# v1_0.net
KiCad netlist of a schematic drawn in EAGLE
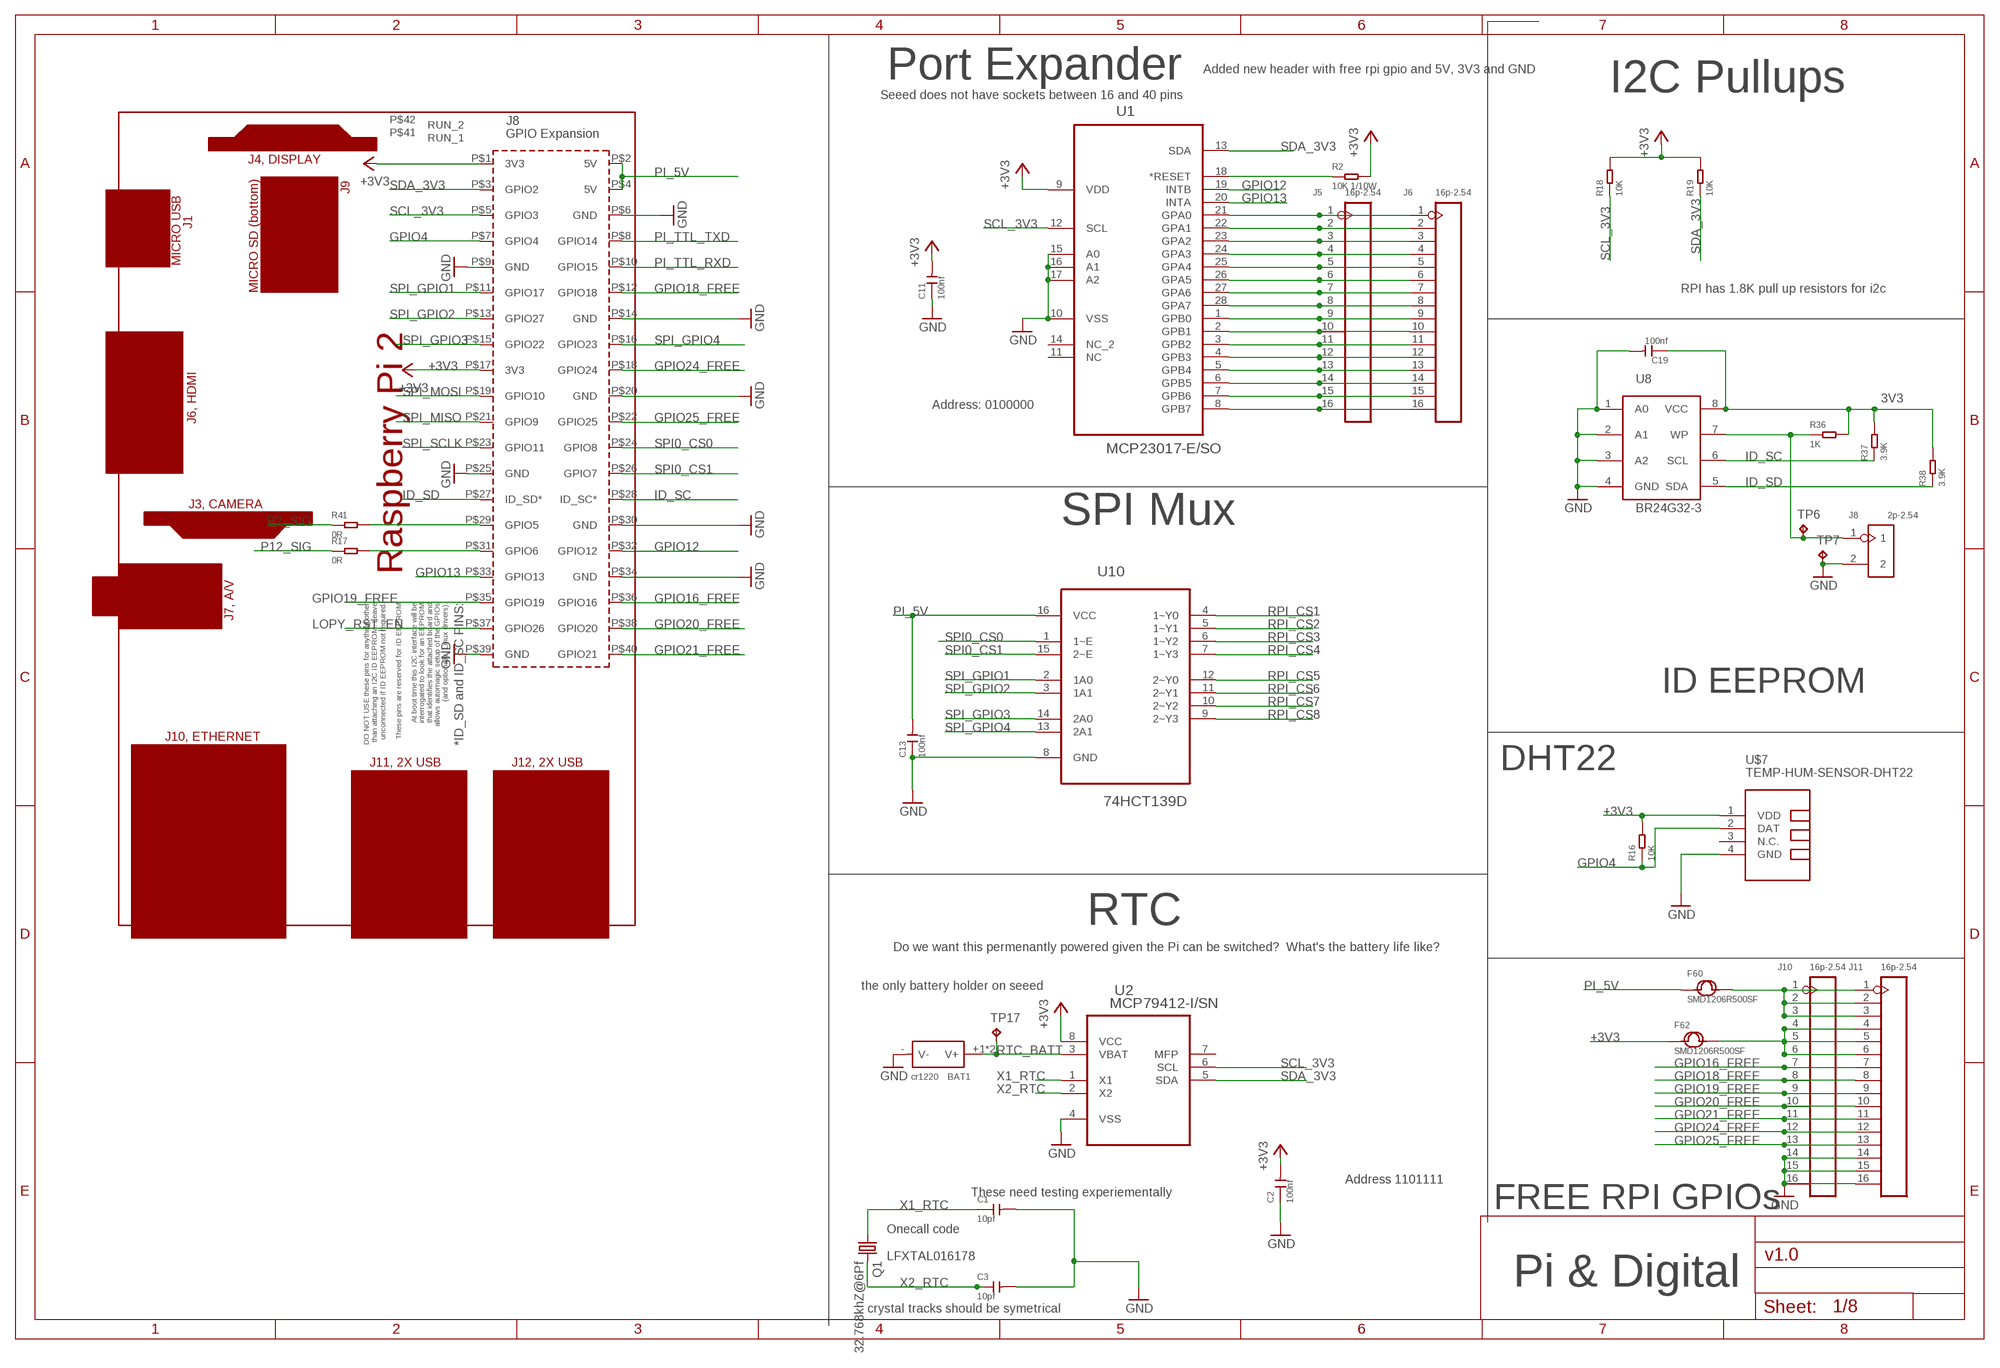
[diagram p0: schematic, sheet 1]
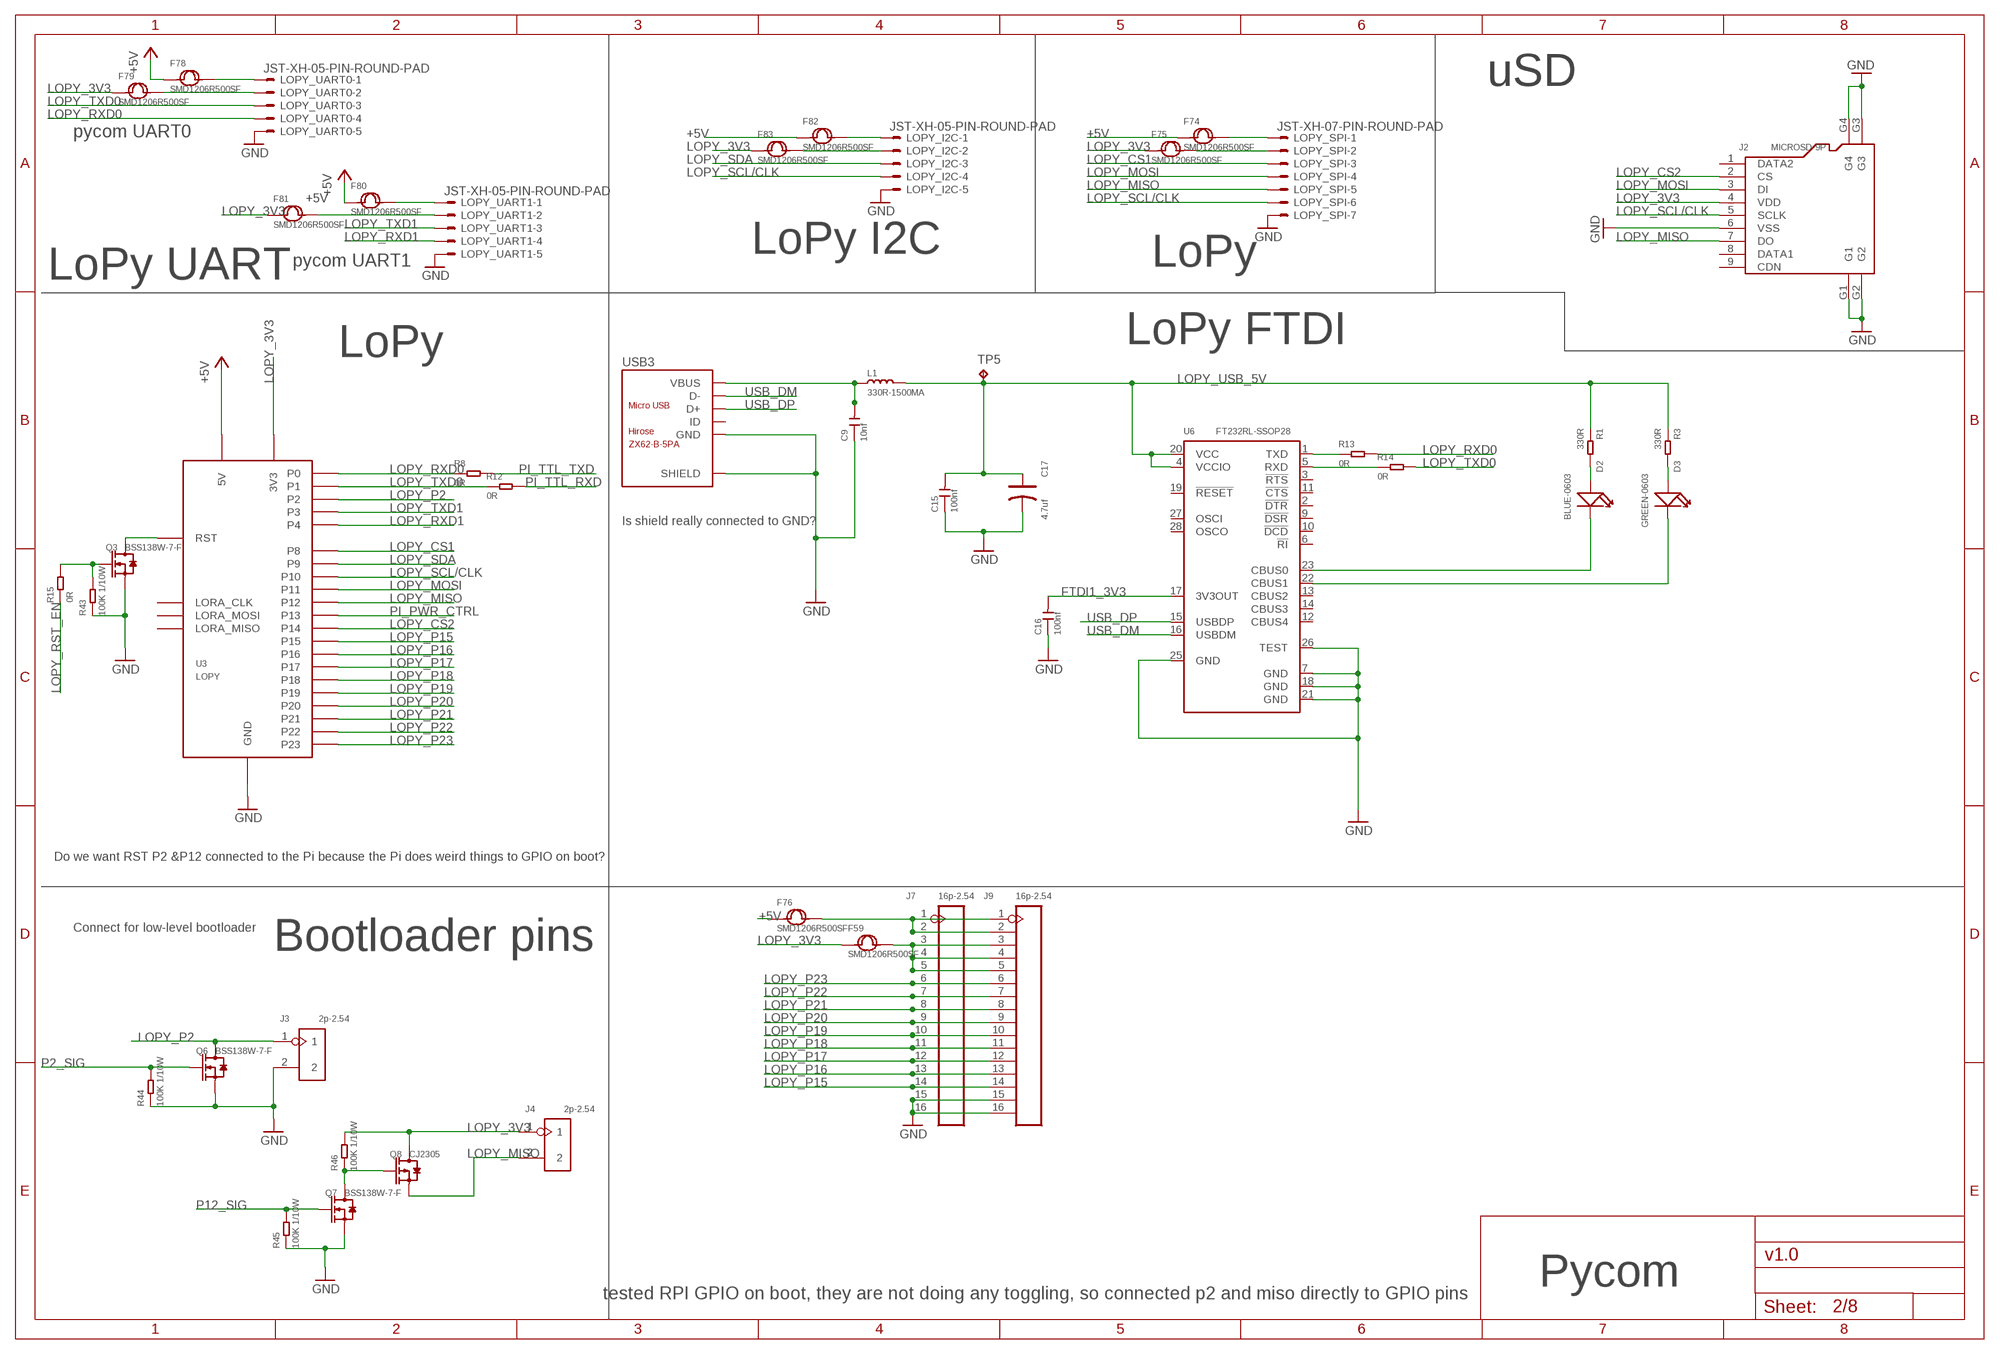
[diagram p1: schematic, sheet 2]
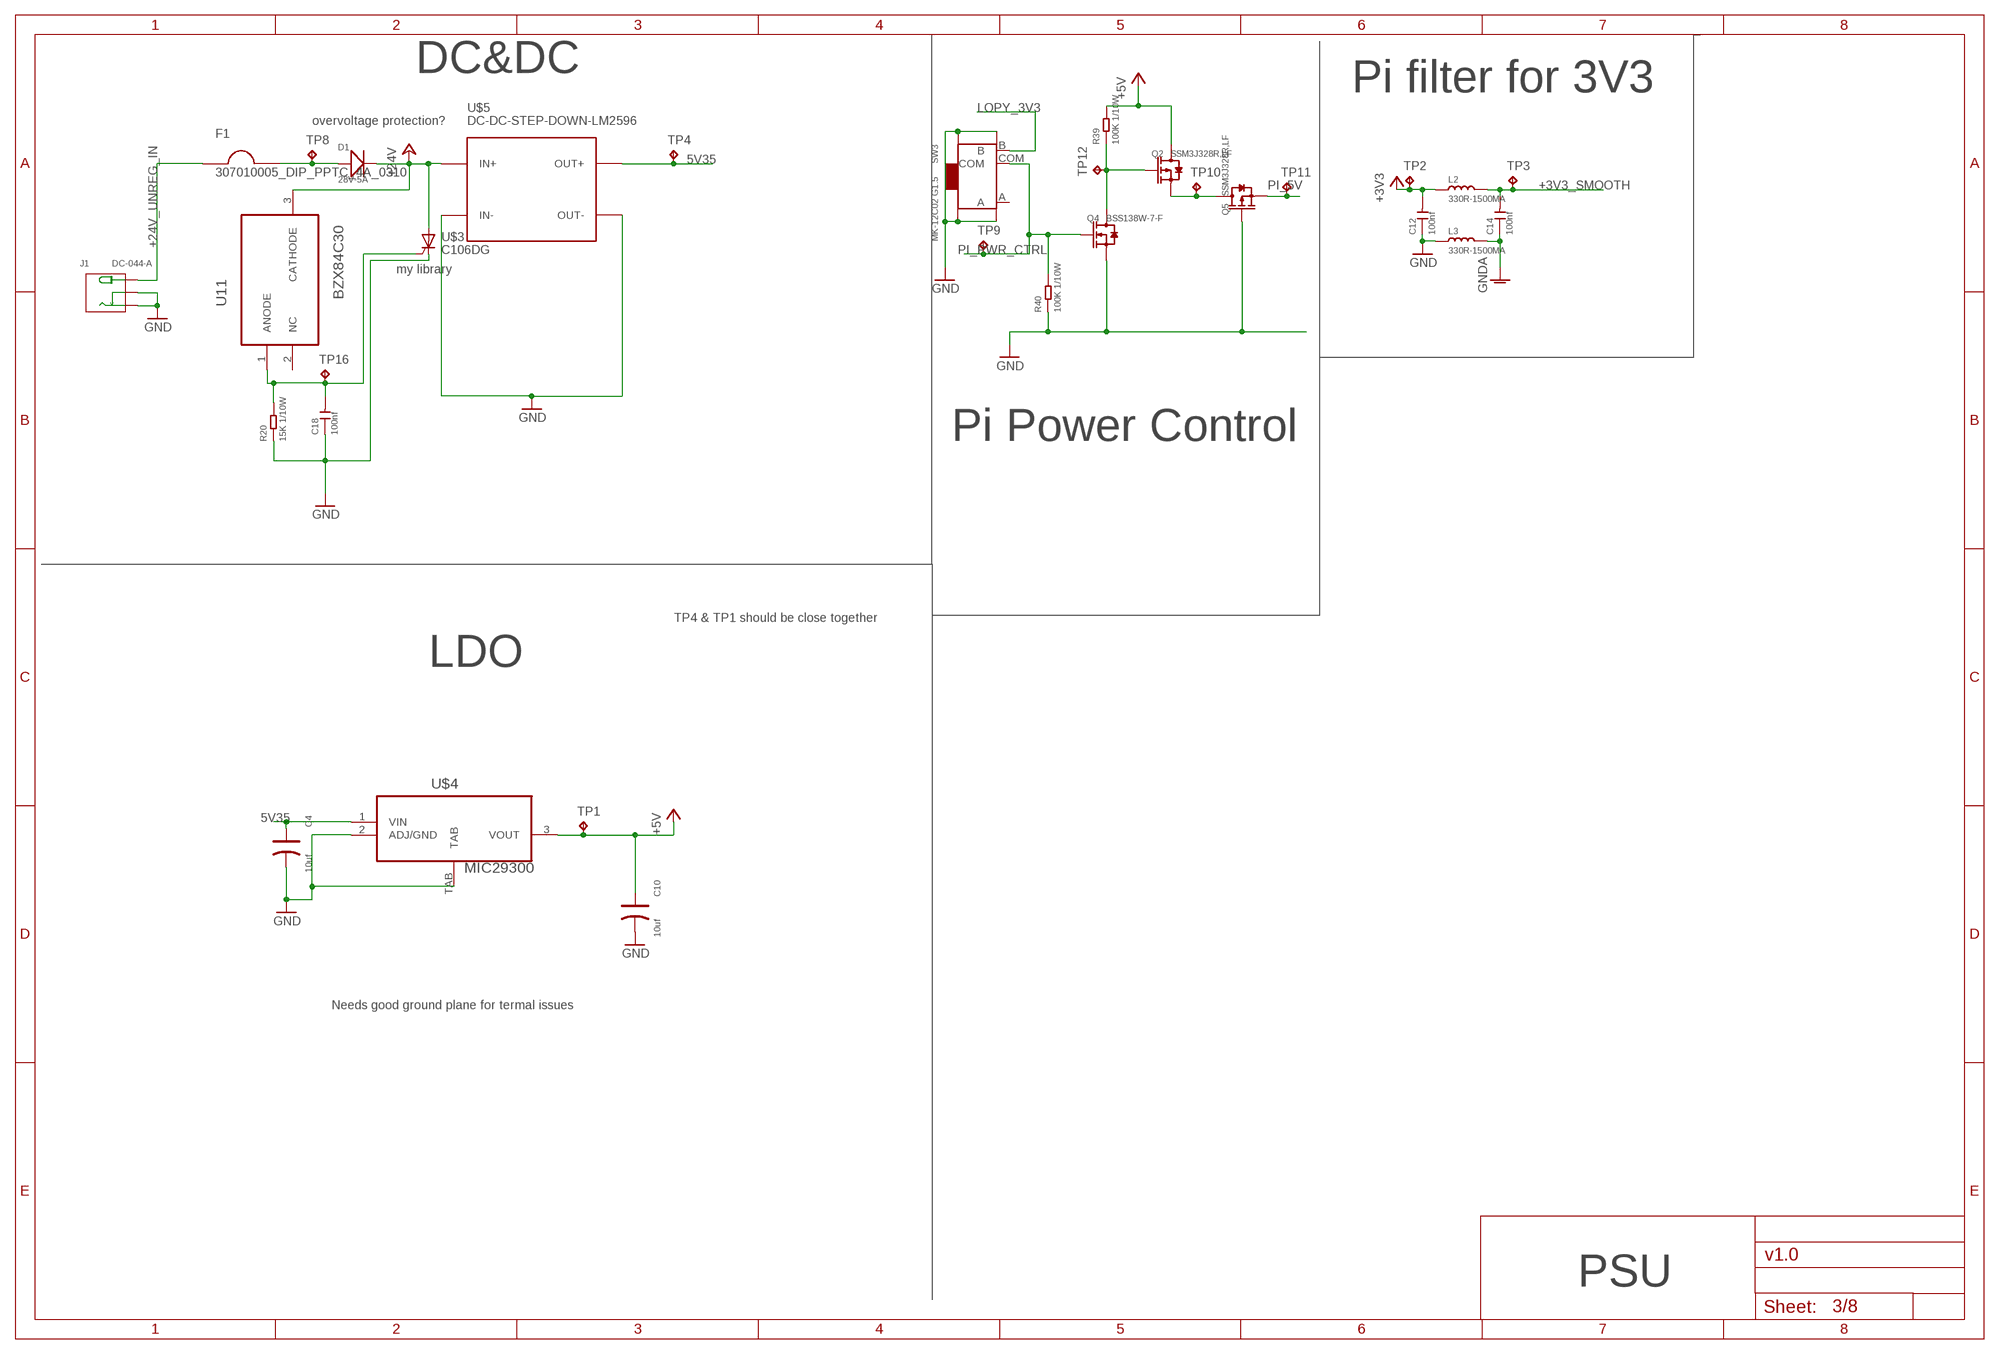
[diagram p2: schematic, sheet 3]
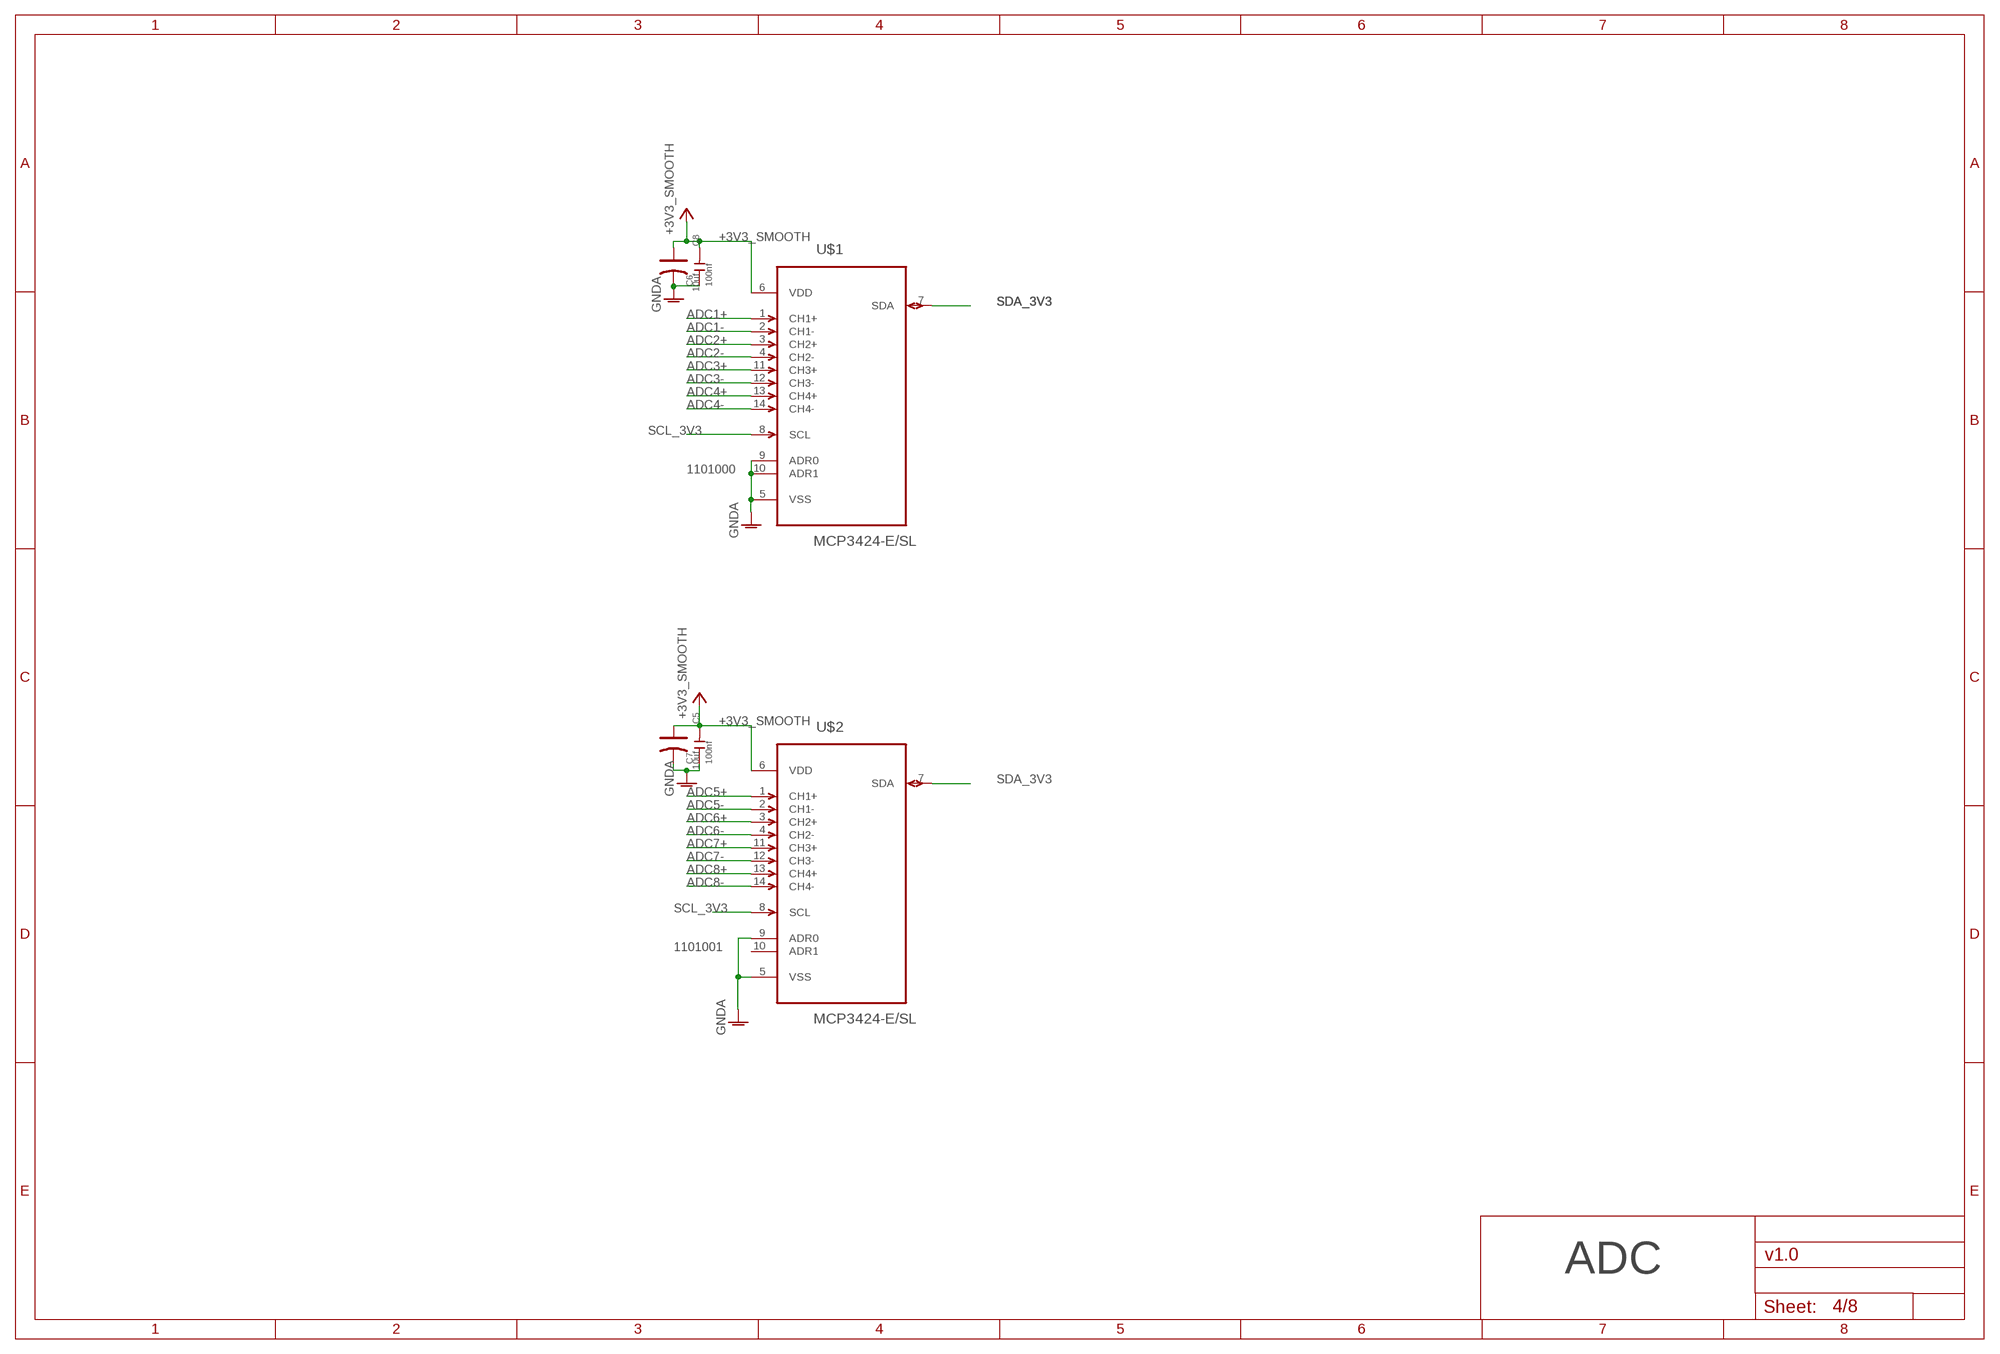
[diagram p3: schematic, sheet 4]
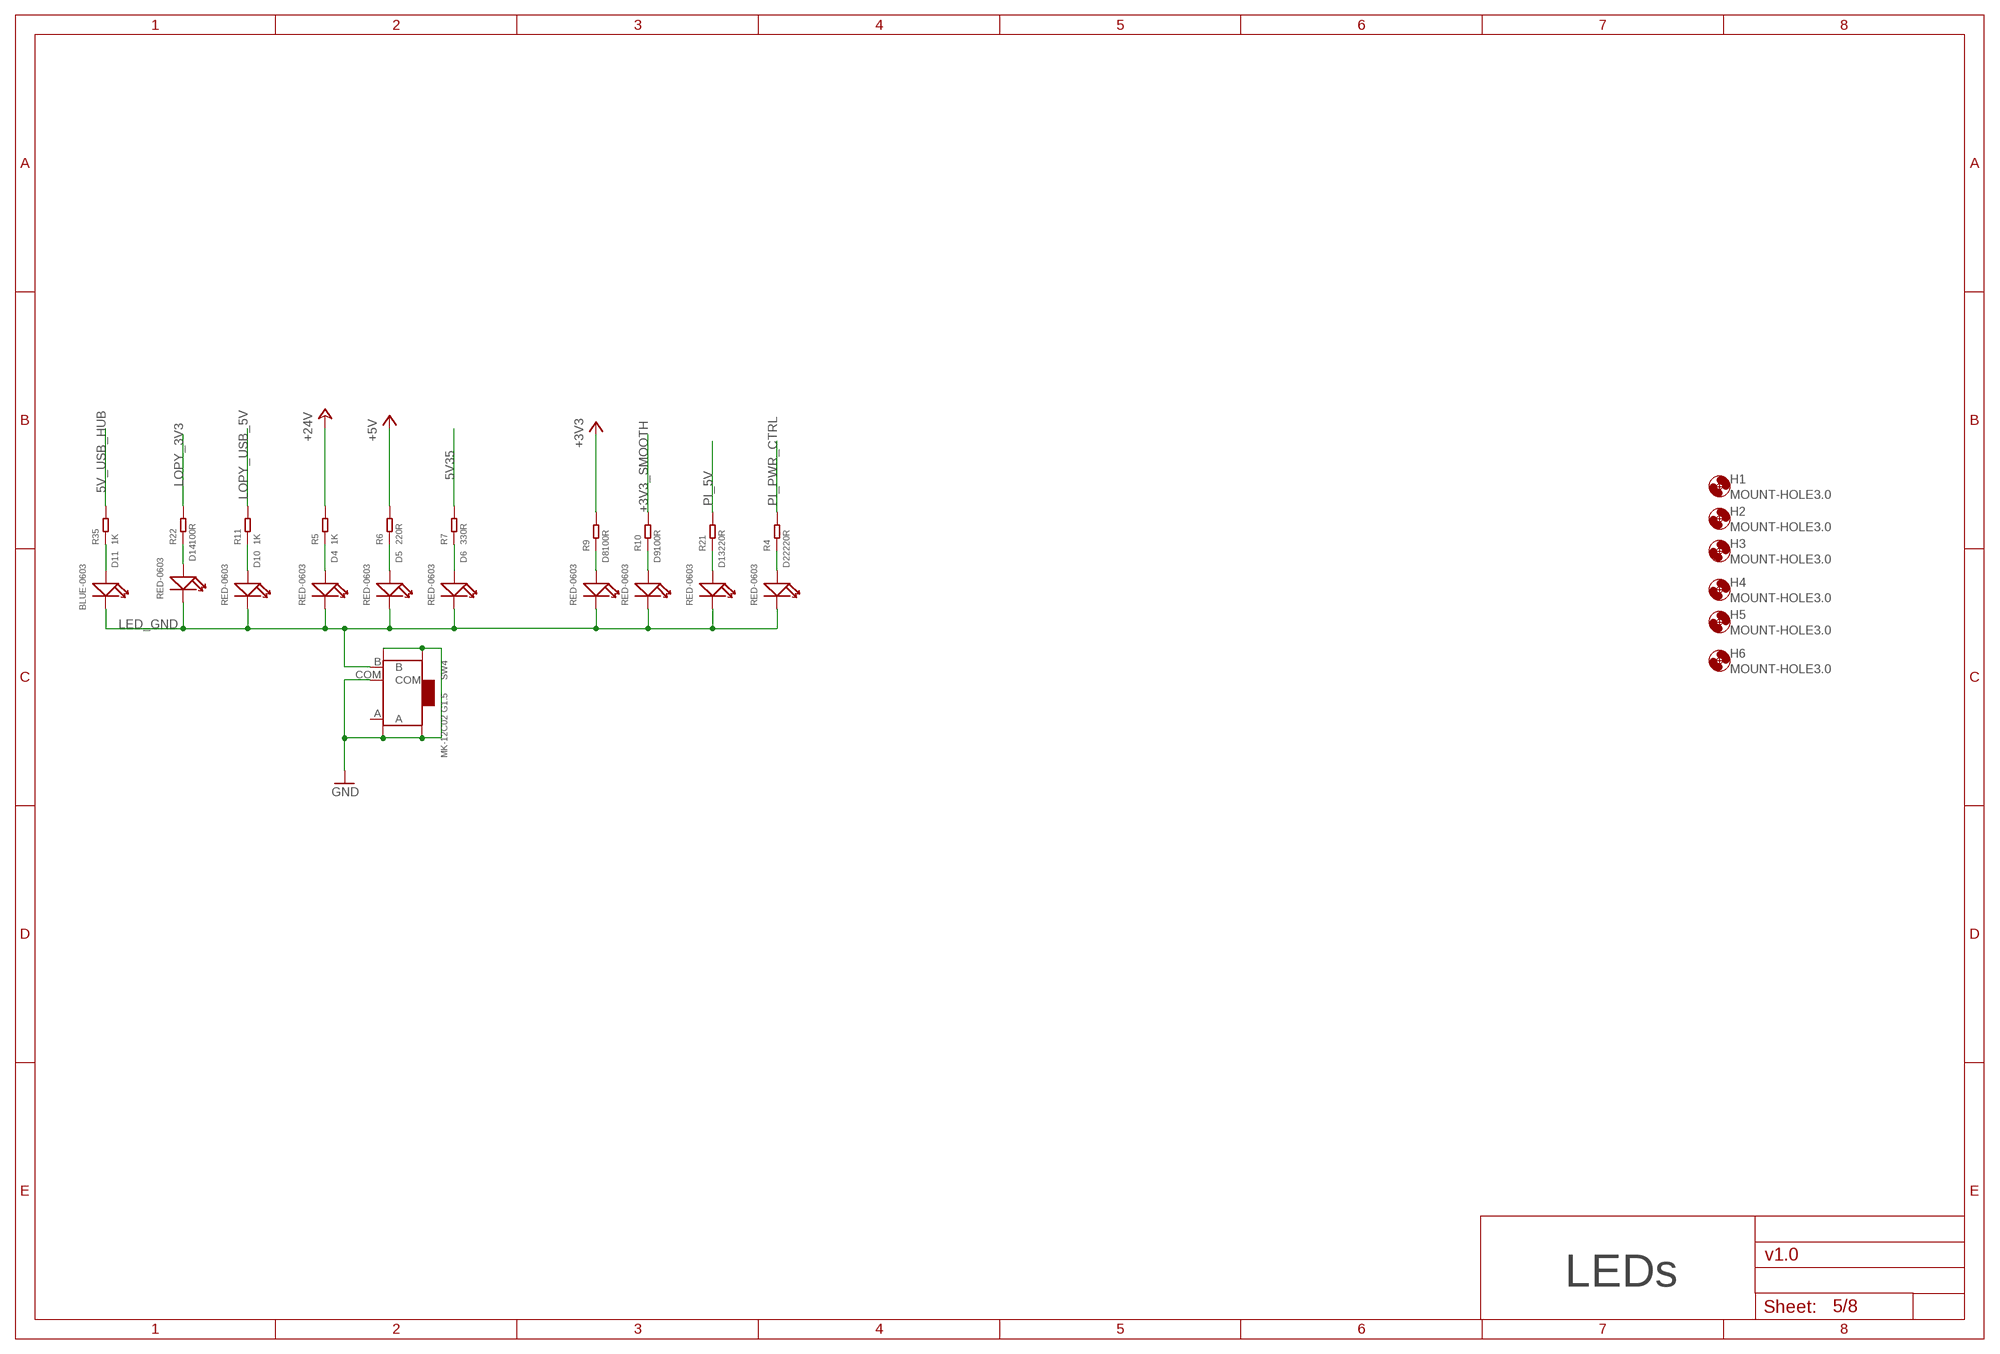
[diagram p4: schematic, sheet 5]
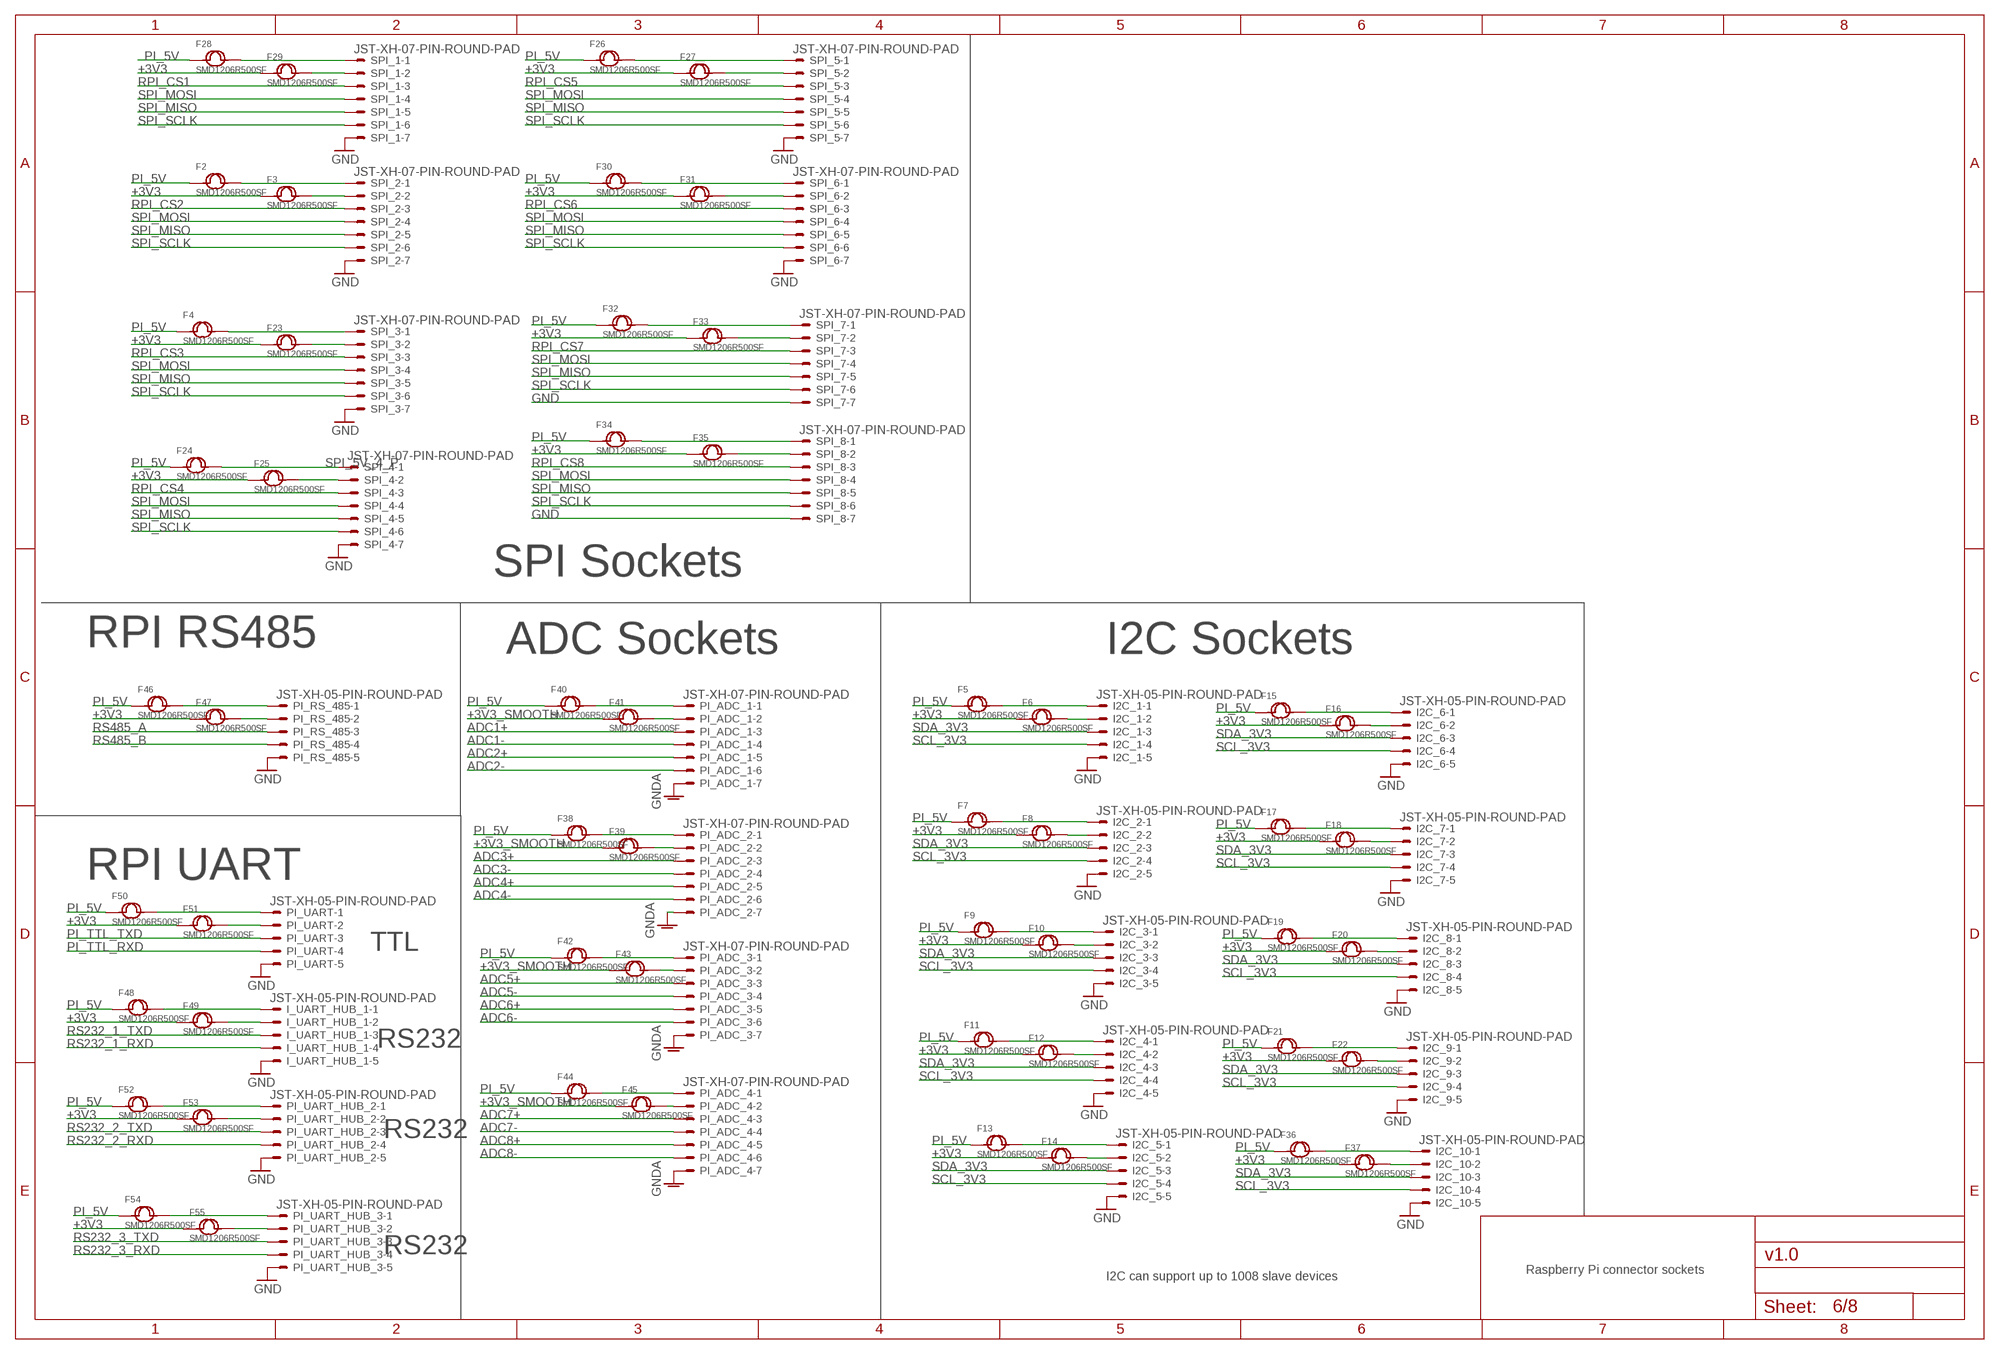
[diagram p5: schematic, sheet 6]
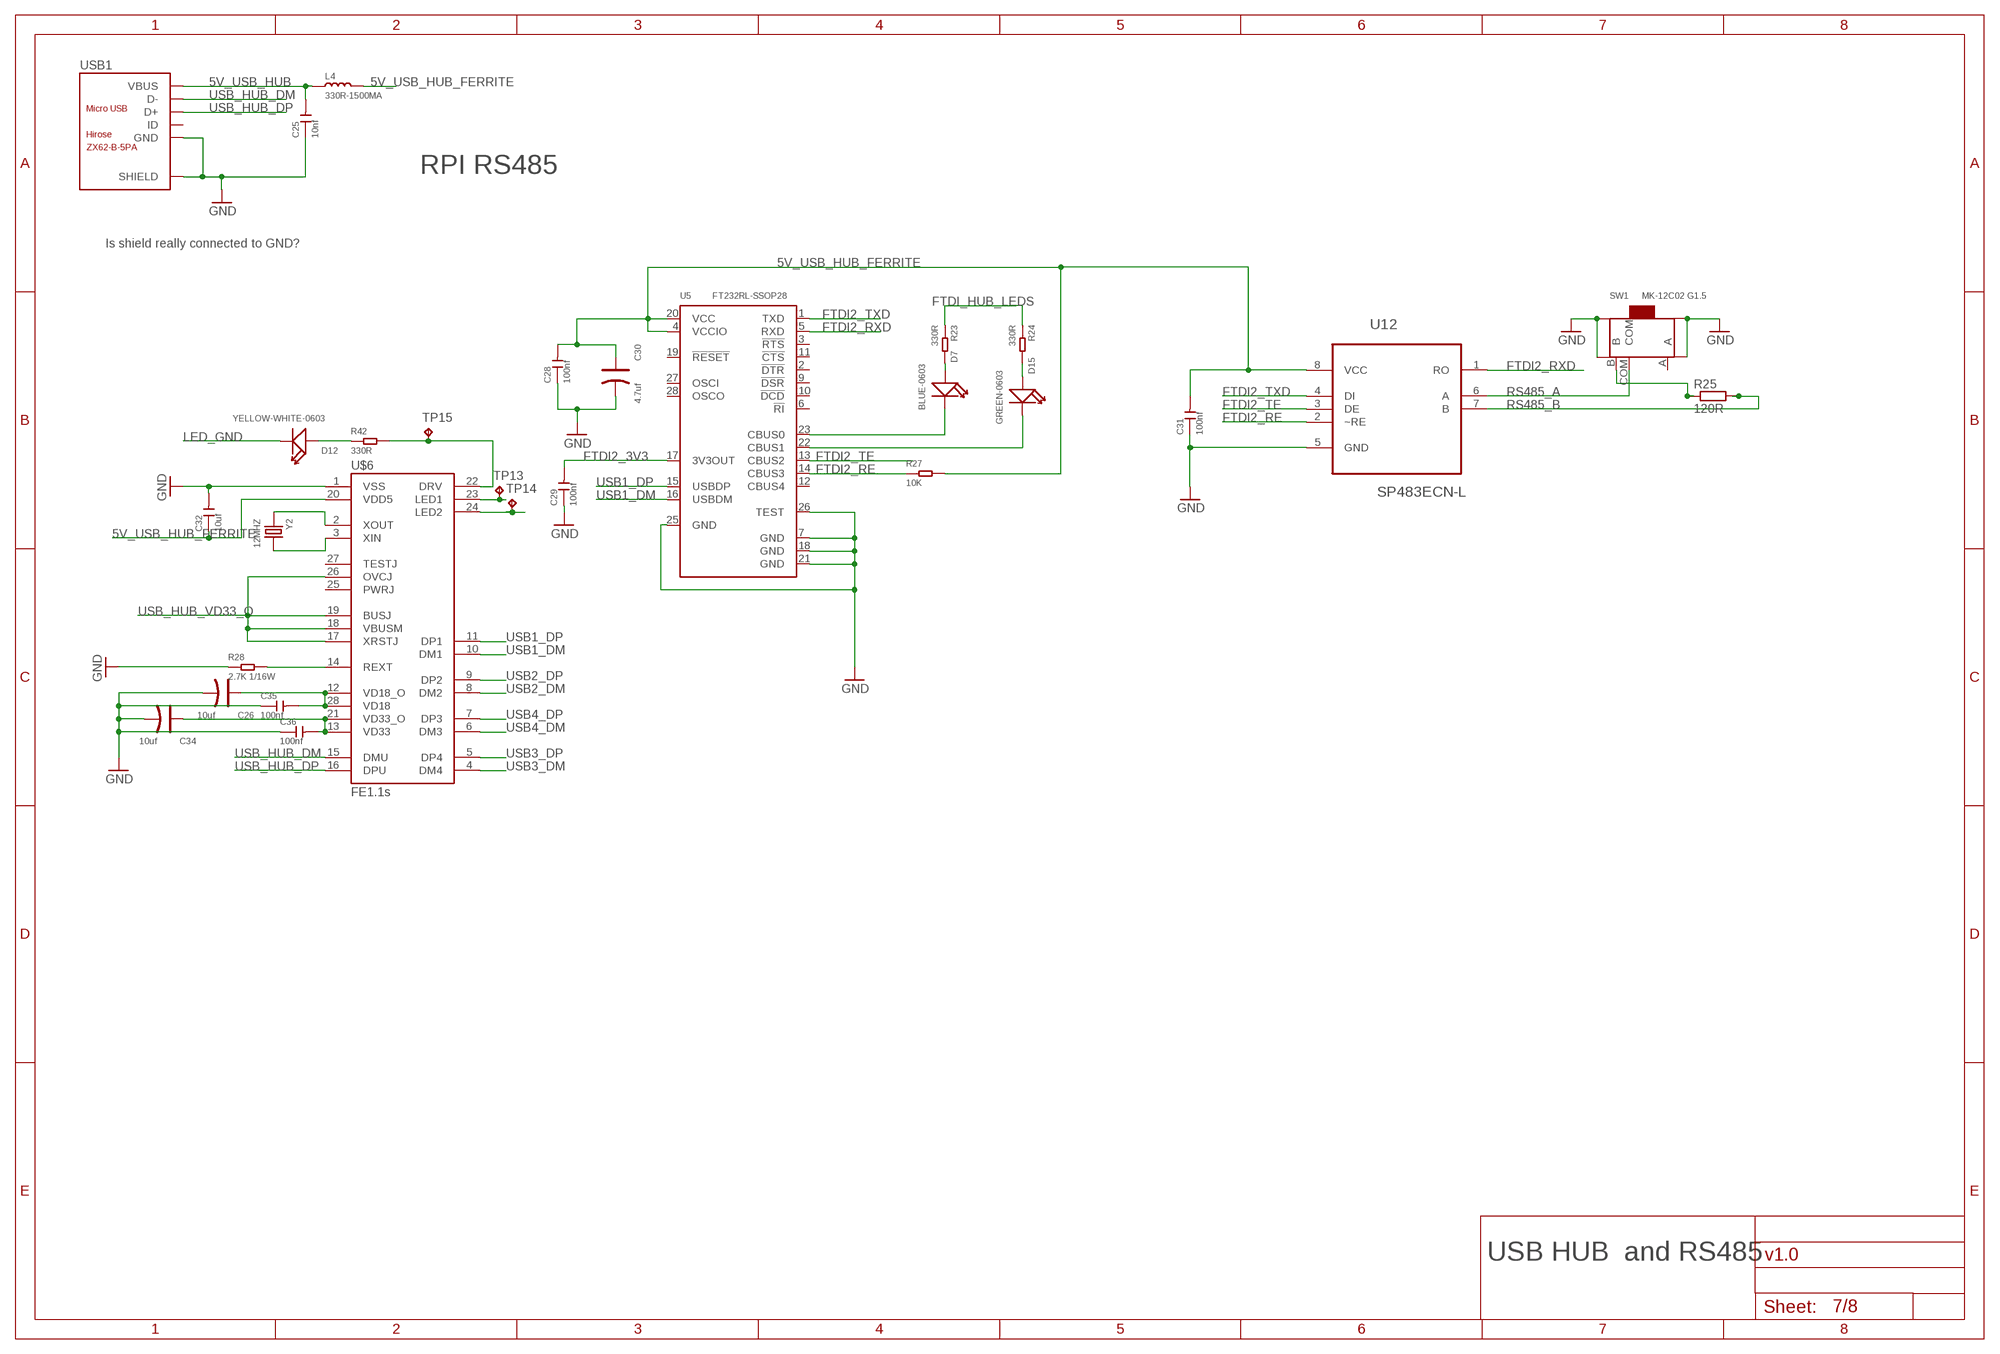
[diagram p6: schematic, sheet 7]
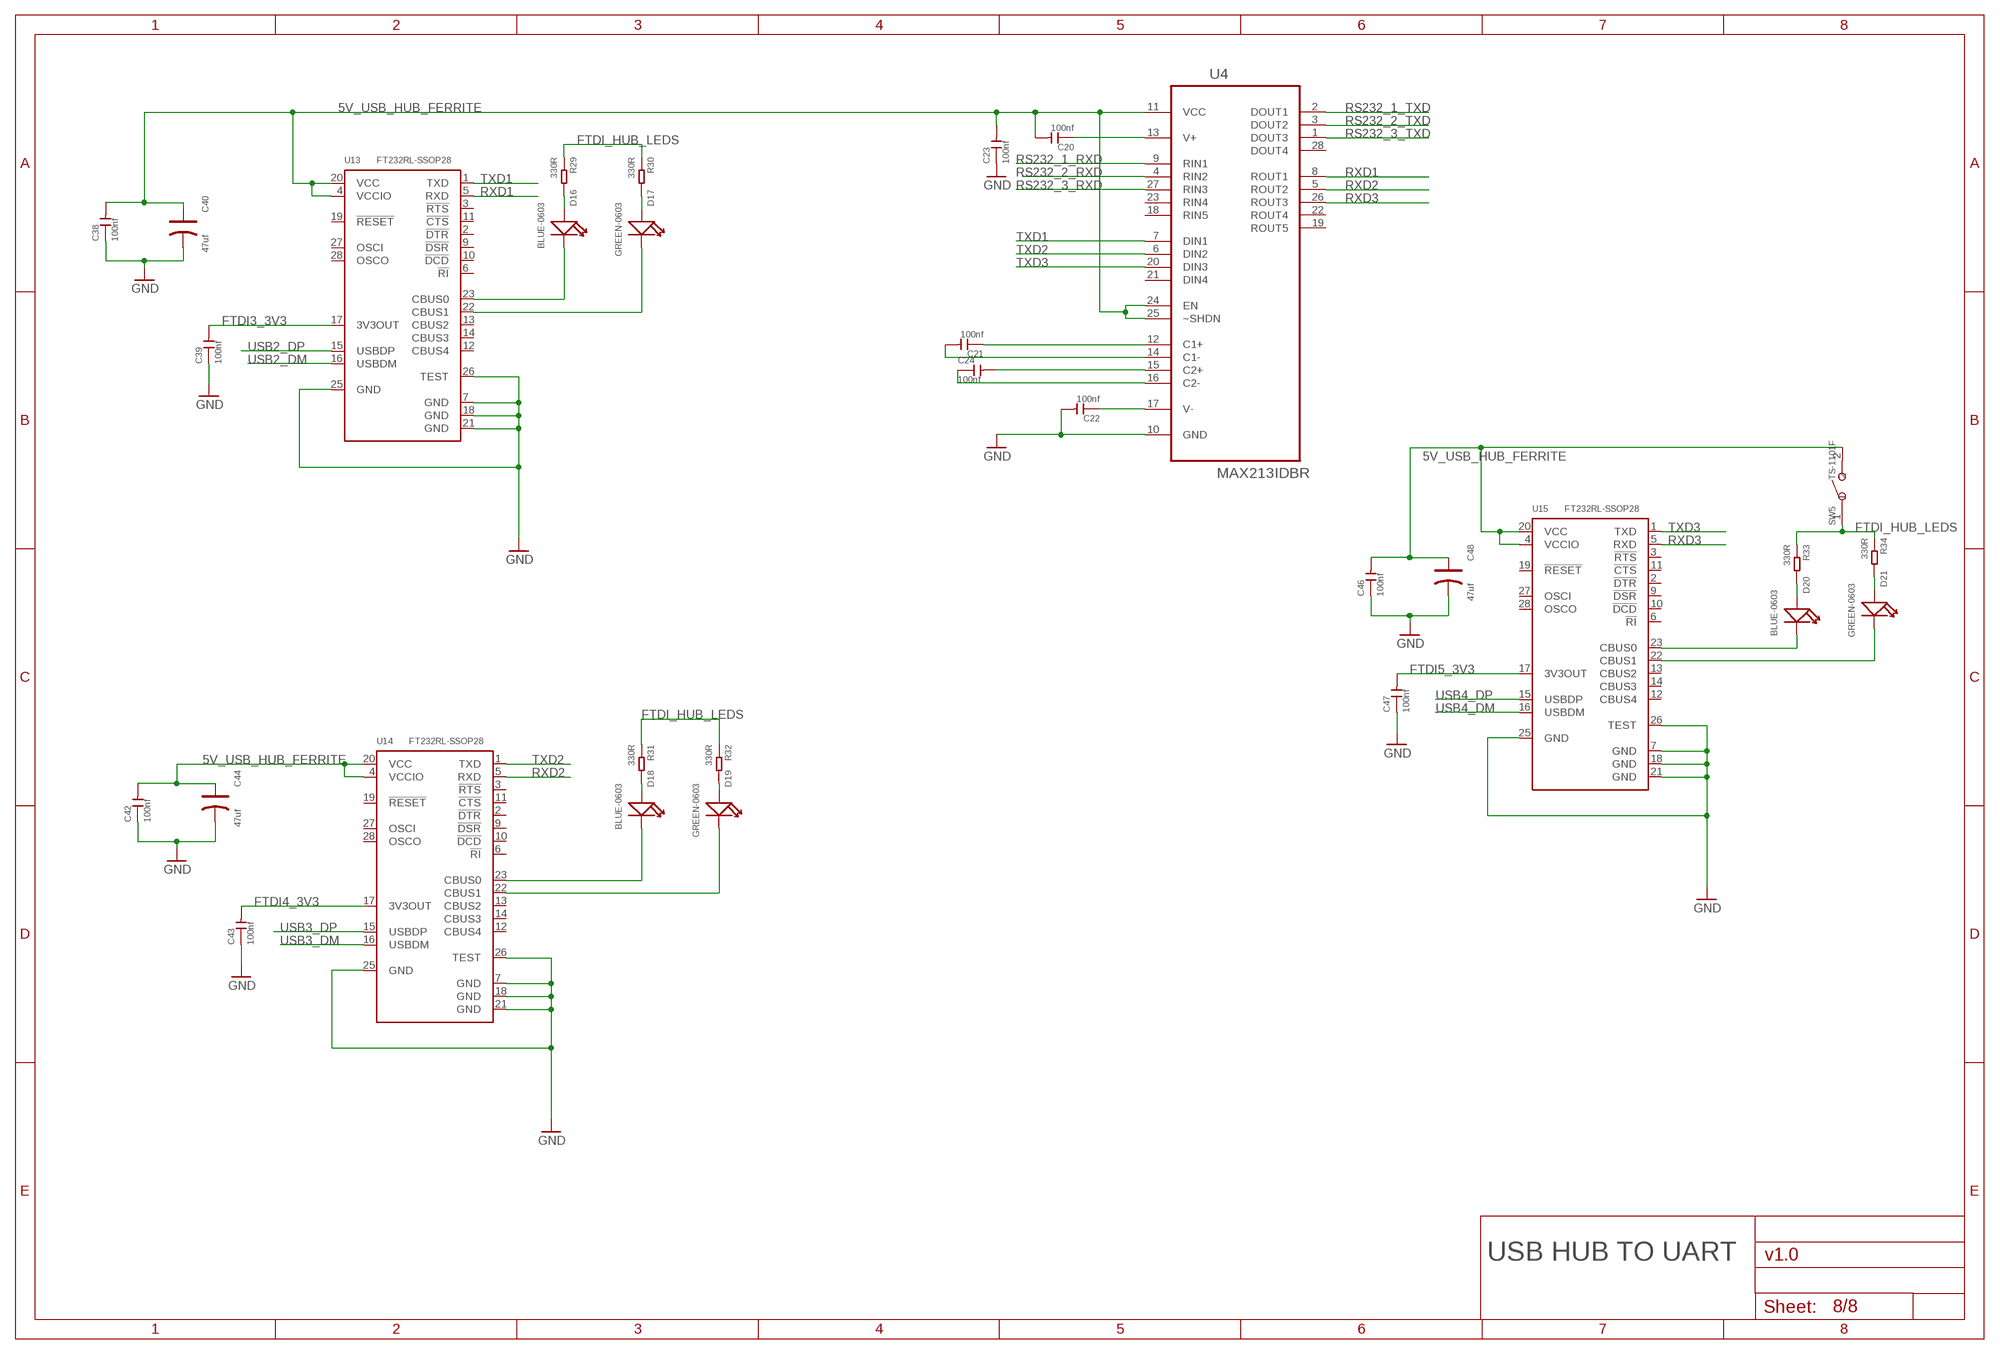
[diagram p7: schematic, sheet 8]

(export (version "E")
  (design (tool "Eeschema 10.0.6"))
  (components
    (comp (ref "F2")
      (value "SMD1206R500SF")
      (footprint "eagle-import:F1206")
      (libsource (lib "eagle-import") (part "SMD-PPTC-500MA(1206)"))
    )
    (comp (ref "F3")
      (value "SMD1206R500SF")
      (footprint "eagle-import:F1206")
      (libsource (lib "eagle-import") (part "SMD-PPTC-500MA(1206)"))
    )
    (comp (ref "F4")
      (value "SMD1206R500SF")
      (footprint "eagle-import:F1206")
      (libsource (lib "eagle-import") (part "SMD-PPTC-500MA(1206)"))
    )
    (comp (ref "F5")
      (value "SMD1206R500SF")
      (footprint "eagle-import:F1206")
      (libsource (lib "eagle-import") (part "SMD-PPTC-500MA(1206)"))
    )
    (comp (ref "F6")
      (value "SMD1206R500SF")
      (footprint "eagle-import:F1206")
      (libsource (lib "eagle-import") (part "SMD-PPTC-500MA(1206)"))
    )
    (comp (ref "F7")
      (value "SMD1206R500SF")
      (footprint "eagle-import:F1206")
      (libsource (lib "eagle-import") (part "SMD-PPTC-500MA(1206)"))
    )
    (comp (ref "F8")
      (value "SMD1206R500SF")
      (footprint "eagle-import:F1206")
      (libsource (lib "eagle-import") (part "SMD-PPTC-500MA(1206)"))
    )
    (comp (ref "F9")
      (value "SMD1206R500SF")
      (footprint "eagle-import:F1206")
      (libsource (lib "eagle-import") (part "SMD-PPTC-500MA(1206)"))
    )
    (comp (ref "F10")
      (value "SMD1206R500SF")
      (footprint "eagle-import:F1206")
      (libsource (lib "eagle-import") (part "SMD-PPTC-500MA(1206)"))
    )
    (comp (ref "F11")
      (value "SMD1206R500SF")
      (footprint "eagle-import:F1206")
      (libsource (lib "eagle-import") (part "SMD-PPTC-500MA(1206)"))
    )
    (comp (ref "F12")
      (value "SMD1206R500SF")
      (footprint "eagle-import:F1206")
      (libsource (lib "eagle-import") (part "SMD-PPTC-500MA(1206)"))
    )
    (comp (ref "F13")
      (value "SMD1206R500SF")
      (footprint "eagle-import:F1206")
      (libsource (lib "eagle-import") (part "SMD-PPTC-500MA(1206)"))
    )
    (comp (ref "F14")
      (value "SMD1206R500SF")
      (footprint "eagle-import:F1206")
      (libsource (lib "eagle-import") (part "SMD-PPTC-500MA(1206)"))
    )
    (comp (ref "F15")
      (value "SMD1206R500SF")
      (footprint "eagle-import:F1206")
      (libsource (lib "eagle-import") (part "SMD-PPTC-500MA(1206)"))
    )
    (comp (ref "F16")
      (value "SMD1206R500SF")
      (footprint "eagle-import:F1206")
      (libsource (lib "eagle-import") (part "SMD-PPTC-500MA(1206)"))
    )
    (comp (ref "F17")
      (value "SMD1206R500SF")
      (footprint "eagle-import:F1206")
      (libsource (lib "eagle-import") (part "SMD-PPTC-500MA(1206)"))
    )
    (comp (ref "F18")
      (value "SMD1206R500SF")
      (footprint "eagle-import:F1206")
      (libsource (lib "eagle-import") (part "SMD-PPTC-500MA(1206)"))
    )
    (comp (ref "F19")
      (value "SMD1206R500SF")
      (footprint "eagle-import:F1206")
      (libsource (lib "eagle-import") (part "SMD-PPTC-500MA(1206)"))
    )
    (comp (ref "F20")
      (value "SMD1206R500SF")
      (footprint "eagle-import:F1206")
      (libsource (lib "eagle-import") (part "SMD-PPTC-500MA(1206)"))
    )
    (comp (ref "F21")
      (value "SMD1206R500SF")
      (footprint "eagle-import:F1206")
      (libsource (lib "eagle-import") (part "SMD-PPTC-500MA(1206)"))
    )
    (comp (ref "F22")
      (value "SMD1206R500SF")
      (footprint "eagle-import:F1206")
      (libsource (lib "eagle-import") (part "SMD-PPTC-500MA(1206)"))
    )
    (comp (ref "F23")
      (value "SMD1206R500SF")
      (footprint "eagle-import:F1206")
      (libsource (lib "eagle-import") (part "SMD-PPTC-500MA(1206)"))
    )
    (comp (ref "F24")
      (value "SMD1206R500SF")
      (footprint "eagle-import:F1206")
      (libsource (lib "eagle-import") (part "SMD-PPTC-500MA(1206)"))
    )
    (comp (ref "F25")
      (value "SMD1206R500SF")
      (footprint "eagle-import:F1206")
      (libsource (lib "eagle-import") (part "SMD-PPTC-500MA(1206)"))
    )
    (comp (ref "F26")
      (value "SMD1206R500SF")
      (footprint "eagle-import:F1206")
      (libsource (lib "eagle-import") (part "SMD-PPTC-500MA(1206)"))
    )
    (comp (ref "F27")
      (value "SMD1206R500SF")
      (footprint "eagle-import:F1206")
      (libsource (lib "eagle-import") (part "SMD-PPTC-500MA(1206)"))
    )
    (comp (ref "F28")
      (value "SMD1206R500SF")
      (footprint "eagle-import:F1206")
      (libsource (lib "eagle-import") (part "SMD-PPTC-500MA(1206)"))
    )
    (comp (ref "F29")
      (value "SMD1206R500SF")
      (footprint "eagle-import:F1206")
      (libsource (lib "eagle-import") (part "SMD-PPTC-500MA(1206)"))
    )
    (comp (ref "F30")
      (value "SMD1206R500SF")
      (footprint "eagle-import:F1206")
      (libsource (lib "eagle-import") (part "SMD-PPTC-500MA(1206)"))
    )
    (comp (ref "F31")
      (value "SMD1206R500SF")
      (footprint "eagle-import:F1206")
      (libsource (lib "eagle-import") (part "SMD-PPTC-500MA(1206)"))
    )
    (comp (ref "F32")
      (value "SMD1206R500SF")
      (footprint "eagle-import:F1206")
      (libsource (lib "eagle-import") (part "SMD-PPTC-500MA(1206)"))
    )
    (comp (ref "F33")
      (value "SMD1206R500SF")
      (footprint "eagle-import:F1206")
      (libsource (lib "eagle-import") (part "SMD-PPTC-500MA(1206)"))
    )
    (comp (ref "F34")
      (value "SMD1206R500SF")
      (footprint "eagle-import:F1206")
      (libsource (lib "eagle-import") (part "SMD-PPTC-500MA(1206)"))
    )
    (comp (ref "F35")
      (value "SMD1206R500SF")
      (footprint "eagle-import:F1206")
      (libsource (lib "eagle-import") (part "SMD-PPTC-500MA(1206)"))
    )
    (comp (ref "F36")
      (value "SMD1206R500SF")
      (footprint "eagle-import:F1206")
      (libsource (lib "eagle-import") (part "SMD-PPTC-500MA(1206)"))
    )
    (comp (ref "F37")
      (value "SMD1206R500SF")
      (footprint "eagle-import:F1206")
      (libsource (lib "eagle-import") (part "SMD-PPTC-500MA(1206)"))
    )
    (comp (ref "F38")
      (value "SMD1206R500SF")
      (footprint "eagle-import:F1206")
      (libsource (lib "eagle-import") (part "SMD-PPTC-500MA(1206)"))
    )
    (comp (ref "F39")
      (value "SMD1206R500SF")
      (footprint "eagle-import:F1206")
      (libsource (lib "eagle-import") (part "SMD-PPTC-500MA(1206)"))
    )
    (comp (ref "F40")
      (value "SMD1206R500SF")
      (footprint "eagle-import:F1206")
      (libsource (lib "eagle-import") (part "SMD-PPTC-500MA(1206)"))
    )
    (comp (ref "F41")
      (value "SMD1206R500SF")
      (footprint "eagle-import:F1206")
      (libsource (lib "eagle-import") (part "SMD-PPTC-500MA(1206)"))
    )
    (comp (ref "F42")
      (value "SMD1206R500SF")
      (footprint "eagle-import:F1206")
      (libsource (lib "eagle-import") (part "SMD-PPTC-500MA(1206)"))
    )
    (comp (ref "F43")
      (value "SMD1206R500SF")
      (footprint "eagle-import:F1206")
      (libsource (lib "eagle-import") (part "SMD-PPTC-500MA(1206)"))
    )
    (comp (ref "F44")
      (value "SMD1206R500SF")
      (footprint "eagle-import:F1206")
      (libsource (lib "eagle-import") (part "SMD-PPTC-500MA(1206)"))
    )
    (comp (ref "F45")
      (value "SMD1206R500SF")
      (footprint "eagle-import:F1206")
      (libsource (lib "eagle-import") (part "SMD-PPTC-500MA(1206)"))
    )
    (comp (ref "F46")
      (value "SMD1206R500SF")
      (footprint "eagle-import:F1206")
      (libsource (lib "eagle-import") (part "SMD-PPTC-500MA(1206)"))
    )
    (comp (ref "F47")
      (value "SMD1206R500SF")
      (footprint "eagle-import:F1206")
      (libsource (lib "eagle-import") (part "SMD-PPTC-500MA(1206)"))
    )
    (comp (ref "F48")
      (value "SMD1206R500SF")
      (footprint "eagle-import:F1206")
      (libsource (lib "eagle-import") (part "SMD-PPTC-500MA(1206)"))
    )
    (comp (ref "F49")
      (value "SMD1206R500SF")
      (footprint "eagle-import:F1206")
      (libsource (lib "eagle-import") (part "SMD-PPTC-500MA(1206)"))
    )
    (comp (ref "F50")
      (value "SMD1206R500SF")
      (footprint "eagle-import:F1206")
      (libsource (lib "eagle-import") (part "SMD-PPTC-500MA(1206)"))
    )
    (comp (ref "F51")
      (value "SMD1206R500SF")
      (footprint "eagle-import:F1206")
      (libsource (lib "eagle-import") (part "SMD-PPTC-500MA(1206)"))
    )
    (comp (ref "F52")
      (value "SMD1206R500SF")
      (footprint "eagle-import:F1206")
      (libsource (lib "eagle-import") (part "SMD-PPTC-500MA(1206)"))
    )
    (comp (ref "F53")
      (value "SMD1206R500SF")
      (footprint "eagle-import:F1206")
      (libsource (lib "eagle-import") (part "SMD-PPTC-500MA(1206)"))
    )
    (comp (ref "F54")
      (value "SMD1206R500SF")
      (footprint "eagle-import:F1206")
      (libsource (lib "eagle-import") (part "SMD-PPTC-500MA(1206)"))
    )
    (comp (ref "F55")
      (value "SMD1206R500SF")
      (footprint "eagle-import:F1206")
      (libsource (lib "eagle-import") (part "SMD-PPTC-500MA(1206)"))
    )
    (comp (ref "I2C_1")
      (value "JST-XH-05-PIN-ROUND-PAD")
      (footprint "eagle-import:JST-XH-05-PACKAGE-ROUND-PAD")
      (libsource (lib "eagle-import") (part "JST-XH-05-PIN-ROUND-PAD"))
    )
    (comp (ref "I2C_2")
      (value "JST-XH-05-PIN-ROUND-PAD")
      (footprint "eagle-import:JST-XH-05-PACKAGE-ROUND-PAD")
      (libsource (lib "eagle-import") (part "JST-XH-05-PIN-ROUND-PAD"))
    )
    (comp (ref "I2C_3")
      (value "JST-XH-05-PIN-ROUND-PAD")
      (footprint "eagle-import:JST-XH-05-PACKAGE-ROUND-PAD")
      (libsource (lib "eagle-import") (part "JST-XH-05-PIN-ROUND-PAD"))
    )
    (comp (ref "I2C_4")
      (value "JST-XH-05-PIN-ROUND-PAD")
      (footprint "eagle-import:JST-XH-05-PACKAGE-ROUND-PAD")
      (libsource (lib "eagle-import") (part "JST-XH-05-PIN-ROUND-PAD"))
    )
    (comp (ref "I2C_5")
      (value "JST-XH-05-PIN-ROUND-PAD")
      (footprint "eagle-import:JST-XH-05-PACKAGE-ROUND-PAD")
      (libsource (lib "eagle-import") (part "JST-XH-05-PIN-ROUND-PAD"))
    )
    (comp (ref "I2C_6")
      (value "JST-XH-05-PIN-ROUND-PAD")
      (footprint "eagle-import:JST-XH-05-PACKAGE-ROUND-PAD")
      (libsource (lib "eagle-import") (part "JST-XH-05-PIN-ROUND-PAD"))
    )
    (comp (ref "I2C_7")
      (value "JST-XH-05-PIN-ROUND-PAD")
      (footprint "eagle-import:JST-XH-05-PACKAGE-ROUND-PAD")
      (libsource (lib "eagle-import") (part "JST-XH-05-PIN-ROUND-PAD"))
    )
    (comp (ref "I2C_8")
      (value "JST-XH-05-PIN-ROUND-PAD")
      (footprint "eagle-import:JST-XH-05-PACKAGE-ROUND-PAD")
      (libsource (lib "eagle-import") (part "JST-XH-05-PIN-ROUND-PAD"))
    )
    (comp (ref "I2C_9")
      (value "JST-XH-05-PIN-ROUND-PAD")
      (footprint "eagle-import:JST-XH-05-PACKAGE-ROUND-PAD")
      (libsource (lib "eagle-import") (part "JST-XH-05-PIN-ROUND-PAD"))
    )
    (comp (ref "I2C_10")
      (value "JST-XH-05-PIN-ROUND-PAD")
      (footprint "eagle-import:JST-XH-05-PACKAGE-ROUND-PAD")
      (libsource (lib "eagle-import") (part "JST-XH-05-PIN-ROUND-PAD"))
    )
    (comp (ref "I_UART_HUB_1")
      (value "JST-XH-05-PIN-ROUND-PAD")
      (footprint "eagle-import:JST-XH-05-PACKAGE-ROUND-PAD")
      (libsource (lib "eagle-import") (part "JST-XH-05-PIN-ROUND-PAD"))
    )
    (comp (ref "PI_ADC_1")
      (value "JST-XH-07-PIN-ROUND-PAD")
      (footprint "eagle-import:JST-XH-07-PACKAGE-ROUND-PAD")
      (libsource (lib "eagle-import") (part "JST-XH-07-PIN-ROUND-PAD"))
    )
    (comp (ref "PI_ADC_2")
      (value "JST-XH-07-PIN-ROUND-PAD")
      (footprint "eagle-import:JST-XH-07-PACKAGE-ROUND-PAD")
      (libsource (lib "eagle-import") (part "JST-XH-07-PIN-ROUND-PAD"))
    )
    (comp (ref "PI_ADC_3")
      (value "JST-XH-07-PIN-ROUND-PAD")
      (footprint "eagle-import:JST-XH-07-PACKAGE-ROUND-PAD")
      (libsource (lib "eagle-import") (part "JST-XH-07-PIN-ROUND-PAD"))
    )
    (comp (ref "PI_ADC_4")
      (value "JST-XH-07-PIN-ROUND-PAD")
      (footprint "eagle-import:JST-XH-07-PACKAGE-ROUND-PAD")
      (libsource (lib "eagle-import") (part "JST-XH-07-PIN-ROUND-PAD"))
    )
    (comp (ref "PI_RS_485")
      (value "JST-XH-05-PIN-ROUND-PAD")
      (footprint "eagle-import:JST-XH-05-PACKAGE-ROUND-PAD")
      (libsource (lib "eagle-import") (part "JST-XH-05-PIN-ROUND-PAD"))
    )
    (comp (ref "PI_UART")
      (value "JST-XH-05-PIN-ROUND-PAD")
      (footprint "eagle-import:JST-XH-05-PACKAGE-ROUND-PAD")
      (libsource (lib "eagle-import") (part "JST-XH-05-PIN-ROUND-PAD"))
    )
    (comp (ref "PI_UART_HUB_2")
      (value "JST-XH-05-PIN-ROUND-PAD")
      (footprint "eagle-import:JST-XH-05-PACKAGE-ROUND-PAD")
      (libsource (lib "eagle-import") (part "JST-XH-05-PIN-ROUND-PAD"))
    )
    (comp (ref "PI_UART_HUB_3")
      (value "JST-XH-05-PIN-ROUND-PAD")
      (footprint "eagle-import:JST-XH-05-PACKAGE-ROUND-PAD")
      (libsource (lib "eagle-import") (part "JST-XH-05-PIN-ROUND-PAD"))
    )
    (comp (ref "SPI_1")
      (value "JST-XH-07-PIN-ROUND-PAD")
      (footprint "eagle-import:JST-XH-07-PACKAGE-ROUND-PAD")
      (libsource (lib "eagle-import") (part "JST-XH-07-PIN-ROUND-PAD"))
    )
    (comp (ref "SPI_2")
      (value "JST-XH-07-PIN-ROUND-PAD")
      (footprint "eagle-import:JST-XH-07-PACKAGE-ROUND-PAD")
      (libsource (lib "eagle-import") (part "JST-XH-07-PIN-ROUND-PAD"))
    )
    (comp (ref "SPI_3")
      (value "JST-XH-07-PIN-ROUND-PAD")
      (footprint "eagle-import:JST-XH-07-PACKAGE-ROUND-PAD")
      (libsource (lib "eagle-import") (part "JST-XH-07-PIN-ROUND-PAD"))
    )
    (comp (ref "SPI_4")
      (value "JST-XH-07-PIN-ROUND-PAD")
      (footprint "eagle-import:JST-XH-07-PACKAGE-ROUND-PAD")
      (libsource (lib "eagle-import") (part "JST-XH-07-PIN-ROUND-PAD"))
    )
    (comp (ref "SPI_5")
      (value "JST-XH-07-PIN-ROUND-PAD")
      (footprint "eagle-import:JST-XH-07-PACKAGE-ROUND-PAD")
      (libsource (lib "eagle-import") (part "JST-XH-07-PIN-ROUND-PAD"))
    )
    (comp (ref "SPI_6")
      (value "JST-XH-07-PIN-ROUND-PAD")
      (footprint "eagle-import:JST-XH-07-PACKAGE-ROUND-PAD")
      (libsource (lib "eagle-import") (part "JST-XH-07-PIN-ROUND-PAD"))
    )
    (comp (ref "SPI_7")
      (value "JST-XH-07-PIN-ROUND-PAD")
      (footprint "eagle-import:JST-XH-07-PACKAGE-ROUND-PAD")
      (libsource (lib "eagle-import") (part "JST-XH-07-PIN-ROUND-PAD"))
    )
    (comp (ref "SPI_8")
      (value "JST-XH-07-PIN-ROUND-PAD")
      (footprint "eagle-import:JST-XH-07-PACKAGE-ROUND-PAD")
      (libsource (lib "eagle-import") (part "JST-XH-07-PIN-ROUND-PAD"))
    )
    (comp (ref "C9")
      (value "10nf")
      (footprint "eagle-import:C0805")
      (fields (field (name "MPN") "CC0805JRX7R9BB103"))
      (libsource (lib "eagle-import") (part "CERAMIC-10NF-50V-5%-X7R(0805)"))
    )
    (comp (ref "C15")
      (value "100nf")
      (footprint "eagle-import:C0603")
      (fields (field (name "MPN") "CC0603KRX7R9BB104"))
      (libsource (lib "eagle-import") (part "CERAMIC-100NF-50V-10%-X7R(0603)"))
    )
    (comp (ref "C16")
      (value "100nf")
      (footprint "eagle-import:C0603")
      (fields (field (name "MPN") "CC0603KRX7R9BB104"))
      (libsource (lib "eagle-import") (part "CERAMIC-100NF-50V-10%-X7R(0603)"))
    )
    (comp (ref "C17")
      (value "4.7uf")
      (footprint "eagle-import:AVX-A")
      (fields (field (name "MPN") "TAJA475*016#NJ"))
      (libsource (lib "eagle-import") (part "Seeed-Capacitor_464_TANTALUM-SMD-4.7UF-16V(AVX-A)"))
    )
    (comp (ref "D2")
      (value "BLUE-0603")
      (footprint "eagle-import:LED-0603")
      (fields (field (name "MPN") "19-217-BHC-ZL1M2RY-3T"))
      (libsource (lib "eagle-import") (part "Seeed-LED_472_SMD-LED-CLEAR-BLUE(0603)"))
    )
    (comp (ref "D3")
      (value "GREEN-0603")
      (footprint "eagle-import:LED-0603")
      (fields (field (name "MPN") "19-217-G7C-AN1P2-3T"))
      (libsource (lib "eagle-import") (part "SMD-LED-CLEAR-GREEN(0603)"))
    )
    (comp (ref "F59")
      (value "SMD1206R500SF")
      (footprint "eagle-import:F1206")
      (libsource (lib "eagle-import") (part "SMD-PPTC-500MA(1206)"))
    )
    (comp (ref "F74")
      (value "SMD1206R500SF")
      (footprint "eagle-import:F1206")
      (libsource (lib "eagle-import") (part "SMD-PPTC-500MA(1206)"))
    )
    (comp (ref "F75")
      (value "SMD1206R500SF")
      (footprint "eagle-import:F1206")
      (libsource (lib "eagle-import") (part "SMD-PPTC-500MA(1206)"))
    )
    (comp (ref "F76")
      (value "SMD1206R500SF")
      (footprint "eagle-import:F1206")
      (libsource (lib "eagle-import") (part "SMD-PPTC-500MA(1206)"))
    )
    (comp (ref "F78")
      (value "SMD1206R500SF")
      (footprint "eagle-import:F1206")
      (libsource (lib "eagle-import") (part "SMD-PPTC-500MA(1206)"))
    )
    (comp (ref "F79")
      (value "SMD1206R500SF")
      (footprint "eagle-import:F1206")
      (libsource (lib "eagle-import") (part "SMD-PPTC-500MA(1206)"))
    )
    (comp (ref "F80")
      (value "SMD1206R500SF")
      (footprint "eagle-import:F1206")
      (libsource (lib "eagle-import") (part "SMD-PPTC-500MA(1206)"))
    )
    (comp (ref "F81")
      (value "SMD1206R500SF")
      (footprint "eagle-import:F1206")
      (libsource (lib "eagle-import") (part "SMD-PPTC-500MA(1206)"))
    )
    (comp (ref "F82")
      (value "SMD1206R500SF")
      (footprint "eagle-import:F1206")
      (libsource (lib "eagle-import") (part "SMD-PPTC-500MA(1206)"))
    )
    (comp (ref "F83")
      (value "SMD1206R500SF")
      (footprint "eagle-import:F1206")
      (libsource (lib "eagle-import") (part "SMD-PPTC-500MA(1206)"))
    )
    (comp (ref "J2")
      (value "MICROSD-9P")
      (footprint "eagle-import:MICRO-SD9+4P-SMD-16.1X14.5X1.85MM")
      (libsource (lib "eagle-import") (part "MICRO-SD-CARD-HOLDER-9P"))
    )
    (comp (ref "J3")
      (value "2p-2.54")
      (footprint "eagle-import:H2-2.54")
      (fields (field (name "MPN") "P125-1102A0BS116A1"))
      (libsource (lib "eagle-import") (part "DIP-BLACK-MALE-HEADER-VERT(2P-2.54)"))
    )
    (comp (ref "J4")
      (value "2p-2.54")
      (footprint "eagle-import:H2-2.54")
      (fields (field (name "MPN") "P125-1102A0BS116A1"))
      (libsource (lib "eagle-import") (part "DIP-BLACK-MALE-HEADER-VERT(2P-2.54)"))
    )
    (comp (ref "J7")
      (value "16p-2.54")
      (footprint "eagle-import:H16-2.54")
      (fields (field (name "MPN") "P125-1116A0BS116AX"))
      (libsource (lib "eagle-import") (part "DIP-BLACK-MALE-HEADER-VERT(16P-2.54)"))
    )
    (comp (ref "J9")
      (value "16p-2.54")
      (footprint "eagle-import:H16-2.54")
      (fields (field (name "MPN") "P125-1116A0BS116AX"))
      (libsource (lib "eagle-import") (part "DIP-BLACK-MALE-HEADER-VERT(16P-2.54)"))
    )
    (comp (ref "L1")
      (value "330R-1500MA")
      (footprint "eagle-import:L0805")
      (fields (field (name "MPN") "BLM21PG331SN1D"))
      (libsource (lib "eagle-import") (part "SMD-FERRITE-BEAD-330R-1500MA(0805)'0805'"))
    )
    (comp (ref "LOPY_I2C")
      (value "JST-XH-05-PIN-ROUND-PAD")
      (footprint "eagle-import:JST-XH-05-PACKAGE-ROUND-PAD")
      (libsource (lib "eagle-import") (part "JST-XH-05-PIN-ROUND-PAD"))
    )
    (comp (ref "LOPY_SPI")
      (value "JST-XH-07-PIN-ROUND-PAD")
      (footprint "eagle-import:JST-XH-07-PACKAGE-ROUND-PAD")
      (libsource (lib "eagle-import") (part "JST-XH-07-PIN-ROUND-PAD"))
    )
    (comp (ref "LOPY_UART0")
      (value "JST-XH-05-PIN-ROUND-PAD")
      (footprint "eagle-import:JST-XH-05-PACKAGE-ROUND-PAD")
      (libsource (lib "eagle-import") (part "JST-XH-05-PIN-ROUND-PAD"))
    )
    (comp (ref "LOPY_UART1")
      (value "JST-XH-05-PIN-ROUND-PAD")
      (footprint "eagle-import:JST-XH-05-PACKAGE-ROUND-PAD")
      (libsource (lib "eagle-import") (part "JST-XH-05-PIN-ROUND-PAD"))
    )
    (comp (ref "Q3")
      (value "BSS138W-7-F")
      (footprint "eagle-import:SOT-23")
      (libsource (lib "eagle-import") (part "SMD-MOSFET-N-CH-50V-200MA-BSS138W-7-F(SOT-23)"))
    )
    (comp (ref "Q6")
      (value "BSS138W-7-F")
      (footprint "eagle-import:SOT-23")
      (libsource (lib "eagle-import") (part "SMD-MOSFET-N-CH-50V-200MA-BSS138W-7-F(SOT-23)"))
    )
    (comp (ref "Q7")
      (value "BSS138W-7-F")
      (footprint "eagle-import:SOT-23")
      (libsource (lib "eagle-import") (part "SMD-MOSFET-N-CH-50V-200MA-BSS138W-7-F(SOT-23)"))
    )
    (comp (ref "Q8")
      (value "CJ2305")
      (footprint "eagle-import:SOT-23")
      (libsource (lib "eagle-import") (part "SMD-MOSFET-P-CH-8V-4.1A-CJ2305(SOT-23)"))
    )
    (comp (ref "R1")
      (value "330R")
      (footprint "eagle-import:R0603")
      (fields (field (name "MPN") "RC0603FR-07330RL"))
      (libsource (lib "eagle-import") (part "Seeed-Resistor_474_SMD-RES-330R-1%-1/10W(0603)"))
    )
    (comp (ref "R3")
      (value "330R")
      (footprint "eagle-import:R0603")
      (fields (field (name "MPN") "RC0603FR-07330RL"))
      (libsource (lib "eagle-import") (part "Seeed-Resistor_474_SMD-RES-330R-1%-1/10W(0603)"))
    )
    (comp (ref "R8")
      (value "0R")
      (footprint "eagle-import:R0603")
      (fields (field (name "MPN") "RC0603JR-070RL"))
      (libsource (lib "eagle-import") (part "SMD-RES-0R-5%-1/10W(0603)"))
    )
    (comp (ref "R12")
      (value "0R")
      (footprint "eagle-import:R0603")
      (fields (field (name "MPN") "RC0603JR-070RL"))
      (libsource (lib "eagle-import") (part "SMD-RES-0R-5%-1/10W(0603)"))
    )
    (comp (ref "R13")
      (value "0R")
      (footprint "eagle-import:R0603")
      (fields (field (name "MPN") "RC0603JR-070RL"))
      (libsource (lib "eagle-import") (part "SMD-RES-0R-5%-1/10W(0603)"))
    )
    (comp (ref "R14")
      (value "0R")
      (footprint "eagle-import:R0603")
      (fields (field (name "MPN") "RC0603JR-070RL"))
      (libsource (lib "eagle-import") (part "SMD-RES-0R-5%-1/10W(0603)"))
    )
    (comp (ref "R15")
      (value "0R")
      (footprint "eagle-import:R0603")
      (fields (field (name "MPN") "RC0603JR-070RL"))
      (libsource (lib "eagle-import") (part "SMD-RES-0R-5%-1/10W(0603)"))
    )
    (comp (ref "R43")
      (value "100K 1/10W")
      (footprint "eagle-import:R0603")
      (fields (field (name "MPN") "RC0603JR-07100KL"))
      (libsource (lib "eagle-import") (part "SMD-RES-100K-5%-1/10W(0603)"))
    )
    (comp (ref "R44")
      (value "100K 1/10W")
      (footprint "eagle-import:R0603")
      (fields (field (name "MPN") "RC0603JR-07100KL"))
      (libsource (lib "eagle-import") (part "SMD-RES-100K-5%-1/10W(0603)"))
    )
    (comp (ref "R45")
      (value "100K 1/10W")
      (footprint "eagle-import:R0603")
      (fields (field (name "MPN") "RC0603JR-07100KL"))
      (libsource (lib "eagle-import") (part "SMD-RES-100K-5%-1/10W(0603)"))
    )
    (comp (ref "R46")
      (value "100K 1/10W")
      (footprint "eagle-import:R0603")
      (fields (field (name "MPN") "RC0603JR-07100KL"))
      (libsource (lib "eagle-import") (part "SMD-RES-100K-5%-1/10W(0603)"))
    )
    (comp (ref "TP5")
      (value "TPB2,54")
      (footprint "eagle-import:B2,54")
      (libsource (lib "eagle-import") (part "TPB2,54"))
    )
    (comp (ref "U3")
      (value "LOPY")
      (footprint "eagle-import:LOPY")
      (libsource (lib "eagle-import") (part "LOPY"))
    )
    (comp (ref "U6")
      (value "FT232RL-SSOP28")
      (footprint "eagle-import:SSOP28-0.65-10.2X5.2MM")
      (fields (field (name "MPN") "FT232RL"))
      (libsource (lib "eagle-import") (part "INTERFACE-FT232RL(SSOP28)"))
    )
    (comp (ref "USB3")
      (value "ZX62-B-5PA")
      (footprint "eagle-import:MICRO-USB5+6P-SMD-0.65-AB")
      (libsource (lib "eagle-import") (part "MICRO-USB-SMD(ZX62-B-5PA)"))
    )
    (comp (ref "D4")
      (value "RED-0603")
      (footprint "eagle-import:LED-0603")
      (fields (field (name "MPN") "19-217-R6C-AL1M2VY-3T"))
      (libsource (lib "eagle-import") (part "LED-SMD-RED-DIFFUSED(0603)"))
    )
    (comp (ref "D5")
      (value "RED-0603")
      (footprint "eagle-import:LED-0603")
      (fields (field (name "MPN") "19-217-R6C-AL1M2VY-3T"))
      (libsource (lib "eagle-import") (part "LED-SMD-RED-DIFFUSED(0603)"))
    )
    (comp (ref "D6")
      (value "RED-0603")
      (footprint "eagle-import:LED-0603")
      (fields (field (name "MPN") "19-217-R6C-AL1M2VY-3T"))
      (libsource (lib "eagle-import") (part "LED-SMD-RED-DIFFUSED(0603)"))
    )
    (comp (ref "D8")
      (value "RED-0603")
      (footprint "eagle-import:LED-0603")
      (fields (field (name "MPN") "19-217-R6C-AL1M2VY-3T"))
      (libsource (lib "eagle-import") (part "LED-SMD-RED-DIFFUSED(0603)"))
    )
    (comp (ref "D9")
      (value "RED-0603")
      (footprint "eagle-import:LED-0603")
      (fields (field (name "MPN") "19-217-R6C-AL1M2VY-3T"))
      (libsource (lib "eagle-import") (part "LED-SMD-RED-DIFFUSED(0603)"))
    )
    (comp (ref "D10")
      (value "RED-0603")
      (footprint "eagle-import:LED-0603")
      (fields (field (name "MPN") "19-217-R6C-AL1M2VY-3T"))
      (libsource (lib "eagle-import") (part "LED-SMD-RED-DIFFUSED(0603)"))
    )
    (comp (ref "D11")
      (value "BLUE-0603")
      (footprint "eagle-import:LED-0603")
      (fields (field (name "MPN") "19-217-BHC-ZL1M2RY-3T"))
      (libsource (lib "eagle-import") (part "SMD-LED-CLEAR-BLUE(0603)"))
    )
    (comp (ref "D13")
      (value "RED-0603")
      (footprint "eagle-import:LED-0603")
      (fields (field (name "MPN") "19-217-R6C-AL1M2VY-3T"))
      (libsource (lib "eagle-import") (part "LED-SMD-RED-DIFFUSED(0603)"))
    )
    (comp (ref "D14")
      (value "RED-0603")
      (footprint "eagle-import:LED-0603")
      (fields (field (name "MPN") "19-217-R6C-AL1M2VY-3T"))
      (libsource (lib "eagle-import") (part "LED-SMD-RED-DIFFUSED(0603)"))
    )
    (comp (ref "D22")
      (value "RED-0603")
      (footprint "eagle-import:LED-0603")
      (fields (field (name "MPN") "19-217-R6C-AL1M2VY-3T"))
      (libsource (lib "eagle-import") (part "LED-SMD-RED-DIFFUSED(0603)"))
    )
    (comp (ref "H1")
      (value "MOUNT-HOLE3.0")
      (footprint "eagle-import:3,0")
      (libsource (lib "eagle-import") (part "MOUNT-HOLE3.0"))
    )
    (comp (ref "H2")
      (value "MOUNT-HOLE3.0")
      (footprint "eagle-import:3,0")
      (libsource (lib "eagle-import") (part "MOUNT-HOLE3.0"))
    )
    (comp (ref "H3")
      (value "MOUNT-HOLE3.0")
      (footprint "eagle-import:3,0")
      (libsource (lib "eagle-import") (part "MOUNT-HOLE3.0"))
    )
    (comp (ref "H4")
      (value "MOUNT-HOLE3.0")
      (footprint "eagle-import:3,0")
      (libsource (lib "eagle-import") (part "MOUNT-HOLE3.0"))
    )
    (comp (ref "H5")
      (value "MOUNT-HOLE3.0")
      (footprint "eagle-import:3,0")
      (libsource (lib "eagle-import") (part "MOUNT-HOLE3.0"))
    )
    (comp (ref "H6")
      (value "MOUNT-HOLE3.0")
      (footprint "eagle-import:3,0")
      (libsource (lib "eagle-import") (part "MOUNT-HOLE3.0"))
    )
    (comp (ref "R4")
      (value "220R")
      (footprint "eagle-import:R0603")
      (fields (field (name "MPN") "RC0603JR-07220RL"))
      (libsource (lib "eagle-import") (part "SMD-RES-220R-5%-1/10W(0603)"))
    )
    (comp (ref "R5")
      (value "1K")
      (footprint "eagle-import:R0603")
      (fields (field (name "MPN") "RC0603FR-071KL"))
      (libsource (lib "eagle-import") (part "SMD-RES-1K-1%-1/10W(0603)"))
    )
    (comp (ref "R6")
      (value "220R")
      (footprint "eagle-import:R0603")
      (fields (field (name "MPN") "RC0603JR-07220RL"))
      (libsource (lib "eagle-import") (part "SMD-RES-220R-5%-1/10W(0603)"))
    )
    (comp (ref "R7")
      (value "330R")
      (footprint "eagle-import:R0603")
      (fields (field (name "MPN") "RC0603FR-07330RL"))
      (libsource (lib "eagle-import") (part "Seeed-Resistor_474_SMD-RES-330R-1%-1/10W(0603)"))
    )
    (comp (ref "R9")
      (value "100R")
      (footprint "eagle-import:R0603")
      (fields (field (name "MPN") "RC0603JR-07100RL"))
      (libsource (lib "eagle-import") (part "SMD-RES-100R-5%-1/10W(0603)"))
    )
    (comp (ref "R10")
      (value "100R")
      (footprint "eagle-import:R0603")
      (fields (field (name "MPN") "RC0603JR-07100RL"))
      (libsource (lib "eagle-import") (part "SMD-RES-100R-5%-1/10W(0603)"))
    )
    (comp (ref "R11")
      (value "1K")
      (footprint "eagle-import:R0603")
      (fields (field (name "MPN") "RC0603FR-071KL"))
      (libsource (lib "eagle-import") (part "SMD-RES-1K-1%-1/10W(0603)"))
    )
    (comp (ref "R21")
      (value "220R")
      (footprint "eagle-import:R0603")
      (fields (field (name "MPN") "RC0603JR-07220RL"))
      (libsource (lib "eagle-import") (part "SMD-RES-220R-5%-1/10W(0603)"))
    )
    (comp (ref "R22")
      (value "100R")
      (footprint "eagle-import:R0603")
      (fields (field (name "MPN") "RC0603JR-07100RL"))
      (libsource (lib "eagle-import") (part "SMD-RES-100R-5%-1/10W(0603)"))
    )
    (comp (ref "R35")
      (value "1K")
      (footprint "eagle-import:R0603")
      (fields (field (name "MPN") "RC0603FR-071KL"))
      (libsource (lib "eagle-import") (part "SMD-RES-1K-1%-1/10W(0603)"))
    )
    (comp (ref "SW4")
      (value "MK-12C02 G1.5")
      (footprint "eagle-import:SW7-SMD-L6.7X2.7X3.2MM")
      (libsource (lib "eagle-import") (part "SMD-TOGGLE-SWITCH-ON-ON(3+4P-6.7X2.7MM)"))
    )
    (comp (ref "C5")
      (value "10uf")
      (footprint "eagle-import:AVX-A")
      (fields (field (name "MPN") "TAJA106K010RNJ"))
      (libsource (lib "eagle-import") (part "TANTALUM-SMD-10UF-10V-10%(AVX-A)"))
    )
    (comp (ref "C6")
      (value "100nf")
      (footprint "eagle-import:C0603")
      (fields (field (name "MPN") "CC0603KRX7R9BB104"))
      (libsource (lib "eagle-import") (part "Seeed-Capacitor-2016_450_CERAMIC-100NF-50V-10%-X7R(0603)"))
    )
    (comp (ref "C7")
      (value "100nf")
      (footprint "eagle-import:C0603")
      (fields (field (name "MPN") "CC0603KRX7R9BB104"))
      (libsource (lib "eagle-import") (part "Seeed-Capacitor-2016_450_CERAMIC-100NF-50V-10%-X7R(0603)"))
    )
    (comp (ref "C8")
      (value "10uf")
      (footprint "eagle-import:AVX-A")
      (fields (field (name "MPN") "TAJA106K010RNJ"))
      (libsource (lib "eagle-import") (part "TANTALUM-SMD-10UF-10V-10%(AVX-A)"))
    )
    (comp (ref "U$1")
      (value "MCP3424-E/SL")
      (footprint "eagle-import:SOIC127P600X175-14N")
      (libsource (lib "eagle-import") (part "MCP3424-E/SL"))
    )
    (comp (ref "U$2")
      (value "MCP3424-E/SL")
      (footprint "eagle-import:SOIC127P600X175-14N")
      (libsource (lib "eagle-import") (part "MCP3424-E/SL"))
    )
    (comp (ref "C20")
      (value "100nf")
      (footprint "eagle-import:C0603")
      (fields (field (name "MPN") "CC0603KRX7R9BB104"))
      (libsource (lib "eagle-import") (part "Seeed-Capacitor_464_CERAMIC-100NF-50V-10%-X7R(0603)"))
    )
    (comp (ref "C21")
      (value "100nf")
      (footprint "eagle-import:C0603")
      (fields (field (name "MPN") "CC0603KRX7R9BB104"))
      (libsource (lib "eagle-import") (part "Seeed-Capacitor_464_CERAMIC-100NF-50V-10%-X7R(0603)"))
    )
    (comp (ref "C22")
      (value "100nf")
      (footprint "eagle-import:C0603")
      (fields (field (name "MPN") "CC0603KRX7R9BB104"))
      (libsource (lib "eagle-import") (part "Seeed-Capacitor_464_CERAMIC-100NF-50V-10%-X7R(0603)"))
    )
    (comp (ref "C23")
      (value "100nf")
      (footprint "eagle-import:C0603")
      (fields (field (name "MPN") "CC0603KRX7R9BB104"))
      (libsource (lib "eagle-import") (part "Seeed-Capacitor_464_CERAMIC-100NF-50V-10%-X7R(0603)"))
    )
    (comp (ref "C24")
      (value "100nf")
      (footprint "eagle-import:C0603")
      (fields (field (name "MPN") "CC0603KRX7R9BB104"))
      (libsource (lib "eagle-import") (part "Seeed-Capacitor_464_CERAMIC-100NF-50V-10%-X7R(0603)"))
    )
    (comp (ref "C38")
      (value "100nf")
      (footprint "eagle-import:C0603")
      (fields (field (name "MPN") "CC0603KRX7R9BB104"))
      (libsource (lib "eagle-import") (part "CERAMIC-100NF-50V-10%-X7R(0603)"))
    )
    (comp (ref "C39")
      (value "100nf")
      (footprint "eagle-import:C0603")
      (fields (field (name "MPN") "CC0603KRX7R9BB104"))
      (libsource (lib "eagle-import") (part "CERAMIC-100NF-50V-10%-X7R(0603)"))
    )
    (comp (ref "C40")
      (value "47uf")
      (footprint "eagle-import:AVX-A")
      (fields (field (name "MPN") "TAJA476*006#NJ"))
      (libsource (lib "eagle-import") (part "TANTALUM-SMD-47UF-6.3V(AVX-A)"))
    )
    (comp (ref "C42")
      (value "100nf")
      (footprint "eagle-import:C0603")
      (fields (field (name "MPN") "CC0603KRX7R9BB104"))
      (libsource (lib "eagle-import") (part "CERAMIC-100NF-50V-10%-X7R(0603)"))
    )
    (comp (ref "C43")
      (value "100nf")
      (footprint "eagle-import:C0603")
      (fields (field (name "MPN") "CC0603KRX7R9BB104"))
      (libsource (lib "eagle-import") (part "CERAMIC-100NF-50V-10%-X7R(0603)"))
    )
    (comp (ref "C44")
      (value "47uf")
      (footprint "eagle-import:AVX-A")
      (fields (field (name "MPN") "TAJA476*006#NJ"))
      (libsource (lib "eagle-import") (part "TANTALUM-SMD-47UF-6.3V(AVX-A)"))
    )
    (comp (ref "C46")
      (value "100nf")
      (footprint "eagle-import:C0603")
      (fields (field (name "MPN") "CC0603KRX7R9BB104"))
      (libsource (lib "eagle-import") (part "CERAMIC-100NF-50V-10%-X7R(0603)"))
    )
    (comp (ref "C47")
      (value "100nf")
      (footprint "eagle-import:C0603")
      (fields (field (name "MPN") "CC0603KRX7R9BB104"))
      (libsource (lib "eagle-import") (part "CERAMIC-100NF-50V-10%-X7R(0603)"))
    )
    (comp (ref "C48")
      (value "47uf")
      (footprint "eagle-import:AVX-A")
      (fields (field (name "MPN") "TAJA476*006#NJ"))
      (libsource (lib "eagle-import") (part "TANTALUM-SMD-47UF-6.3V(AVX-A)"))
    )
    (comp (ref "D16")
      (value "BLUE-0603")
      (footprint "eagle-import:LED-0603")
      (fields (field (name "MPN") "19-217-BHC-ZL1M2RY-3T"))
      (libsource (lib "eagle-import") (part "Seeed-LED_472_SMD-LED-CLEAR-BLUE(0603)"))
    )
    (comp (ref "D17")
      (value "GREEN-0603")
      (footprint "eagle-import:LED-0603")
      (fields (field (name "MPN") "19-217-G7C-AN1P2-3T"))
      (libsource (lib "eagle-import") (part "SMD-LED-CLEAR-GREEN(0603)"))
    )
    (comp (ref "D18")
      (value "BLUE-0603")
      (footprint "eagle-import:LED-0603")
      (fields (field (name "MPN") "19-217-BHC-ZL1M2RY-3T"))
      (libsource (lib "eagle-import") (part "Seeed-LED_472_SMD-LED-CLEAR-BLUE(0603)"))
    )
    (comp (ref "D19")
      (value "GREEN-0603")
      (footprint "eagle-import:LED-0603")
      (fields (field (name "MPN") "19-217-G7C-AN1P2-3T"))
      (libsource (lib "eagle-import") (part "SMD-LED-CLEAR-GREEN(0603)"))
    )
    (comp (ref "D20")
      (value "BLUE-0603")
      (footprint "eagle-import:LED-0603")
      (fields (field (name "MPN") "19-217-BHC-ZL1M2RY-3T"))
      (libsource (lib "eagle-import") (part "Seeed-LED_472_SMD-LED-CLEAR-BLUE(0603)"))
    )
    (comp (ref "D21")
      (value "GREEN-0603")
      (footprint "eagle-import:LED-0603")
      (fields (field (name "MPN") "19-217-G7C-AN1P2-3T"))
      (libsource (lib "eagle-import") (part "SMD-LED-CLEAR-GREEN(0603)"))
    )
    (comp (ref "R29")
      (value "330R")
      (footprint "eagle-import:R0603")
      (fields (field (name "MPN") "RC0603FR-07330RL"))
      (libsource (lib "eagle-import") (part "Seeed-Resistor_474_SMD-RES-330R-1%-1/10W(0603)"))
    )
    (comp (ref "R30")
      (value "330R")
      (footprint "eagle-import:R0603")
      (fields (field (name "MPN") "RC0603FR-07330RL"))
      (libsource (lib "eagle-import") (part "Seeed-Resistor_474_SMD-RES-330R-1%-1/10W(0603)"))
    )
    (comp (ref "R31")
      (value "330R")
      (footprint "eagle-import:R0603")
      (fields (field (name "MPN") "RC0603FR-07330RL"))
      (libsource (lib "eagle-import") (part "Seeed-Resistor_474_SMD-RES-330R-1%-1/10W(0603)"))
    )
    (comp (ref "R32")
      (value "330R")
      (footprint "eagle-import:R0603")
      (fields (field (name "MPN") "RC0603FR-07330RL"))
      (libsource (lib "eagle-import") (part "Seeed-Resistor_474_SMD-RES-330R-1%-1/10W(0603)"))
    )
    (comp (ref "R33")
      (value "330R")
      (footprint "eagle-import:R0603")
      (fields (field (name "MPN") "RC0603FR-07330RL"))
      (libsource (lib "eagle-import") (part "Seeed-Resistor_474_SMD-RES-330R-1%-1/10W(0603)"))
    )
    (comp (ref "R34")
      (value "330R")
      (footprint "eagle-import:R0603")
      (fields (field (name "MPN") "RC0603FR-07330RL"))
      (libsource (lib "eagle-import") (part "Seeed-Resistor_474_SMD-RES-330R-1%-1/10W(0603)"))
    )
    (comp (ref "SW5")
      (value "TS-1101F")
      (footprint "eagle-import:SW2-5.0-6.0X3.0X4.3MM")
      (libsource (lib "eagle-import") (part "DIP-BUTTON(2P-6.0X3.0X4.3MM)-TS-1101F"))
    )
    (comp (ref "U4")
      (value "MAX213IDBR")
      (footprint "eagle-import:SOP65P780X200-28N")
      (libsource (lib "eagle-import") (part "MAX213IDBR"))
    )
    (comp (ref "U13")
      (value "FT232RL-SSOP28")
      (footprint "eagle-import:SSOP28-0.65-10.2X5.2MM")
      (fields (field (name "MPN") "FT232RL"))
      (libsource (lib "eagle-import") (part "INTERFACE-FT232RL(SSOP28)"))
    )
    (comp (ref "U14")
      (value "FT232RL-SSOP28")
      (footprint "eagle-import:SSOP28-0.65-10.2X5.2MM")
      (fields (field (name "MPN") "FT232RL"))
      (libsource (lib "eagle-import") (part "INTERFACE-FT232RL(SSOP28)"))
    )
    (comp (ref "U15")
      (value "FT232RL-SSOP28")
      (footprint "eagle-import:SSOP28-0.65-10.2X5.2MM")
      (fields (field (name "MPN") "FT232RL"))
      (libsource (lib "eagle-import") (part "INTERFACE-FT232RL(SSOP28)"))
    )
    (comp (ref "C25")
      (value "10nf")
      (footprint "eagle-import:C0603")
      (fields (field (name "MPN") "CC0603KRX7R9BB103"))
      (libsource (lib "eagle-import") (part "CERAMIC-10NF-50V-10%-X7R(0603)"))
    )
    (comp (ref "C26")
      (value "10uf")
      (footprint "eagle-import:AVX-A")
      (fields (field (name "MPN") "TAJA106K016RNJ"))
      (libsource (lib "eagle-import") (part "TANTALUM-SMD-10UF-16V-10%(AVX-A)"))
    )
    (comp (ref "C28")
      (value "100nf")
      (footprint "eagle-import:C0603")
      (fields (field (name "MPN") "CC0603KRX7R9BB104"))
      (libsource (lib "eagle-import") (part "CERAMIC-100NF-50V-10%-X7R(0603)"))
    )
    (comp (ref "C29")
      (value "100nf")
      (footprint "eagle-import:C0603")
      (fields (field (name "MPN") "CC0603KRX7R9BB104"))
      (libsource (lib "eagle-import") (part "CERAMIC-100NF-50V-10%-X7R(0603)"))
    )
    (comp (ref "C30")
      (value "4.7uf")
      (footprint "eagle-import:AVX-A")
      (fields (field (name "MPN") "TAJA475*016#NJ"))
      (libsource (lib "eagle-import") (part "TANTALUM-SMD-4.7UF-16V(AVX-A)"))
    )
    (comp (ref "C31")
      (value "100nf")
      (footprint "eagle-import:C0805")
      (fields (field (name "MPN") "CC0805KRX7R9BB104"))
      (libsource (lib "eagle-import") (part "CERAMIC-100NF-50V-10%-X7R(0805)"))
    )
    (comp (ref "C32")
      (value "10uf")
      (footprint "eagle-import:C0805")
      (fields (field (name "MPN") "CC0805KKX5R8BB106"))
      (libsource (lib "eagle-import") (part "CERAMIC-10UF-25V-10%-X5R(0805)"))
    )
    (comp (ref "C34")
      (value "10uf")
      (footprint "eagle-import:AVX-A")
      (fields (field (name "MPN") "TAJA106K016RNJ"))
      (libsource (lib "eagle-import") (part "TANTALUM-SMD-10UF-16V-10%(AVX-A)"))
    )
    (comp (ref "C35")
      (value "100nf")
      (footprint "eagle-import:C0603")
      (fields (field (name "MPN") "CC0603KRX7R9BB104"))
      (libsource (lib "eagle-import") (part "CERAMIC-100NF-50V-10%-X7R(0603)"))
    )
    (comp (ref "C36")
      (value "100nf")
      (footprint "eagle-import:C0603")
      (fields (field (name "MPN") "CC0603KRX7R9BB104"))
      (libsource (lib "eagle-import") (part "CERAMIC-100NF-50V-10%-X7R(0603)"))
    )
    (comp (ref "D7")
      (value "BLUE-0603")
      (footprint "eagle-import:LED-0603")
      (fields (field (name "MPN") "19-217-BHC-ZL1M2RY-3T"))
      (libsource (lib "eagle-import") (part "Seeed-LED_472_SMD-LED-CLEAR-BLUE(0603)"))
    )
    (comp (ref "D12")
      (value "YELLOW-WHITE-0603")
      (footprint "eagle-import:LED-0603")
      (fields (field (name "MPN") "ADL-0603W"))
      (libsource (lib "eagle-import") (part "SMD-LED-YELLOW-WHITE(0603)"))
    )
    (comp (ref "D15")
      (value "GREEN-0603")
      (footprint "eagle-import:LED-0603")
      (fields (field (name "MPN") "19-217-G7C-AN1P2-3T"))
      (libsource (lib "eagle-import") (part "SMD-LED-CLEAR-GREEN(0603)"))
    )
    (comp (ref "L4")
      (value "330R-1500MA")
      (footprint "eagle-import:L0805")
      (fields (field (name "MPN") "BLM21PG331SN1D"))
      (libsource (lib "eagle-import") (part "SMD-FERRITE-BEAD-330R-1500MA(0805)'0805'"))
    )
    (comp (ref "R23")
      (value "330R")
      (footprint "eagle-import:R0603")
      (fields (field (name "MPN") "RC0603FR-07330RL"))
      (libsource (lib "eagle-import") (part "Seeed-Resistor_474_SMD-RES-330R-1%-1/10W(0603)"))
    )
    (comp (ref "R24")
      (value "330R")
      (footprint "eagle-import:R0603")
      (fields (field (name "MPN") "RC0603FR-07330RL"))
      (libsource (lib "eagle-import") (part "Seeed-Resistor_474_SMD-RES-330R-1%-1/10W(0603)"))
    )
    (comp (ref "R25")
      (value "120R")
      (footprint "eagle-import:R0603")
      (libsource (lib "eagle-import") (part "R-EU_R0603"))
    )
    (comp (ref "R27")
      (value "10K")
      (footprint "eagle-import:R0603")
      (fields (field (name "MPN") "RC0603FR-0710KL"))
      (libsource (lib "eagle-import") (part "SMD-RES-10K-1%-1/10W(0603)"))
    )
    (comp (ref "R28")
      (value "2.7K 1/16W")
      (footprint "eagle-import:R0402")
      (fields (field (name "MPN") "RC0402FR-072K7L"))
      (libsource (lib "eagle-import") (part "SMD-RES-2.7K-1%-1/16W(0402)"))
    )
    (comp (ref "R42")
      (value "330R")
      (footprint "eagle-import:R0603")
      (fields (field (name "MPN") "RC0603FR-07330RL"))
      (libsource (lib "eagle-import") (part "SMD-RES-330R-1%-1/10W(0603)"))
    )
    (comp (ref "SW1")
      (value "MK-12C02 G1.5")
      (footprint "eagle-import:SW7-SMD-L6.7X2.7X3.2MM")
      (libsource (lib "eagle-import") (part "SMD-TOGGLE-SWITCH-ON-ON(3+4P-6.7X2.7MM)"))
    )
    (comp (ref "TP13")
      (value "TPB2,54")
      (footprint "eagle-import:B2,54")
      (libsource (lib "eagle-import") (part "TPB2,54"))
    )
    (comp (ref "TP14")
      (value "TPB2,54")
      (footprint "eagle-import:B2,54")
      (libsource (lib "eagle-import") (part "TPB2,54"))
    )
    (comp (ref "TP15")
      (value "TPB2,54")
      (footprint "eagle-import:B2,54")
      (libsource (lib "eagle-import") (part "TPB2,54"))
    )
    (comp (ref "U$6")
      (value "FE1.1S")
      (footprint "eagle-import:FE1.1S_SSOP-28")
      (libsource (lib "eagle-import") (part "FE1.1S"))
    )
    (comp (ref "U5")
      (value "FT232RL-SSOP28")
      (footprint "eagle-import:SSOP28-0.65-10.2X5.2MM")
      (fields (field (name "MPN") "FT232RL"))
      (libsource (lib "eagle-import") (part "INTERFACE-FT232RL(SSOP28)"))
    )
    (comp (ref "U12")
      (value "SP483ECN-L")
      (footprint "eagle-import:SOIC127P600X175-8N")
      (libsource (lib "eagle-import") (part "SP483ECN-L"))
    )
    (comp (ref "USB1")
      (value "ZX62-B-5PA")
      (footprint "eagle-import:MICRO-USB5+6P-SMD-0.65-AB")
      (libsource (lib "eagle-import") (part "MICRO-USB-SMD(ZX62-B-5PA)"))
    )
    (comp (ref "Y2")
      (value "12MHZ")
      (footprint "eagle-import:X2-SMD-5.0X3.2X1.3MM")
      (fields (field (name "MPN") "5032/2P"))
      (libsource (lib "eagle-import") (part "SMD-CRYSTAL-12MHZ-20PF-20PPM-40R(2P-5.0X3.2MM)"))
    )
    (comp (ref "BAT1")
      (value "cr1220")
      (footprint "eagle-import:BAT2P-13.5-CR1220")
      (libsource (lib "eagle-import") (part "DIP-BATTERY-CELL-HOLDER(1220)"))
    )
    (comp (ref "C1")
      (value "10pf")
      (footprint "eagle-import:C0603")
      (fields (field (name "MPN") "CC0603JRNPO9BN100"))
      (libsource (lib "eagle-import") (part "CERAMIC-10PF-50V-5%-NPO(0603)"))
    )
    (comp (ref "C2")
      (value "100nf")
      (footprint "eagle-import:C0603")
      (fields (field (name "MPN") "CC0603KRX7R9BB104"))
      (libsource (lib "eagle-import") (part "Seeed-Capacitor-2016_450_CERAMIC-100NF-50V-10%-X7R(0603)"))
    )
    (comp (ref "C3")
      (value "10pf")
      (footprint "eagle-import:C0603")
      (fields (field (name "MPN") "CC0603JRNPO9BN100"))
      (libsource (lib "eagle-import") (part "CERAMIC-10PF-50V-5%-NPO(0603)"))
    )
    (comp (ref "C11")
      (value "100nf")
      (footprint "eagle-import:C0603")
      (fields (field (name "MPN") "CC0603KRX7R9BB104"))
      (libsource (lib "eagle-import") (part "Seeed-Capacitor-2016_450_CERAMIC-100NF-50V-10%-X7R(0603)"))
    )
    (comp (ref "C13")
      (value "100nf")
      (footprint "eagle-import:C0603")
      (fields (field (name "MPN") "CC0603KRX7R9BB104"))
      (libsource (lib "eagle-import") (part "Seeed-Capacitor-2016_450_CERAMIC-100NF-50V-10%-X7R(0603)"))
    )
    (comp (ref "C19")
      (value "100nf")
      (footprint "eagle-import:C0603")
      (fields (field (name "MPN") "CC0603KRX7R9BB104"))
      (libsource (lib "eagle-import") (part "CERAMIC-100NF-50V-10%-X7R(0603)"))
    )
    (comp (ref "F60")
      (value "SMD1206R500SF")
      (footprint "eagle-import:F1206")
      (libsource (lib "eagle-import") (part "SMD-PPTC-500MA(1206)"))
    )
    (comp (ref "F62")
      (value "SMD1206R500SF")
      (footprint "eagle-import:F1206")
      (libsource (lib "eagle-import") (part "SMD-PPTC-500MA(1206)"))
    )
    (comp (ref "J5")
      (value "16p-2.54")
      (footprint "eagle-import:H16-2.54")
      (fields (field (name "MPN") "P125-1116A0BS116AX"))
      (libsource (lib "eagle-import") (part "DIP-BLACK-MALE-HEADER-VERT(16P-2.54)"))
    )
    (comp (ref "J6")
      (value "16p-2.54")
      (footprint "eagle-import:H16-2.54")
      (fields (field (name "MPN") "P125-1116A0BS116AX"))
      (libsource (lib "eagle-import") (part "DIP-BLACK-MALE-HEADER-VERT(16P-2.54)"))
    )
    (comp (ref "J8")
      (value "2p-2.54")
      (footprint "eagle-import:H2-2.54")
      (fields (field (name "MPN") "RF130-1023ABS0741"))
      (libsource (lib "eagle-import") (part "DIP-BLACK-ROUND-FEMALE-HEADER-VERT(2P-2.54)"))
    )
    (comp (ref "J10")
      (value "16p-2.54")
      (footprint "eagle-import:H16-2.54")
      (fields (field (name "MPN") "P125-1116A0BS116AX"))
      (libsource (lib "eagle-import") (part "DIP-BLACK-MALE-HEADER-VERT(16P-2.54)"))
    )
    (comp (ref "J11")
      (value "16p-2.54")
      (footprint "eagle-import:H16-2.54")
      (fields (field (name "MPN") "P125-1116A0BS116AX"))
      (libsource (lib "eagle-import") (part "DIP-BLACK-MALE-HEADER-VERT(16P-2.54)"))
    )
    (comp (ref "PCB1")
      (value "RPI2")
      (footprint "eagle-import:RPI2")
      (libsource (lib "eagle-import") (part "RPI2"))
    )
    (comp (ref "Q1")
      (value "32.768khZ@6Pf")
      (footprint "eagle-import:85SMX")
      (libsource (lib "eagle-import") (part "LFXTAL016178"))
    )
    (comp (ref "R2")
      (value "10K 1/10W")
      (footprint "eagle-import:R0603")
      (fields (field (name "MPN") "RC0603JR-0710KL"))
      (libsource (lib "eagle-import") (part "SMD-RES-10K-5%-1/10W(0603)"))
    )
    (comp (ref "R16")
      (value "10K")
      (footprint "eagle-import:R0603")
      (fields (field (name "MPN") "RC0603FR-0710KL"))
      (libsource (lib "eagle-import") (part "SMD-RES-10K-1%-1/10W(0603)"))
    )
    (comp (ref "R17")
      (value "0R")
      (footprint "eagle-import:R0603")
      (fields (field (name "MPN") "RC0603JR-070RL"))
      (libsource (lib "eagle-import") (part "Seeed-Resistor_474_SMD-RES-0R-5%-1/10W(0603)"))
    )
    (comp (ref "R18")
      (value "10K")
      (footprint "eagle-import:R0603")
      (fields (field (name "MPN") "RC0603FR-0710KL"))
      (libsource (lib "eagle-import") (part "SMD-RES-10K-1%-1/10W(0603)"))
    )
    (comp (ref "R19")
      (value "10K")
      (footprint "eagle-import:R0603")
      (fields (field (name "MPN") "RC0603FR-0710KL"))
      (libsource (lib "eagle-import") (part "SMD-RES-10K-1%-1/10W(0603)"))
    )
    (comp (ref "R36")
      (value "1K")
      (footprint "eagle-import:R0603")
      (fields (field (name "MPN") "RC0603FR-071KL"))
      (libsource (lib "eagle-import") (part "Seeed-Resistor_474_SMD-RES-1K-1%-1/10W(0603)"))
    )
    (comp (ref "R37")
      (value "3.9K")
      (footprint "eagle-import:R0603")
      (fields (field (name "MPN") "RC0603JR-073K9L"))
      (libsource (lib "eagle-import") (part "SMD-RES-3.9K-5%-1/10W(0603)"))
    )
    (comp (ref "R38")
      (value "3.9K")
      (footprint "eagle-import:R0603")
      (fields (field (name "MPN") "RC0603JR-073K9L"))
      (libsource (lib "eagle-import") (part "SMD-RES-3.9K-5%-1/10W(0603)"))
    )
    (comp (ref "R41")
      (value "0R")
      (footprint "eagle-import:R0603")
      (fields (field (name "MPN") "RC0603JR-070RL"))
      (libsource (lib "eagle-import") (part "Seeed-Resistor_474_SMD-RES-0R-5%-1/10W(0603)"))
    )
    (comp (ref "TP6")
      (value "TPB2,54")
      (footprint "eagle-import:B2,54")
      (libsource (lib "eagle-import") (part "TPB2,54"))
    )
    (comp (ref "TP7")
      (value "TPB2,54")
      (footprint "eagle-import:B2,54")
      (libsource (lib "eagle-import") (part "TPB2,54"))
    )
    (comp (ref "TP17")
      (value "TPB2,54")
      (footprint "eagle-import:B2,54")
      (libsource (lib "eagle-import") (part "TPB2,54"))
    )
    (comp (ref "U$7")
      (value "TEMP-HUM-SENSOR-DHT22")
      (footprint "eagle-import:TEMP-HUM-SENSOR-DHT22")
      (libsource (lib "eagle-import") (part "TEMP-HUM-SENSOR-DHT22"))
    )
    (comp (ref "U1")
      (value "MCP23017-E/SO")
      (footprint "eagle-import:SOIC127P1032X265-28N")
      (libsource (lib "eagle-import") (part "MCP23017-E/SO"))
    )
    (comp (ref "U2")
      (value "MCP79412-I/SN")
      (footprint "eagle-import:SOIC127P600X175-8N")
      (libsource (lib "eagle-import") (part "MCP79412-I/SN"))
    )
    (comp (ref "U8")
      (value "BR24G32-3")
      (footprint "eagle-import:SOP8")
      (libsource (lib "eagle-import") (part "BR24G32-3"))
    )
    (comp (ref "U10")
      (value "74HCT139D")
      (footprint "eagle-import:SOIC127P600X175-16N")
      (libsource (lib "eagle-import") (part "74HCT139D"))
    )
    (comp (ref "C4")
      (value "10uf")
      (footprint "eagle-import:AVX-A")
      (fields (field (name "MPN") "TAJA106K010RNJ"))
      (libsource (lib "eagle-import") (part "Seeed-Capacitor_464_TANTALUM-SMD-10UF-10V-10%(AVX-A)"))
    )
    (comp (ref "C10")
      (value "10uf")
      (footprint "eagle-import:AVX-A")
      (fields (field (name "MPN") "TAJA106K010RNJ"))
      (libsource (lib "eagle-import") (part "Seeed-Capacitor_464_TANTALUM-SMD-10UF-10V-10%(AVX-A)"))
    )
    (comp (ref "C12")
      (value "100nf")
      (footprint "eagle-import:C0603")
      (fields (field (name "MPN") "CC0603KRX7R9BB104"))
      (libsource (lib "eagle-import") (part "Seeed-Capacitor-2016_450_CERAMIC-100NF-50V-10%-X7R(0603)"))
    )
    (comp (ref "C14")
      (value "100nf")
      (footprint "eagle-import:C0603")
      (fields (field (name "MPN") "CC0603KRX7R9BB104"))
      (libsource (lib "eagle-import") (part "Seeed-Capacitor-2016_450_CERAMIC-100NF-50V-10%-X7R(0603)"))
    )
    (comp (ref "C18")
      (value "100nf")
      (footprint "eagle-import:C0603")
      (fields (field (name "MPN") "CC0603KRX7R9BB104"))
      (libsource (lib "eagle-import") (part "Seeed-Capacitor_464_CERAMIC-100NF-50V-10%-X7R(0603)"))
    )
    (comp (ref "D1")
      (value "28V-5A")
      (footprint "eagle-import:DO-214AA")
      (fields (field (name "MPN") "SS54B"))
      (libsource (lib "eagle-import") (part "SMD-DIODE-SCHOTTKY-28V-5A(DO-214AA)"))
    )
    (comp (ref "F1")
      (value "307010005_DIP_PPTC_4A_0310")
      (footprint "eagle-import:TH_5MM_14MM")
      (libsource (lib "eagle-import") (part "307010005_DIP_PPTC_4A_0310"))
    )
    (comp (ref "J1")
      (value "DC-044-A")
      (footprint "eagle-import:DCJ3P-11.6X9.6X7.0MM")
      (fields (field (name "MPN") "JACK-DC-044-A"))
      (libsource (lib "eagle-import") (part "JACK-DC-044-A"))
    )
    (comp (ref "L2")
      (value "330R-1500MA")
      (footprint "eagle-import:L0805")
      (fields (field (name "MPN") "BLM21PG331SN1D"))
      (libsource (lib "eagle-import") (part "Seeed-Inductor-2016_457_SMD-FERRITE-BEAD-330R-1500MA(0805)'0805'"))
    )
    (comp (ref "L3")
      (value "330R-1500MA")
      (footprint "eagle-import:L0805")
      (fields (field (name "MPN") "BLM21PG331SN1D"))
      (libsource (lib "eagle-import") (part "Seeed-Inductor-2016_457_SMD-FERRITE-BEAD-330R-1500MA(0805)'0805'"))
    )
    (comp (ref "Q2")
      (value "SSM3J328R,LF")
      (footprint "eagle-import:SOT-23")
      (libsource (lib "eagle-import") (part "SMD-MOSFET-P-CH-20V-6A-SSM3J328R(SOT-23)"))
    )
    (comp (ref "Q4")
      (value "BSS138W-7-F")
      (footprint "eagle-import:SOT-23")
      (libsource (lib "eagle-import") (part "Seeed-Transistor_477_SMD-MOSFET-N-CH-50V-200MA-BSS138W-7-F(SOT-23)"))
    )
    (comp (ref "Q5")
      (value "SSM3J328R,LF")
      (footprint "eagle-import:SOT-23")
      (libsource (lib "eagle-import") (part "SMD-MOSFET-P-CH-20V-6A-SSM3J328R(SOT-23)"))
    )
    (comp (ref "R20")
      (value "15K 1/10W")
      (footprint "eagle-import:R0603")
      (fields (field (name "MPN") "RC0603FR-0715KL"))
      (libsource (lib "eagle-import") (part "SMD-RES-15K-1%-1/10W(0603)"))
    )
    (comp (ref "R39")
      (value "100K 1/10W")
      (footprint "eagle-import:R0603")
      (fields (field (name "MPN") "RC0603JR-07100KL"))
      (libsource (lib "eagle-import") (part "Seeed-Resistor_474_SMD-RES-100K-5%-1/10W(0603)"))
    )
    (comp (ref "R40")
      (value "100K 1/10W")
      (footprint "eagle-import:R0603")
      (fields (field (name "MPN") "RC0603JR-07100KL"))
      (libsource (lib "eagle-import") (part "Seeed-Resistor_474_SMD-RES-100K-5%-1/10W(0603)"))
    )
    (comp (ref "SW3")
      (value "MK-12C02 G1.5")
      (footprint "eagle-import:SW7-SMD-L6.7X2.7X3.2MM")
      (libsource (lib "eagle-import") (part "SMD-TOGGLE-SWITCH-ON-ON(3+4P-6.7X2.7MM)"))
    )
    (comp (ref "TP1")
      (value "TPB2,54")
      (footprint "eagle-import:B2,54")
      (libsource (lib "eagle-import") (part "TPB2,54"))
    )
    (comp (ref "TP2")
      (value "TPB2,54")
      (footprint "eagle-import:B2,54")
      (libsource (lib "eagle-import") (part "TPB2,54"))
    )
    (comp (ref "TP3")
      (value "TPB2,54")
      (footprint "eagle-import:B2,54")
      (libsource (lib "eagle-import") (part "TPB2,54"))
    )
    (comp (ref "TP4")
      (value "TPB2,54")
      (footprint "eagle-import:B2,54")
      (libsource (lib "eagle-import") (part "TPB2,54"))
    )
    (comp (ref "TP8")
      (value "TPB2,54")
      (footprint "eagle-import:B2,54")
      (libsource (lib "eagle-import") (part "TPB2,54"))
    )
    (comp (ref "TP9")
      (value "TPB2,54")
      (footprint "eagle-import:B2,54")
      (libsource (lib "eagle-import") (part "TPB2,54"))
    )
    (comp (ref "TP10")
      (value "TPB2,54")
      (footprint "eagle-import:B2,54")
      (libsource (lib "eagle-import") (part "TPB2,54"))
    )
    (comp (ref "TP11")
      (value "TPB2,54")
      (footprint "eagle-import:B2,54")
      (libsource (lib "eagle-import") (part "TPB2,54"))
    )
    (comp (ref "TP12")
      (value "TPB2,54")
      (footprint "eagle-import:B2,54")
      (libsource (lib "eagle-import") (part "TPB2,54"))
    )
    (comp (ref "TP16")
      (value "TPB2,54")
      (footprint "eagle-import:B2,54")
      (libsource (lib "eagle-import") (part "TPB2,54"))
    )
    (comp (ref "U$3")
      (value "C106DG")
      (footprint "eagle-import:TO-225AA")
      (libsource (lib "eagle-import") (part "C106DG"))
    )
    (comp (ref "U$4")
      (value "MIC29300")
      (footprint "eagle-import:TO-263")
      (libsource (lib "eagle-import") (part "MIC29300"))
    )
    (comp (ref "U$5")
      (value "DC-DC-STEP-DOWN-LM2596")
      (footprint "eagle-import:DC-DC-STEP-DOWN-LM2596")
      (libsource (lib "eagle-import") (part "DC-DC-STEP-DOWN-LM2596"))
    )
    (comp (ref "U11")
      (value "BZX84C30")
      (footprint "eagle-import:SOT91P240X110-3N")
      (libsource (lib "eagle-import") (part "BZX84C30"))
    )
  )
  (nets
    (net (code "1") (name "+3V3") (class "Default")
      (node (ref "C11") (pin "2") (pinfunction "2_2") (pintype "passive"))
      (node (ref "C12") (pin "2") (pinfunction "2_2") (pintype "passive"))
      (node (ref "C2") (pin "2") (pinfunction "2_2") (pintype "passive"))
      (node (ref "F10") (pin "1") (pinfunction "1_1") (pintype "bidirectional"))
      (node (ref "F12") (pin "1") (pinfunction "1_1") (pintype "bidirectional"))
      (node (ref "F14") (pin "1") (pinfunction "1_1") (pintype "bidirectional"))
      (node (ref "F16") (pin "1") (pinfunction "1_1") (pintype "bidirectional"))
      (node (ref "F18") (pin "1") (pinfunction "1_1") (pintype "bidirectional"))
      (node (ref "F20") (pin "1") (pinfunction "1_1") (pintype "bidirectional"))
      (node (ref "F22") (pin "1") (pinfunction "1_1") (pintype "bidirectional"))
      (node (ref "F23") (pin "1") (pinfunction "1_1") (pintype "bidirectional"))
      (node (ref "F25") (pin "1") (pinfunction "1_1") (pintype "bidirectional"))
      (node (ref "F27") (pin "1") (pinfunction "1_1") (pintype "bidirectional"))
      (node (ref "F29") (pin "1") (pinfunction "1_1") (pintype "bidirectional"))
      (node (ref "F3") (pin "1") (pinfunction "1_1") (pintype "bidirectional"))
      (node (ref "F31") (pin "1") (pinfunction "1_1") (pintype "bidirectional"))
      (node (ref "F33") (pin "1") (pinfunction "1_1") (pintype "bidirectional"))
      (node (ref "F35") (pin "1") (pinfunction "1_1") (pintype "bidirectional"))
      (node (ref "F37") (pin "1") (pinfunction "1_1") (pintype "bidirectional"))
      (node (ref "F47") (pin "1") (pinfunction "1_1") (pintype "bidirectional"))
      (node (ref "F49") (pin "1") (pinfunction "1_1") (pintype "bidirectional"))
      (node (ref "F51") (pin "1") (pinfunction "1_1") (pintype "bidirectional"))
      (node (ref "F53") (pin "1") (pinfunction "1_1") (pintype "bidirectional"))
      (node (ref "F55") (pin "1") (pinfunction "1_1") (pintype "bidirectional"))
      (node (ref "F6") (pin "1") (pinfunction "1_1") (pintype "bidirectional"))
      (node (ref "F62") (pin "1") (pinfunction "1_1") (pintype "bidirectional"))
      (node (ref "F8") (pin "1") (pinfunction "1_1") (pintype "bidirectional"))
      (node (ref "L2") (pin "1") (pinfunction "1_1") (pintype "passive"))
      (node (ref "PCB1") (pin "P$1") (pinfunction "3V3_P$1") (pintype "bidirectional"))
      (node (ref "PCB1") (pin "P$17") (pinfunction "3V3_P$17") (pintype "bidirectional"))
      (node (ref "R16") (pin "2") (pinfunction "2_2") (pintype "passive"))
      (node (ref "R18") (pin "2") (pinfunction "2_2") (pintype "passive"))
      (node (ref "R19") (pin "2") (pinfunction "2_2") (pintype "passive"))
      (node (ref "R2") (pin "2") (pinfunction "2_2") (pintype "passive"))
      (node (ref "R9") (pin "2") (pinfunction "2_2") (pintype "passive"))
      (node (ref "TP2") (pin "TP") (pinfunction "TP_TP") (pintype "input"))
      (node (ref "U$7") (pin "1") (pinfunction "VDD_1") (pintype "power_in"))
      (node (ref "U1") (pin "9") (pinfunction "VDD_9") (pintype "power_in"))
      (node (ref "U2") (pin "8") (pinfunction "VCC_8") (pintype "power_in"))
    )
    (net (code "2") (name "+3V3_SMOOTH") (class "Default")
      (node (ref "C14") (pin "2") (pinfunction "2_2") (pintype "passive"))
      (node (ref "C5") (pin "+") (pinfunction "+_+") (pintype "passive"))
      (node (ref "C6") (pin "2") (pinfunction "2_2") (pintype "passive"))
      (node (ref "C7") (pin "2") (pinfunction "2_2") (pintype "passive"))
      (node (ref "C8") (pin "+") (pinfunction "+_+") (pintype "passive"))
      (node (ref "F39") (pin "1") (pinfunction "1_1") (pintype "bidirectional"))
      (node (ref "F41") (pin "1") (pinfunction "1_1") (pintype "bidirectional"))
      (node (ref "F43") (pin "1") (pinfunction "1_1") (pintype "bidirectional"))
      (node (ref "F45") (pin "1") (pinfunction "1_1") (pintype "bidirectional"))
      (node (ref "L2") (pin "2") (pinfunction "2_2") (pintype "passive"))
      (node (ref "R10") (pin "2") (pinfunction "2_2") (pintype "passive"))
      (node (ref "TP3") (pin "TP") (pinfunction "TP_TP") (pintype "input"))
      (node (ref "U$1") (pin "6") (pinfunction "VDD_6") (pintype "power_in"))
      (node (ref "U$2") (pin "6") (pinfunction "VDD_6") (pintype "power_in"))
    )
    (net (code "3") (name "+5V") (class "Default")
      (node (ref "C10") (pin "+") (pinfunction "+_+") (pintype "passive"))
      (node (ref "F74") (pin "1") (pinfunction "1_1") (pintype "bidirectional"))
      (node (ref "F76") (pin "1") (pinfunction "1_1") (pintype "bidirectional"))
      (node (ref "F78") (pin "1") (pinfunction "1_1") (pintype "bidirectional"))
      (node (ref "F80") (pin "1") (pinfunction "1_1") (pintype "bidirectional"))
      (node (ref "F82") (pin "1") (pinfunction "1_1") (pintype "bidirectional"))
      (node (ref "Q2") (pin "3") (pinfunction "D_3") (pintype "passive"))
      (node (ref "R39") (pin "2") (pinfunction "2_2") (pintype "passive"))
      (node (ref "R6") (pin "2") (pinfunction "2_2") (pintype "passive"))
      (node (ref "TP1") (pin "TP") (pinfunction "TP_TP") (pintype "input"))
      (node (ref "U$4") (pin "3") (pinfunction "VOUT_3") (pintype "output"))
      (node (ref "U3") (pin "P$28") (pinfunction "5V_P$28") (pintype "power_in"))
    )
    (net (code "4") (name "+24V") (class "Default")
      (node (ref "D1") (pin "-") (pinfunction "-_-") (pintype "passive"))
      (node (ref "R5") (pin "2") (pinfunction "2_2") (pintype "passive"))
      (node (ref "U$3") (pin "1") (pinfunction "A_1") (pintype "passive"))
      (node (ref "U$5") (pin "IN+") (pinfunction "IN+_IN+") (pintype "bidirectional"))
      (node (ref "U11") (pin "3") (pinfunction "CATHODE_3") (pintype "passive"))
    )
    (net (code "5") (name "+24V_UNREG_IN") (class "Default")
      (node (ref "F1") (pin "P$1") (pinfunction "P$1_P$1") (pintype "passive"))
      (node (ref "J1") (pin "+") (pinfunction "+_+") (pintype "bidirectional"))
    )
    (net (code "6") (name "3V3") (class "Default")
      (node (ref "C19") (pin "1") (pinfunction "1_1") (pintype "passive"))
      (node (ref "R36") (pin "2") (pinfunction "2_2") (pintype "passive"))
      (node (ref "R37") (pin "2") (pinfunction "2_2") (pintype "passive"))
      (node (ref "R38") (pin "2") (pinfunction "2_2") (pintype "passive"))
      (node (ref "U8") (pin "8") (pinfunction "VCC_8") (pintype "power_in"))
    )
    (net (code "7") (name "5V35") (class "Default")
      (node (ref "C4") (pin "+") (pinfunction "+_+") (pintype "passive"))
      (node (ref "R7") (pin "2") (pinfunction "2_2") (pintype "passive"))
      (node (ref "TP4") (pin "TP") (pinfunction "TP_TP") (pintype "input"))
      (node (ref "U$4") (pin "1") (pinfunction "VIN_1") (pintype "input"))
      (node (ref "U$5") (pin "OUT+") (pinfunction "OUT+_OUT+") (pintype "bidirectional"))
    )
    (net (code "8") (name "5V_USB_HUB") (class "Default")
      (node (ref "C25") (pin "2") (pinfunction "2_2") (pintype "passive"))
      (node (ref "L4") (pin "1") (pinfunction "1_1") (pintype "passive"))
      (node (ref "R35") (pin "2") (pinfunction "2_2") (pintype "passive"))
      (node (ref "USB1") (pin "1") (pinfunction "VBUS_1") (pintype "power_in"))
    )
    (net (code "9") (name "5V_USB_HUB_FERRITE") (class "Default")
      (node (ref "C20") (pin "2") (pinfunction "2_2") (pintype "passive"))
      (node (ref "C23") (pin "2") (pinfunction "2_2") (pintype "passive"))
      (node (ref "C28") (pin "2") (pinfunction "2_2") (pintype "passive"))
      (node (ref "C30") (pin "+") (pinfunction "+_+") (pintype "passive"))
      (node (ref "C31") (pin "2") (pinfunction "2_2") (pintype "passive"))
      (node (ref "C32") (pin "1") (pinfunction "1_1") (pintype "passive"))
      (node (ref "C38") (pin "2") (pinfunction "2_2") (pintype "passive"))
      (node (ref "C40") (pin "+") (pinfunction "+_+") (pintype "passive"))
      (node (ref "C42") (pin "2") (pinfunction "2_2") (pintype "passive"))
      (node (ref "C44") (pin "+") (pinfunction "+_+") (pintype "passive"))
      (node (ref "C46") (pin "2") (pinfunction "2_2") (pintype "passive"))
      (node (ref "C48") (pin "+") (pinfunction "+_+") (pintype "passive"))
      (node (ref "L4") (pin "2") (pinfunction "2_2") (pintype "passive"))
      (node (ref "R27") (pin "2") (pinfunction "2_2") (pintype "passive"))
      (node (ref "SW5") (pin "2") (pinfunction "2_2") (pintype "bidirectional"))
      (node (ref "U$6") (pin "20") (pinfunction "VDD5_20") (pintype "bidirectional"))
      (node (ref "U12") (pin "8") (pinfunction "VCC_8") (pintype "power_in"))
      (node (ref "U13") (pin "20") (pinfunction "VCC_20") (pintype "input"))
      (node (ref "U13") (pin "4") (pinfunction "VCCIO_4") (pintype "input"))
      (node (ref "U14") (pin "20") (pinfunction "VCC_20") (pintype "input"))
      (node (ref "U14") (pin "4") (pinfunction "VCCIO_4") (pintype "input"))
      (node (ref "U15") (pin "20") (pinfunction "VCC_20") (pintype "input"))
      (node (ref "U15") (pin "4") (pinfunction "VCCIO_4") (pintype "input"))
      (node (ref "U4") (pin "11") (pinfunction "VCC_11") (pintype "power_in"))
      (node (ref "U4") (pin "24") (pinfunction "EN_24") (pintype "input"))
      (node (ref "U4") (pin "25") (pinfunction "~{SHDN}_25") (pintype "input"))
      (node (ref "U5") (pin "20") (pinfunction "VCC_20") (pintype "input"))
      (node (ref "U5") (pin "4") (pinfunction "VCCIO_4") (pintype "input"))
    )
    (net (code "10") (name "ADC1+") (class "Default")
      (node (ref "PI_ADC_1") (pin "3") (pinfunction "S_3") (pintype "passive"))
      (node (ref "U$1") (pin "1") (pinfunction "CH1+_1") (pintype "input"))
    )
    (net (code "11") (name "ADC1-") (class "Default")
      (node (ref "PI_ADC_1") (pin "4") (pinfunction "S_4") (pintype "passive"))
      (node (ref "U$1") (pin "2") (pinfunction "CH1-_2") (pintype "input"))
    )
    (net (code "12") (name "ADC2+") (class "Default")
      (node (ref "PI_ADC_1") (pin "5") (pinfunction "S_5") (pintype "passive"))
      (node (ref "U$1") (pin "3") (pinfunction "CH2+_3") (pintype "input"))
    )
    (net (code "13") (name "ADC2-") (class "Default")
      (node (ref "PI_ADC_1") (pin "6") (pinfunction "S_6") (pintype "passive"))
      (node (ref "U$1") (pin "4") (pinfunction "CH2-_4") (pintype "input"))
    )
    (net (code "14") (name "ADC3+") (class "Default")
      (node (ref "PI_ADC_2") (pin "3") (pinfunction "S_3") (pintype "passive"))
      (node (ref "U$1") (pin "11") (pinfunction "CH3+_11") (pintype "input"))
    )
    (net (code "15") (name "ADC3-") (class "Default")
      (node (ref "PI_ADC_2") (pin "4") (pinfunction "S_4") (pintype "passive"))
      (node (ref "U$1") (pin "12") (pinfunction "CH3-_12") (pintype "input"))
    )
    (net (code "16") (name "ADC4+") (class "Default")
      (node (ref "PI_ADC_2") (pin "5") (pinfunction "S_5") (pintype "passive"))
      (node (ref "U$1") (pin "13") (pinfunction "CH4+_13") (pintype "input"))
    )
    (net (code "17") (name "ADC4-") (class "Default")
      (node (ref "PI_ADC_2") (pin "6") (pinfunction "S_6") (pintype "passive"))
      (node (ref "U$1") (pin "14") (pinfunction "CH4-_14") (pintype "input"))
    )
    (net (code "18") (name "ADC5+") (class "Default")
      (node (ref "PI_ADC_3") (pin "3") (pinfunction "S_3") (pintype "passive"))
      (node (ref "U$2") (pin "1") (pinfunction "CH1+_1") (pintype "input"))
    )
    (net (code "19") (name "ADC5-") (class "Default")
      (node (ref "PI_ADC_3") (pin "4") (pinfunction "S_4") (pintype "passive"))
      (node (ref "U$2") (pin "2") (pinfunction "CH1-_2") (pintype "input"))
    )
    (net (code "20") (name "ADC6+") (class "Default")
      (node (ref "PI_ADC_3") (pin "5") (pinfunction "S_5") (pintype "passive"))
      (node (ref "U$2") (pin "3") (pinfunction "CH2+_3") (pintype "input"))
    )
    (net (code "21") (name "ADC6-") (class "Default")
      (node (ref "PI_ADC_3") (pin "6") (pinfunction "S_6") (pintype "passive"))
      (node (ref "U$2") (pin "4") (pinfunction "CH2-_4") (pintype "input"))
    )
    (net (code "22") (name "ADC7+") (class "Default")
      (node (ref "PI_ADC_4") (pin "3") (pinfunction "S_3") (pintype "passive"))
      (node (ref "U$2") (pin "11") (pinfunction "CH3+_11") (pintype "input"))
    )
    (net (code "23") (name "ADC7-") (class "Default")
      (node (ref "PI_ADC_4") (pin "4") (pinfunction "S_4") (pintype "passive"))
      (node (ref "U$2") (pin "12") (pinfunction "CH3-_12") (pintype "input"))
    )
    (net (code "24") (name "ADC8+") (class "Default")
      (node (ref "PI_ADC_4") (pin "5") (pinfunction "S_5") (pintype "passive"))
      (node (ref "U$2") (pin "13") (pinfunction "CH4+_13") (pintype "input"))
    )
    (net (code "25") (name "ADC8-") (class "Default")
      (node (ref "PI_ADC_4") (pin "6") (pinfunction "S_6") (pintype "passive"))
      (node (ref "U$2") (pin "14") (pinfunction "CH4-_14") (pintype "input"))
    )
    (net (code "26") (name "FTDI1_3V3") (class "Default")
      (node (ref "C16") (pin "2") (pinfunction "2_2") (pintype "passive"))
      (node (ref "U6") (pin "17") (pinfunction "3V3OUT_17") (pintype "input"))
    )
    (net (code "27") (name "FTDI2_3V3") (class "Default")
      (node (ref "C29") (pin "2") (pinfunction "2_2") (pintype "passive"))
      (node (ref "U5") (pin "17") (pinfunction "3V3OUT_17") (pintype "input"))
    )
    (net (code "28") (name "FTDI2_RE") (class "Default")
      (node (ref "R27") (pin "1") (pinfunction "1_1") (pintype "passive"))
      (node (ref "U12") (pin "2") (pinfunction "~{RE}_2") (pintype "input"))
      (node (ref "U5") (pin "14") (pinfunction "CBUS3_14") (pintype "input"))
    )
    (net (code "29") (name "FTDI2_RXD") (class "Default")
      (node (ref "U12") (pin "1") (pinfunction "RO_1") (pintype "output"))
      (node (ref "U5") (pin "5") (pinfunction "RXD_5") (pintype "input"))
    )
    (net (code "30") (name "FTDI2_TE") (class "Default")
      (node (ref "U12") (pin "3") (pinfunction "DE_3") (pintype "input"))
      (node (ref "U5") (pin "13") (pinfunction "CBUS2_13") (pintype "input"))
    )
    (net (code "31") (name "FTDI2_TXD") (class "Default")
      (node (ref "U12") (pin "4") (pinfunction "DI_4") (pintype "input"))
      (node (ref "U5") (pin "1") (pinfunction "TXD_1") (pintype "input"))
    )
    (net (code "32") (name "FTDI3_3V3") (class "Default")
      (node (ref "C39") (pin "2") (pinfunction "2_2") (pintype "passive"))
      (node (ref "U13") (pin "17") (pinfunction "3V3OUT_17") (pintype "input"))
    )
    (net (code "33") (name "FTDI4_3V3") (class "Default")
      (node (ref "C43") (pin "2") (pinfunction "2_2") (pintype "passive"))
      (node (ref "U14") (pin "17") (pinfunction "3V3OUT_17") (pintype "input"))
    )
    (net (code "34") (name "FTDI5_3V3") (class "Default")
      (node (ref "C47") (pin "2") (pinfunction "2_2") (pintype "passive"))
      (node (ref "U15") (pin "17") (pinfunction "3V3OUT_17") (pintype "input"))
    )
    (net (code "35") (name "FTDI_HUB_LEDS") (class "Default")
      (node (ref "R23") (pin "1") (pinfunction "1_1") (pintype "passive"))
      (node (ref "R24") (pin "1") (pinfunction "1_1") (pintype "passive"))
      (node (ref "R29") (pin "1") (pinfunction "1_1") (pintype "passive"))
      (node (ref "R30") (pin "1") (pinfunction "1_1") (pintype "passive"))
      (node (ref "R31") (pin "1") (pinfunction "1_1") (pintype "passive"))
      (node (ref "R32") (pin "1") (pinfunction "1_1") (pintype "passive"))
      (node (ref "R33") (pin "1") (pinfunction "1_1") (pintype "passive"))
      (node (ref "R34") (pin "1") (pinfunction "1_1") (pintype "passive"))
      (node (ref "SW5") (pin "1") (pinfunction "1_1") (pintype "bidirectional"))
    )
    (net (code "36") (name "GND") (class "Default")
      (node (ref "BAT1") (pin "-") (pinfunction "V-_-") (pintype "bidirectional"))
      (node (ref "C1") (pin "2") (pinfunction "2_2") (pintype "passive"))
      (node (ref "C10") (pin "-") (pinfunction "-_-") (pintype "passive"))
      (node (ref "C11") (pin "1") (pinfunction "1_1") (pintype "passive"))
      (node (ref "C12") (pin "1") (pinfunction "1_1") (pintype "passive"))
      (node (ref "C13") (pin "1") (pinfunction "1_1") (pintype "passive"))
      (node (ref "C15") (pin "1") (pinfunction "1_1") (pintype "passive"))
      (node (ref "C16") (pin "1") (pinfunction "1_1") (pintype "passive"))
      (node (ref "C17") (pin "-") (pinfunction "-_-") (pintype "passive"))
      (node (ref "C18") (pin "1") (pinfunction "1_1") (pintype "passive"))
      (node (ref "C19") (pin "2") (pinfunction "2_2") (pintype "passive"))
      (node (ref "C2") (pin "1") (pinfunction "1_1") (pintype "passive"))
      (node (ref "C22") (pin "2") (pinfunction "2_2") (pintype "passive"))
      (node (ref "C23") (pin "1") (pinfunction "1_1") (pintype "passive"))
      (node (ref "C25") (pin "1") (pinfunction "1_1") (pintype "passive"))
      (node (ref "C26") (pin "-") (pinfunction "-_-") (pintype "passive"))
      (node (ref "C28") (pin "1") (pinfunction "1_1") (pintype "passive"))
      (node (ref "C29") (pin "1") (pinfunction "1_1") (pintype "passive"))
      (node (ref "C3") (pin "2") (pinfunction "2_2") (pintype "passive"))
      (node (ref "C30") (pin "-") (pinfunction "-_-") (pintype "passive"))
      (node (ref "C31") (pin "1") (pinfunction "1_1") (pintype "passive"))
      (node (ref "C32") (pin "2") (pinfunction "2_2") (pintype "passive"))
      (node (ref "C34") (pin "-") (pinfunction "-_-") (pintype "passive"))
      (node (ref "C35") (pin "1") (pinfunction "1_1") (pintype "passive"))
      (node (ref "C36") (pin "1") (pinfunction "1_1") (pintype "passive"))
      (node (ref "C38") (pin "1") (pinfunction "1_1") (pintype "passive"))
      (node (ref "C39") (pin "1") (pinfunction "1_1") (pintype "passive"))
      (node (ref "C4") (pin "-") (pinfunction "-_-") (pintype "passive"))
      (node (ref "C40") (pin "-") (pinfunction "-_-") (pintype "passive"))
      (node (ref "C42") (pin "1") (pinfunction "1_1") (pintype "passive"))
      (node (ref "C43") (pin "1") (pinfunction "1_1") (pintype "passive"))
      (node (ref "C44") (pin "-") (pinfunction "-_-") (pintype "passive"))
      (node (ref "C46") (pin "1") (pinfunction "1_1") (pintype "passive"))
      (node (ref "C47") (pin "1") (pinfunction "1_1") (pintype "passive"))
      (node (ref "C48") (pin "-") (pinfunction "-_-") (pintype "passive"))
      (node (ref "C9") (pin "1") (pinfunction "1_1") (pintype "passive"))
      (node (ref "I2C_1") (pin "5") (pinfunction "S_5") (pintype "passive"))
      (node (ref "I2C_10") (pin "5") (pinfunction "S_5") (pintype "passive"))
      (node (ref "I2C_2") (pin "5") (pinfunction "S_5") (pintype "passive"))
      (node (ref "I2C_3") (pin "5") (pinfunction "S_5") (pintype "passive"))
      (node (ref "I2C_4") (pin "5") (pinfunction "S_5") (pintype "passive"))
      (node (ref "I2C_5") (pin "5") (pinfunction "S_5") (pintype "passive"))
      (node (ref "I2C_6") (pin "5") (pinfunction "S_5") (pintype "passive"))
      (node (ref "I2C_7") (pin "5") (pinfunction "S_5") (pintype "passive"))
      (node (ref "I2C_8") (pin "5") (pinfunction "S_5") (pintype "passive"))
      (node (ref "I2C_9") (pin "5") (pinfunction "S_5") (pintype "passive"))
      (node (ref "I_UART_HUB_1") (pin "5") (pinfunction "S_5") (pintype "passive"))
      (node (ref "J1") (pin "-") (pinfunction "-_-") (pintype "bidirectional"))
      (node (ref "J1") (pin "CDN") (pinfunction "CDN_CDN") (pintype "bidirectional"))
      (node (ref "J10") (pin "14") (pinfunction "14_14") (pintype "passive"))
      (node (ref "J10") (pin "15") (pinfunction "15_15") (pintype "passive"))
      (node (ref "J10") (pin "16") (pinfunction "16_16") (pintype "passive"))
      (node (ref "J11") (pin "14") (pinfunction "14_14") (pintype "passive"))
      (node (ref "J11") (pin "15") (pinfunction "15_15") (pintype "passive"))
      (node (ref "J11") (pin "16") (pinfunction "16_16") (pintype "passive"))
      (node (ref "J2") (pin "6") (pinfunction "VSS_6") (pintype "bidirectional"))
      (node (ref "J2") (pin "G1") (pinfunction "G1_G1") (pintype "bidirectional"))
      (node (ref "J2") (pin "G2") (pinfunction "G2_G2") (pintype "bidirectional"))
      (node (ref "J2") (pin "G3") (pinfunction "G3_G3") (pintype "bidirectional"))
      (node (ref "J2") (pin "G4") (pinfunction "G4_G4") (pintype "bidirectional"))
      (node (ref "J3") (pin "2") (pinfunction "2_2") (pintype "bidirectional"))
      (node (ref "J7") (pin "15") (pinfunction "15_15") (pintype "passive"))
      (node (ref "J7") (pin "16") (pinfunction "16_16") (pintype "passive"))
      (node (ref "J8") (pin "2") (pinfunction "2_2") (pintype "bidirectional"))
      (node (ref "J9") (pin "15") (pinfunction "15_15") (pintype "passive"))
      (node (ref "J9") (pin "16") (pinfunction "16_16") (pintype "passive"))
      (node (ref "L3") (pin "1") (pinfunction "1_1") (pintype "passive"))
      (node (ref "LOPY_I2C") (pin "5") (pinfunction "S_5") (pintype "passive"))
      (node (ref "LOPY_SPI") (pin "7") (pinfunction "S_7") (pintype "passive"))
      (node (ref "LOPY_UART0") (pin "5") (pinfunction "S_5") (pintype "passive"))
      (node (ref "LOPY_UART1") (pin "5") (pinfunction "S_5") (pintype "passive"))
      (node (ref "PCB1") (pin "P$14") (pinfunction "GND_P$14") (pintype "bidirectional"))
      (node (ref "PCB1") (pin "P$20") (pinfunction "GND_P$20") (pintype "bidirectional"))
      (node (ref "PCB1") (pin "P$25") (pinfunction "GND_P$25") (pintype "bidirectional"))
      (node (ref "PCB1") (pin "P$30") (pinfunction "GND_P$30") (pintype "bidirectional"))
      (node (ref "PCB1") (pin "P$34") (pinfunction "GND_P$34") (pintype "bidirectional"))
      (node (ref "PCB1") (pin "P$39") (pinfunction "GND_P$39") (pintype "bidirectional"))
      (node (ref "PCB1") (pin "P$6") (pinfunction "GND_P$6") (pintype "bidirectional"))
      (node (ref "PCB1") (pin "P$9") (pinfunction "GND_P$9") (pintype "bidirectional"))
      (node (ref "PI_RS_485") (pin "5") (pinfunction "S_5") (pintype "passive"))
      (node (ref "PI_UART") (pin "5") (pinfunction "S_5") (pintype "passive"))
      (node (ref "PI_UART_HUB_2") (pin "5") (pinfunction "S_5") (pintype "passive"))
      (node (ref "PI_UART_HUB_3") (pin "5") (pinfunction "S_5") (pintype "passive"))
      (node (ref "Q3") (pin "2") (pinfunction "S_2") (pintype "passive"))
      (node (ref "Q4") (pin "2") (pinfunction "S_2") (pintype "passive"))
      (node (ref "Q5") (pin "1") (pinfunction "G_1") (pintype "passive"))
      (node (ref "Q6") (pin "2") (pinfunction "S_2") (pintype "passive"))
      (node (ref "Q7") (pin "2") (pinfunction "S_2") (pintype "passive"))
      (node (ref "R20") (pin "1") (pinfunction "1_1") (pintype "passive"))
      (node (ref "R28") (pin "1") (pinfunction "1_1") (pintype "passive"))
      (node (ref "R40") (pin "1") (pinfunction "1_1") (pintype "passive"))
      (node (ref "R43") (pin "1") (pinfunction "1_1") (pintype "passive"))
      (node (ref "R44") (pin "1") (pinfunction "1_1") (pintype "passive"))
      (node (ref "R45") (pin "1") (pinfunction "1_1") (pintype "passive"))
      (node (ref "SPI_1") (pin "7") (pinfunction "S_7") (pintype "passive"))
      (node (ref "SPI_2") (pin "7") (pinfunction "S_7") (pintype "passive"))
      (node (ref "SPI_3") (pin "7") (pinfunction "S_7") (pintype "passive"))
      (node (ref "SPI_4") (pin "7") (pinfunction "S_7") (pintype "passive"))
      (node (ref "SPI_5") (pin "7") (pinfunction "S_7") (pintype "passive"))
      (node (ref "SPI_6") (pin "7") (pinfunction "S_7") (pintype "passive"))
      (node (ref "SPI_7") (pin "7") (pinfunction "S_7") (pintype "passive"))
      (node (ref "SPI_8") (pin "7") (pinfunction "S_7") (pintype "passive"))
      (node (ref "SW1") (pin "SS1") (pinfunction "SS1_SS1") (pintype "bidirectional"))
      (node (ref "SW1") (pin "SS2") (pinfunction "SS2_SS2") (pintype "bidirectional"))
      (node (ref "SW1") (pin "SS3") (pinfunction "SS3_SS3") (pintype "bidirectional"))
      (node (ref "SW1") (pin "SS4") (pinfunction "SS4_SS4") (pintype "bidirectional"))
      (node (ref "SW3") (pin "SS1") (pinfunction "SS1_SS1") (pintype "bidirectional"))
      (node (ref "SW3") (pin "SS2") (pinfunction "SS2_SS2") (pintype "bidirectional"))
      (node (ref "SW3") (pin "SS3") (pinfunction "SS3_SS3") (pintype "bidirectional"))
      (node (ref "SW3") (pin "SS4") (pinfunction "SS4_SS4") (pintype "bidirectional"))
      (node (ref "SW4") (pin "COM") (pinfunction "COM_COM") (pintype "bidirectional"))
      (node (ref "SW4") (pin "SS1") (pinfunction "SS1_SS1") (pintype "bidirectional"))
      (node (ref "SW4") (pin "SS2") (pinfunction "SS2_SS2") (pintype "bidirectional"))
      (node (ref "SW4") (pin "SS3") (pinfunction "SS3_SS3") (pintype "bidirectional"))
      (node (ref "SW4") (pin "SS4") (pinfunction "SS4_SS4") (pintype "bidirectional"))
      (node (ref "TP7") (pin "TP") (pinfunction "TP_TP") (pintype "input"))
      (node (ref "U$3") (pin "2") (pinfunction "C_2") (pintype "passive"))
      (node (ref "U$4") (pin "2") (pinfunction "ADJ/GND_2") (pintype "passive"))
      (node (ref "U$4") (pin "TAB") (pinfunction "TAB_TAB") (pintype "power_in"))
      (node (ref "U$5") (pin "IN-") (pinfunction "IN-_IN-") (pintype "bidirectional"))
      (node (ref "U$5") (pin "OUT-") (pinfunction "OUT-_OUT-") (pintype "bidirectional"))
      (node (ref "U$6") (pin "1") (pinfunction "VSS_1") (pintype "bidirectional"))
      (node (ref "U$7") (pin "4") (pinfunction "GND_4") (pintype "power_in"))
      (node (ref "U1") (pin "10") (pinfunction "VSS_10") (pintype "power_in"))
      (node (ref "U1") (pin "15") (pinfunction "A0_15") (pintype "input"))
      (node (ref "U1") (pin "16") (pinfunction "A1_16") (pintype "input"))
      (node (ref "U1") (pin "17") (pinfunction "A2_17") (pintype "input"))
      (node (ref "U10") (pin "8") (pinfunction "GND_8") (pintype "passive"))
      (node (ref "U12") (pin "5") (pinfunction "GND_5") (pintype "passive"))
      (node (ref "U13") (pin "18") (pinfunction "GND_18") (pintype "input"))
      (node (ref "U13") (pin "21") (pinfunction "GND_21") (pintype "input"))
      (node (ref "U13") (pin "25") (pinfunction "GND_25") (pintype "input"))
      (node (ref "U13") (pin "26") (pinfunction "TEST_26") (pintype "input"))
      (node (ref "U13") (pin "7") (pinfunction "GND_7") (pintype "input"))
      (node (ref "U14") (pin "18") (pinfunction "GND_18") (pintype "input"))
      (node (ref "U14") (pin "21") (pinfunction "GND_21") (pintype "input"))
      (node (ref "U14") (pin "25") (pinfunction "GND_25") (pintype "input"))
      (node (ref "U14") (pin "26") (pinfunction "TEST_26") (pintype "input"))
      (node (ref "U14") (pin "7") (pinfunction "GND_7") (pintype "input"))
      (node (ref "U15") (pin "18") (pinfunction "GND_18") (pintype "input"))
      (node (ref "U15") (pin "21") (pinfunction "GND_21") (pintype "input"))
      (node (ref "U15") (pin "25") (pinfunction "GND_25") (pintype "input"))
      (node (ref "U15") (pin "26") (pinfunction "TEST_26") (pintype "input"))
      (node (ref "U15") (pin "7") (pinfunction "GND_7") (pintype "input"))
      (node (ref "U2") (pin "4") (pinfunction "VSS_4") (pintype "power_in"))
      (node (ref "U3") (pin "P$27") (pinfunction "GND_P$27") (pintype "power_in"))
      (node (ref "U4") (pin "10") (pinfunction "GND_10") (pintype "passive"))
      (node (ref "U5") (pin "18") (pinfunction "GND_18") (pintype "input"))
      (node (ref "U5") (pin "21") (pinfunction "GND_21") (pintype "input"))
      (node (ref "U5") (pin "25") (pinfunction "GND_25") (pintype "input"))
      (node (ref "U5") (pin "26") (pinfunction "TEST_26") (pintype "input"))
      (node (ref "U5") (pin "7") (pinfunction "GND_7") (pintype "input"))
      (node (ref "U6") (pin "18") (pinfunction "GND_18") (pintype "input"))
      (node (ref "U6") (pin "21") (pinfunction "GND_21") (pintype "input"))
      (node (ref "U6") (pin "25") (pinfunction "GND_25") (pintype "input"))
      (node (ref "U6") (pin "26") (pinfunction "TEST_26") (pintype "input"))
      (node (ref "U6") (pin "7") (pinfunction "GND_7") (pintype "input"))
      (node (ref "U8") (pin "1") (pinfunction "A0_1") (pintype "input"))
      (node (ref "U8") (pin "2") (pinfunction "A1_2") (pintype "input"))
      (node (ref "U8") (pin "3") (pinfunction "A2_3") (pintype "input"))
      (node (ref "U8") (pin "4") (pinfunction "GND_4") (pintype "power_in"))
      (node (ref "USB1") (pin "5") (pinfunction "GND_5") (pintype "power_in"))
      (node (ref "USB1") (pin "P1") (pinfunction "SHIELD_P1") (pintype "power_in"))
      (node (ref "USB1") (pin "P2") (pinfunction "SHIELD_P2") (pintype "power_in"))
      (node (ref "USB1") (pin "P3") (pinfunction "SHIELD_P3") (pintype "power_in"))
      (node (ref "USB1") (pin "P4") (pinfunction "SHIELD_P4") (pintype "power_in"))
      (node (ref "USB1") (pin "P5") (pinfunction "SHIELD_P5") (pintype "power_in"))
      (node (ref "USB1") (pin "P6") (pinfunction "SHIELD_P6") (pintype "power_in"))
      (node (ref "USB3") (pin "5") (pinfunction "GND_5") (pintype "power_in"))
      (node (ref "USB3") (pin "P1") (pinfunction "SHIELD_P1") (pintype "power_in"))
      (node (ref "USB3") (pin "P2") (pinfunction "SHIELD_P2") (pintype "power_in"))
      (node (ref "USB3") (pin "P3") (pinfunction "SHIELD_P3") (pintype "power_in"))
      (node (ref "USB3") (pin "P4") (pinfunction "SHIELD_P4") (pintype "power_in"))
      (node (ref "USB3") (pin "P5") (pinfunction "SHIELD_P5") (pintype "power_in"))
      (node (ref "USB3") (pin "P6") (pinfunction "SHIELD_P6") (pintype "power_in"))
    )
    (net (code "37") (name "GNDA") (class "Default")
      (node (ref "C14") (pin "1") (pinfunction "1_1") (pintype "passive"))
      (node (ref "C5") (pin "-") (pinfunction "-_-") (pintype "passive"))
      (node (ref "C6") (pin "1") (pinfunction "1_1") (pintype "passive"))
      (node (ref "C7") (pin "1") (pinfunction "1_1") (pintype "passive"))
      (node (ref "C8") (pin "-") (pinfunction "-_-") (pintype "passive"))
      (node (ref "L3") (pin "2") (pinfunction "2_2") (pintype "passive"))
      (node (ref "PI_ADC_1") (pin "7") (pinfunction "S_7") (pintype "passive"))
      (node (ref "PI_ADC_2") (pin "7") (pinfunction "S_7") (pintype "passive"))
      (node (ref "PI_ADC_3") (pin "7") (pinfunction "S_7") (pintype "passive"))
      (node (ref "PI_ADC_4") (pin "7") (pinfunction "S_7") (pintype "passive"))
      (node (ref "U$1") (pin "10") (pinfunction "ADR1_10") (pintype "input"))
      (node (ref "U$1") (pin "5") (pinfunction "VSS_5") (pintype "power_in"))
      (node (ref "U$1") (pin "9") (pinfunction "ADR0_9") (pintype "input"))
      (node (ref "U$2") (pin "5") (pinfunction "VSS_5") (pintype "power_in"))
      (node (ref "U$2") (pin "9") (pinfunction "ADR0_9") (pintype "input"))
    )
    (net (code "38") (name "GPIO4") (class "Default")
      (node (ref "PCB1") (pin "P$7") (pinfunction "GPIO4_P$7") (pintype "bidirectional"))
      (node (ref "R16") (pin "1") (pinfunction "1_1") (pintype "passive"))
      (node (ref "U$7") (pin "2") (pinfunction "DAT_2") (pintype "bidirectional"))
    )
    (net (code "39") (name "GPIO12") (class "Default")
      (node (ref "PCB1") (pin "P$32") (pinfunction "GPIO12_P$32") (pintype "bidirectional"))
      (node (ref "U1") (pin "19") (pinfunction "INTB_19") (pintype "output"))
    )
    (net (code "40") (name "GPIO13") (class "Default")
      (node (ref "PCB1") (pin "P$33") (pinfunction "GPIO13_P$33") (pintype "bidirectional"))
      (node (ref "U1") (pin "20") (pinfunction "INTA_20") (pintype "output"))
    )
    (net (code "41") (name "GPIO16_FREE") (class "Default")
      (node (ref "J10") (pin "7") (pinfunction "7_7") (pintype "passive"))
      (node (ref "J11") (pin "7") (pinfunction "7_7") (pintype "passive"))
      (node (ref "PCB1") (pin "P$36") (pinfunction "GPIO16_P$36") (pintype "bidirectional"))
    )
    (net (code "42") (name "GPIO18_FREE") (class "Default")
      (node (ref "J10") (pin "8") (pinfunction "8_8") (pintype "passive"))
      (node (ref "J11") (pin "8") (pinfunction "8_8") (pintype "passive"))
      (node (ref "PCB1") (pin "P$12") (pinfunction "GPIO18_P$12") (pintype "bidirectional"))
    )
    (net (code "43") (name "GPIO19_FREE") (class "Default")
      (node (ref "J10") (pin "9") (pinfunction "9_9") (pintype "passive"))
      (node (ref "J11") (pin "9") (pinfunction "9_9") (pintype "passive"))
      (node (ref "PCB1") (pin "P$35") (pinfunction "GPIO19_P$35") (pintype "bidirectional"))
    )
    (net (code "44") (name "GPIO20_FREE") (class "Default")
      (node (ref "J10") (pin "10") (pinfunction "10_10") (pintype "passive"))
      (node (ref "J11") (pin "10") (pinfunction "10_10") (pintype "passive"))
      (node (ref "PCB1") (pin "P$38") (pinfunction "GPIO20_P$38") (pintype "bidirectional"))
    )
    (net (code "45") (name "GPIO21_FREE") (class "Default")
      (node (ref "J10") (pin "11") (pinfunction "11_11") (pintype "passive"))
      (node (ref "J11") (pin "11") (pinfunction "11_11") (pintype "passive"))
      (node (ref "PCB1") (pin "P$40") (pinfunction "GPIO21_P$40") (pintype "bidirectional"))
    )
    (net (code "46") (name "GPIO24_FREE") (class "Default")
      (node (ref "J10") (pin "12") (pinfunction "12_12") (pintype "passive"))
      (node (ref "J11") (pin "12") (pinfunction "12_12") (pintype "passive"))
      (node (ref "PCB1") (pin "P$18") (pinfunction "GPIO24_P$18") (pintype "bidirectional"))
    )
    (net (code "47") (name "GPIO25_FREE") (class "Default")
      (node (ref "J10") (pin "13") (pinfunction "13_13") (pintype "passive"))
      (node (ref "J11") (pin "13") (pinfunction "13_13") (pintype "passive"))
      (node (ref "PCB1") (pin "P$22") (pinfunction "GPIO25_P$22") (pintype "bidirectional"))
    )
    (net (code "48") (name "ID_SC") (class "Default")
      (node (ref "PCB1") (pin "P$28") (pinfunction "ID_SC*_P$28") (pintype "bidirectional"))
      (node (ref "R37") (pin "1") (pinfunction "1_1") (pintype "passive"))
      (node (ref "U8") (pin "6") (pinfunction "SCL_6") (pintype "bidirectional"))
    )
    (net (code "49") (name "ID_SD") (class "Default")
      (node (ref "PCB1") (pin "P$27") (pinfunction "ID_SD*_P$27") (pintype "bidirectional"))
      (node (ref "R38") (pin "1") (pinfunction "1_1") (pintype "passive"))
      (node (ref "U8") (pin "5") (pinfunction "SDA_5") (pintype "bidirectional"))
    )
    (net (code "50") (name "LED_GND") (class "Default")
      (node (ref "D10") (pin "-") (pinfunction "-_-") (pintype "passive"))
      (node (ref "D11") (pin "-") (pinfunction "-_-") (pintype "passive"))
      (node (ref "D12") (pin "-") (pinfunction "-_-") (pintype "passive"))
      (node (ref "D13") (pin "-") (pinfunction "-_-") (pintype "passive"))
      (node (ref "D14") (pin "-") (pinfunction "-_-") (pintype "passive"))
      (node (ref "D22") (pin "-") (pinfunction "-_-") (pintype "passive"))
      (node (ref "D4") (pin "-") (pinfunction "-_-") (pintype "passive"))
      (node (ref "D5") (pin "-") (pinfunction "-_-") (pintype "passive"))
      (node (ref "D6") (pin "-") (pinfunction "-_-") (pintype "passive"))
      (node (ref "D8") (pin "-") (pinfunction "-_-") (pintype "passive"))
      (node (ref "D9") (pin "-") (pinfunction "-_-") (pintype "passive"))
      (node (ref "SW4") (pin "B") (pinfunction "B_B") (pintype "bidirectional"))
    )
    (net (code "51") (name "LOPY_3V3") (class "Default")
      (node (ref "F59") (pin "1") (pinfunction "1_1") (pintype "bidirectional"))
      (node (ref "F75") (pin "1") (pinfunction "1_1") (pintype "bidirectional"))
      (node (ref "F79") (pin "1") (pinfunction "1_1") (pintype "bidirectional"))
      (node (ref "F81") (pin "1") (pinfunction "1_1") (pintype "bidirectional"))
      (node (ref "F83") (pin "1") (pinfunction "1_1") (pintype "bidirectional"))
      (node (ref "J2") (pin "4") (pinfunction "VDD_4") (pintype "bidirectional"))
      (node (ref "J4") (pin "1") (pinfunction "1_1") (pintype "bidirectional"))
      (node (ref "Q8") (pin "3") (pinfunction "D_3") (pintype "passive"))
      (node (ref "R22") (pin "2") (pinfunction "2_2") (pintype "passive"))
      (node (ref "R46") (pin "2") (pinfunction "2_2") (pintype "passive"))
      (node (ref "SW3") (pin "B") (pinfunction "B_B") (pintype "bidirectional"))
      (node (ref "U3") (pin "P$26") (pinfunction "3V3_P$26") (pintype "power_in"))
    )
    (net (code "52") (name "LOPY_CS1") (class "Default")
      (node (ref "LOPY_SPI") (pin "3") (pinfunction "S_3") (pintype "passive"))
      (node (ref "U3") (pin "P$10") (pinfunction "P8_P$10") (pintype "bidirectional"))
    )
    (net (code "53") (name "LOPY_CS2") (class "Default")
      (node (ref "J2") (pin "2") (pinfunction "CS_2") (pintype "bidirectional"))
      (node (ref "U3") (pin "P$16") (pinfunction "P14_P$16") (pintype "input"))
    )
    (net (code "54") (name "LOPY_MISO") (class "Default")
      (node (ref "J2") (pin "7") (pinfunction "DO_7") (pintype "bidirectional"))
      (node (ref "J4") (pin "2") (pinfunction "2_2") (pintype "bidirectional"))
      (node (ref "LOPY_SPI") (pin "5") (pinfunction "S_5") (pintype "passive"))
      (node (ref "Q8") (pin "2") (pinfunction "S_2") (pintype "passive"))
      (node (ref "U3") (pin "P$14") (pinfunction "P12_P$14") (pintype "bidirectional"))
    )
    (net (code "55") (name "LOPY_MOSI") (class "Default")
      (node (ref "J2") (pin "3") (pinfunction "DI_3") (pintype "bidirectional"))
      (node (ref "LOPY_SPI") (pin "4") (pinfunction "S_4") (pintype "passive"))
      (node (ref "U3") (pin "P$13") (pinfunction "P11_P$13") (pintype "bidirectional"))
    )
    (net (code "56") (name "LOPY_P2") (class "Default")
      (node (ref "J3") (pin "1") (pinfunction "1_1") (pintype "bidirectional"))
      (node (ref "Q6") (pin "3") (pinfunction "D_3") (pintype "passive"))
      (node (ref "U3") (pin "P$4") (pinfunction "P2_P$4") (pintype "bidirectional"))
    )
    (net (code "57") (name "LOPY_P15") (class "Default")
      (node (ref "J7") (pin "14") (pinfunction "14_14") (pintype "passive"))
      (node (ref "J9") (pin "14") (pinfunction "14_14") (pintype "passive"))
      (node (ref "U3") (pin "P$17") (pinfunction "P15_P$17") (pintype "input"))
    )
    (net (code "58") (name "LOPY_P16") (class "Default")
      (node (ref "J7") (pin "13") (pinfunction "13_13") (pintype "passive"))
      (node (ref "J9") (pin "13") (pinfunction "13_13") (pintype "passive"))
      (node (ref "U3") (pin "P$18") (pinfunction "P16_P$18") (pintype "input"))
    )
    (net (code "59") (name "LOPY_P17") (class "Default")
      (node (ref "J7") (pin "12") (pinfunction "12_12") (pintype "passive"))
      (node (ref "J9") (pin "12") (pinfunction "12_12") (pintype "passive"))
      (node (ref "U3") (pin "P$19") (pinfunction "P17_P$19") (pintype "input"))
    )
    (net (code "60") (name "LOPY_P18") (class "Default")
      (node (ref "J7") (pin "11") (pinfunction "11_11") (pintype "passive"))
      (node (ref "J9") (pin "11") (pinfunction "11_11") (pintype "passive"))
      (node (ref "U3") (pin "P$20") (pinfunction "P18_P$20") (pintype "input"))
    )
    (net (code "61") (name "LOPY_P19") (class "Default")
      (node (ref "J7") (pin "10") (pinfunction "10_10") (pintype "passive"))
      (node (ref "J9") (pin "10") (pinfunction "10_10") (pintype "passive"))
      (node (ref "U3") (pin "P$21") (pinfunction "P19_P$21") (pintype "bidirectional"))
    )
    (net (code "62") (name "LOPY_P20") (class "Default")
      (node (ref "J7") (pin "9") (pinfunction "9_9") (pintype "passive"))
      (node (ref "J9") (pin "9") (pinfunction "9_9") (pintype "passive"))
      (node (ref "U3") (pin "P$22") (pinfunction "P20_P$22") (pintype "bidirectional"))
    )
    (net (code "63") (name "LOPY_P21") (class "Default")
      (node (ref "J7") (pin "8") (pinfunction "8_8") (pintype "passive"))
      (node (ref "J9") (pin "8") (pinfunction "8_8") (pintype "passive"))
      (node (ref "U3") (pin "P$23") (pinfunction "P21_P$23") (pintype "bidirectional"))
    )
    (net (code "64") (name "LOPY_P22") (class "Default")
      (node (ref "J7") (pin "7") (pinfunction "7_7") (pintype "passive"))
      (node (ref "J9") (pin "7") (pinfunction "7_7") (pintype "passive"))
      (node (ref "U3") (pin "P$24") (pinfunction "P22_P$24") (pintype "bidirectional"))
    )
    (net (code "65") (name "LOPY_P23") (class "Default")
      (node (ref "J7") (pin "6") (pinfunction "6_6") (pintype "passive"))
      (node (ref "J9") (pin "6") (pinfunction "6_6") (pintype "passive"))
      (node (ref "U3") (pin "P$25") (pinfunction "P23_P$25") (pintype "bidirectional"))
    )
    (net (code "66") (name "LOPY_RST_EN") (class "Default")
      (node (ref "PCB1") (pin "P$37") (pinfunction "GPIO26_P$37") (pintype "bidirectional"))
      (node (ref "R15") (pin "1") (pinfunction "1_1") (pintype "passive"))
    )
    (net (code "67") (name "LOPY_RXD0") (class "Default")
      (node (ref "LOPY_UART0") (pin "4") (pinfunction "S_4") (pintype "passive"))
      (node (ref "R13") (pin "2") (pinfunction "2_2") (pintype "passive"))
      (node (ref "R8") (pin "1") (pinfunction "1_1") (pintype "passive"))
      (node (ref "U3") (pin "P$2") (pinfunction "P0_P$2") (pintype "bidirectional"))
    )
    (net (code "68") (name "LOPY_RXD1") (class "Default")
      (node (ref "LOPY_UART1") (pin "4") (pinfunction "S_4") (pintype "passive"))
      (node (ref "U3") (pin "P$6") (pinfunction "P4_P$6") (pintype "bidirectional"))
    )
    (net (code "69") (name "LOPY_SCL{slash}CLK") (class "Default")
      (node (ref "J2") (pin "5") (pinfunction "SCLK_5") (pintype "bidirectional"))
      (node (ref "LOPY_I2C") (pin "4") (pinfunction "S_4") (pintype "passive"))
      (node (ref "LOPY_SPI") (pin "6") (pinfunction "S_6") (pintype "passive"))
      (node (ref "U3") (pin "P$12") (pinfunction "P10_P$12") (pintype "bidirectional"))
    )
    (net (code "70") (name "LOPY_SDA") (class "Default")
      (node (ref "LOPY_I2C") (pin "3") (pinfunction "S_3") (pintype "passive"))
      (node (ref "U3") (pin "P$11") (pinfunction "P9_P$11") (pintype "bidirectional"))
    )
    (net (code "71") (name "LOPY_TXD0") (class "Default")
      (node (ref "LOPY_UART0") (pin "3") (pinfunction "S_3") (pintype "passive"))
      (node (ref "R12") (pin "1") (pinfunction "1_1") (pintype "passive"))
      (node (ref "R14") (pin "2") (pinfunction "2_2") (pintype "passive"))
      (node (ref "U3") (pin "P$3") (pinfunction "P1_P$3") (pintype "bidirectional"))
    )
    (net (code "72") (name "LOPY_TXD1") (class "Default")
      (node (ref "LOPY_UART1") (pin "3") (pinfunction "S_3") (pintype "passive"))
      (node (ref "U3") (pin "P$5") (pinfunction "P3_P$5") (pintype "bidirectional"))
    )
    (net (code "73") (name "LOPY_USB_5V") (class "Default")
      (node (ref "C15") (pin "2") (pinfunction "2_2") (pintype "passive"))
      (node (ref "C17") (pin "+") (pinfunction "+_+") (pintype "passive"))
      (node (ref "L1") (pin "2") (pinfunction "2_2") (pintype "passive"))
      (node (ref "R1") (pin "1") (pinfunction "1_1") (pintype "passive"))
      (node (ref "R11") (pin "2") (pinfunction "2_2") (pintype "passive"))
      (node (ref "R3") (pin "1") (pinfunction "1_1") (pintype "passive"))
      (node (ref "TP5") (pin "TP") (pinfunction "TP_TP") (pintype "input"))
      (node (ref "U6") (pin "20") (pinfunction "VCC_20") (pintype "input"))
      (node (ref "U6") (pin "4") (pinfunction "VCCIO_4") (pintype "input"))
    )
    (net (code "74") (name "Net-(D1-Pad+)") (class "Default")
      (node (ref "D1") (pin "+") (pinfunction "+_+") (pintype "passive"))
      (node (ref "F1") (pin "P$2") (pinfunction "P$2_P$2") (pintype "passive"))
      (node (ref "TP8") (pin "TP") (pinfunction "TP_TP") (pintype "input"))
    )
    (net (code "75") (name "Net-(D2-Pad+)") (class "Default")
      (node (ref "D2") (pin "+") (pinfunction "+_+") (pintype "passive"))
      (node (ref "R1") (pin "2") (pinfunction "2_2") (pintype "passive"))
    )
    (net (code "76") (name "Net-(D3-Pad+)") (class "Default")
      (node (ref "D3") (pin "+") (pinfunction "+_+") (pintype "passive"))
      (node (ref "R3") (pin "2") (pinfunction "2_2") (pintype "passive"))
    )
    (net (code "77") (name "Net-(D4-Pad+)") (class "Default")
      (node (ref "D4") (pin "+") (pinfunction "+_+") (pintype "passive"))
      (node (ref "R5") (pin "1") (pinfunction "1_1") (pintype "passive"))
    )
    (net (code "78") (name "Net-(D5-Pad+)") (class "Default")
      (node (ref "D5") (pin "+") (pinfunction "+_+") (pintype "passive"))
      (node (ref "R6") (pin "1") (pinfunction "1_1") (pintype "passive"))
    )
    (net (code "79") (name "Net-(D6-Pad+)") (class "Default")
      (node (ref "D6") (pin "+") (pinfunction "+_+") (pintype "passive"))
      (node (ref "R7") (pin "1") (pinfunction "1_1") (pintype "passive"))
    )
    (net (code "80") (name "Net-(D7-Pad+)") (class "Default")
      (node (ref "D7") (pin "+") (pinfunction "+_+") (pintype "passive"))
      (node (ref "R23") (pin "2") (pinfunction "2_2") (pintype "passive"))
    )
    (net (code "81") (name "Net-(D8-Pad+)") (class "Default")
      (node (ref "D8") (pin "+") (pinfunction "+_+") (pintype "passive"))
      (node (ref "R9") (pin "1") (pinfunction "1_1") (pintype "passive"))
    )
    (net (code "82") (name "Net-(D9-Pad+)") (class "Default")
      (node (ref "D9") (pin "+") (pinfunction "+_+") (pintype "passive"))
      (node (ref "R10") (pin "1") (pinfunction "1_1") (pintype "passive"))
    )
    (net (code "83") (name "Net-(D10-Pad+)") (class "Default")
      (node (ref "D10") (pin "+") (pinfunction "+_+") (pintype "passive"))
      (node (ref "R11") (pin "1") (pinfunction "1_1") (pintype "passive"))
    )
    (net (code "84") (name "Net-(D11-Pad+)") (class "Default")
      (node (ref "D11") (pin "+") (pinfunction "+_+") (pintype "passive"))
      (node (ref "R35") (pin "1") (pinfunction "1_1") (pintype "passive"))
    )
    (net (code "85") (name "Net-(D12-Pad+)") (class "Default")
      (node (ref "D12") (pin "+") (pinfunction "+_+") (pintype "passive"))
      (node (ref "R42") (pin "1") (pinfunction "1_1") (pintype "passive"))
    )
    (net (code "86") (name "Net-(D13-Pad+)") (class "Default")
      (node (ref "D13") (pin "+") (pinfunction "+_+") (pintype "passive"))
      (node (ref "R21") (pin "1") (pinfunction "1_1") (pintype "passive"))
    )
    (net (code "87") (name "Net-(D14-Pad+)") (class "Default")
      (node (ref "D14") (pin "+") (pinfunction "+_+") (pintype "passive"))
      (node (ref "R22") (pin "1") (pinfunction "1_1") (pintype "passive"))
    )
    (net (code "88") (name "Net-(D15-Pad+)") (class "Default")
      (node (ref "D15") (pin "+") (pinfunction "+_+") (pintype "passive"))
      (node (ref "R24") (pin "2") (pinfunction "2_2") (pintype "passive"))
    )
    (net (code "89") (name "Net-(D16-Pad+)") (class "Default")
      (node (ref "D16") (pin "+") (pinfunction "+_+") (pintype "passive"))
      (node (ref "R29") (pin "2") (pinfunction "2_2") (pintype "passive"))
    )
    (net (code "90") (name "Net-(D17-Pad+)") (class "Default")
      (node (ref "D17") (pin "+") (pinfunction "+_+") (pintype "passive"))
      (node (ref "R30") (pin "2") (pinfunction "2_2") (pintype "passive"))
    )
    (net (code "91") (name "Net-(D18-Pad+)") (class "Default")
      (node (ref "D18") (pin "+") (pinfunction "+_+") (pintype "passive"))
      (node (ref "R31") (pin "2") (pinfunction "2_2") (pintype "passive"))
    )
    (net (code "92") (name "Net-(D19-Pad+)") (class "Default")
      (node (ref "D19") (pin "+") (pinfunction "+_+") (pintype "passive"))
      (node (ref "R32") (pin "2") (pinfunction "2_2") (pintype "passive"))
    )
    (net (code "93") (name "Net-(D20-Pad+)") (class "Default")
      (node (ref "D20") (pin "+") (pinfunction "+_+") (pintype "passive"))
      (node (ref "R33") (pin "2") (pinfunction "2_2") (pintype "passive"))
    )
    (net (code "94") (name "Net-(D21-Pad+)") (class "Default")
      (node (ref "D21") (pin "+") (pinfunction "+_+") (pintype "passive"))
      (node (ref "R34") (pin "2") (pinfunction "2_2") (pintype "passive"))
    )
    (net (code "95") (name "Net-(D22-Pad+)") (class "Default")
      (node (ref "D22") (pin "+") (pinfunction "+_+") (pintype "passive"))
      (node (ref "R4") (pin "1") (pinfunction "1_1") (pintype "passive"))
    )
    (net (code "96") (name "Net-(F59-Pad2)") (class "Default")
      (node (ref "F59") (pin "2") (pinfunction "2_2") (pintype "bidirectional"))
      (node (ref "J7") (pin "3") (pinfunction "3_3") (pintype "passive"))
      (node (ref "J7") (pin "4") (pinfunction "4_4") (pintype "passive"))
      (node (ref "J7") (pin "5") (pinfunction "5_5") (pintype "passive"))
      (node (ref "J9") (pin "3") (pinfunction "3_3") (pintype "passive"))
      (node (ref "J9") (pin "4") (pinfunction "4_4") (pintype "passive"))
      (node (ref "J9") (pin "5") (pinfunction "5_5") (pintype "passive"))
    )
    (net (code "97") (name "Net-(F60-Pad2)") (class "Default")
      (node (ref "F60") (pin "2") (pinfunction "2_2") (pintype "bidirectional"))
      (node (ref "J10") (pin "1") (pinfunction "1_1") (pintype "passive"))
      (node (ref "J10") (pin "2") (pinfunction "2_2") (pintype "passive"))
      (node (ref "J10") (pin "3") (pinfunction "3_3") (pintype "passive"))
      (node (ref "J11") (pin "1") (pinfunction "1_1") (pintype "passive"))
      (node (ref "J11") (pin "2") (pinfunction "2_2") (pintype "passive"))
      (node (ref "J11") (pin "3") (pinfunction "3_3") (pintype "passive"))
    )
    (net (code "98") (name "Net-(F62-Pad2)") (class "Default")
      (node (ref "F62") (pin "2") (pinfunction "2_2") (pintype "bidirectional"))
      (node (ref "J10") (pin "4") (pinfunction "4_4") (pintype "passive"))
      (node (ref "J10") (pin "5") (pinfunction "5_5") (pintype "passive"))
      (node (ref "J10") (pin "6") (pinfunction "6_6") (pintype "passive"))
      (node (ref "J11") (pin "4") (pinfunction "4_4") (pintype "passive"))
      (node (ref "J11") (pin "5") (pinfunction "5_5") (pintype "passive"))
      (node (ref "J11") (pin "6") (pinfunction "6_6") (pintype "passive"))
    )
    (net (code "99") (name "Net-(F76-Pad2)") (class "Default")
      (node (ref "F76") (pin "2") (pinfunction "2_2") (pintype "bidirectional"))
      (node (ref "J7") (pin "1") (pinfunction "1_1") (pintype "passive"))
      (node (ref "J7") (pin "2") (pinfunction "2_2") (pintype "passive"))
      (node (ref "J9") (pin "1") (pinfunction "1_1") (pintype "passive"))
      (node (ref "J9") (pin "2") (pinfunction "2_2") (pintype "passive"))
    )
    (net (code "100") (name "Net-(I2C_1A-S)") (class "Default")
      (node (ref "F5") (pin "2") (pinfunction "2_2") (pintype "bidirectional"))
      (node (ref "I2C_1") (pin "1") (pinfunction "S_1") (pintype "passive"))
    )
    (net (code "101") (name "Net-(I2C_1B-S)") (class "Default")
      (node (ref "F6") (pin "2") (pinfunction "2_2") (pintype "bidirectional"))
      (node (ref "I2C_1") (pin "2") (pinfunction "S_2") (pintype "passive"))
    )
    (net (code "102") (name "Net-(I2C_2A-S)") (class "Default")
      (node (ref "F7") (pin "2") (pinfunction "2_2") (pintype "bidirectional"))
      (node (ref "I2C_2") (pin "1") (pinfunction "S_1") (pintype "passive"))
    )
    (net (code "103") (name "Net-(I2C_2B-S)") (class "Default")
      (node (ref "F8") (pin "2") (pinfunction "2_2") (pintype "bidirectional"))
      (node (ref "I2C_2") (pin "2") (pinfunction "S_2") (pintype "passive"))
    )
    (net (code "104") (name "Net-(I2C_3A-S)") (class "Default")
      (node (ref "F9") (pin "2") (pinfunction "2_2") (pintype "bidirectional"))
      (node (ref "I2C_3") (pin "1") (pinfunction "S_1") (pintype "passive"))
    )
    (net (code "105") (name "Net-(I2C_3B-S)") (class "Default")
      (node (ref "F10") (pin "2") (pinfunction "2_2") (pintype "bidirectional"))
      (node (ref "I2C_3") (pin "2") (pinfunction "S_2") (pintype "passive"))
    )
    (net (code "106") (name "Net-(I2C_4A-S)") (class "Default")
      (node (ref "F11") (pin "2") (pinfunction "2_2") (pintype "bidirectional"))
      (node (ref "I2C_4") (pin "1") (pinfunction "S_1") (pintype "passive"))
    )
    (net (code "107") (name "Net-(I2C_4B-S)") (class "Default")
      (node (ref "F12") (pin "2") (pinfunction "2_2") (pintype "bidirectional"))
      (node (ref "I2C_4") (pin "2") (pinfunction "S_2") (pintype "passive"))
    )
    (net (code "108") (name "Net-(I2C_5A-S)") (class "Default")
      (node (ref "F13") (pin "2") (pinfunction "2_2") (pintype "bidirectional"))
      (node (ref "I2C_5") (pin "1") (pinfunction "S_1") (pintype "passive"))
    )
    (net (code "109") (name "Net-(I2C_5B-S)") (class "Default")
      (node (ref "F14") (pin "2") (pinfunction "2_2") (pintype "bidirectional"))
      (node (ref "I2C_5") (pin "2") (pinfunction "S_2") (pintype "passive"))
    )
    (net (code "110") (name "Net-(I2C_6A-S)") (class "Default")
      (node (ref "F15") (pin "2") (pinfunction "2_2") (pintype "bidirectional"))
      (node (ref "I2C_6") (pin "1") (pinfunction "S_1") (pintype "passive"))
    )
    (net (code "111") (name "Net-(I2C_6B-S)") (class "Default")
      (node (ref "F16") (pin "2") (pinfunction "2_2") (pintype "bidirectional"))
      (node (ref "I2C_6") (pin "2") (pinfunction "S_2") (pintype "passive"))
    )
    (net (code "112") (name "Net-(I2C_7A-S)") (class "Default")
      (node (ref "F17") (pin "2") (pinfunction "2_2") (pintype "bidirectional"))
      (node (ref "I2C_7") (pin "1") (pinfunction "S_1") (pintype "passive"))
    )
    (net (code "113") (name "Net-(I2C_7B-S)") (class "Default")
      (node (ref "F18") (pin "2") (pinfunction "2_2") (pintype "bidirectional"))
      (node (ref "I2C_7") (pin "2") (pinfunction "S_2") (pintype "passive"))
    )
    (net (code "114") (name "Net-(I2C_8A-S)") (class "Default")
      (node (ref "F19") (pin "2") (pinfunction "2_2") (pintype "bidirectional"))
      (node (ref "I2C_8") (pin "1") (pinfunction "S_1") (pintype "passive"))
    )
    (net (code "115") (name "Net-(I2C_8B-S)") (class "Default")
      (node (ref "F20") (pin "2") (pinfunction "2_2") (pintype "bidirectional"))
      (node (ref "I2C_8") (pin "2") (pinfunction "S_2") (pintype "passive"))
    )
    (net (code "116") (name "Net-(I2C_9A-S)") (class "Default")
      (node (ref "F21") (pin "2") (pinfunction "2_2") (pintype "bidirectional"))
      (node (ref "I2C_9") (pin "1") (pinfunction "S_1") (pintype "passive"))
    )
    (net (code "117") (name "Net-(I2C_9B-S)") (class "Default")
      (node (ref "F22") (pin "2") (pinfunction "2_2") (pintype "bidirectional"))
      (node (ref "I2C_9") (pin "2") (pinfunction "S_2") (pintype "passive"))
    )
    (net (code "118") (name "Net-(I2C_10A-S)") (class "Default")
      (node (ref "F36") (pin "2") (pinfunction "2_2") (pintype "bidirectional"))
      (node (ref "I2C_10") (pin "1") (pinfunction "S_1") (pintype "passive"))
    )
    (net (code "119") (name "Net-(I2C_10B-S)") (class "Default")
      (node (ref "F37") (pin "2") (pinfunction "2_2") (pintype "bidirectional"))
      (node (ref "I2C_10") (pin "2") (pinfunction "S_2") (pintype "passive"))
    )
    (net (code "120") (name "Net-(I_UART_HUB_1A-S)") (class "Default")
      (node (ref "F48") (pin "2") (pinfunction "2_2") (pintype "bidirectional"))
      (node (ref "I_UART_HUB_1") (pin "1") (pinfunction "S_1") (pintype "passive"))
    )
    (net (code "121") (name "Net-(I_UART_HUB_1B-S)") (class "Default")
      (node (ref "F49") (pin "2") (pinfunction "2_2") (pintype "bidirectional"))
      (node (ref "I_UART_HUB_1") (pin "2") (pinfunction "S_2") (pintype "passive"))
    )
    (net (code "122") (name "Net-(LOPY_I2CA-S)") (class "Default")
      (node (ref "F82") (pin "2") (pinfunction "2_2") (pintype "bidirectional"))
      (node (ref "LOPY_I2C") (pin "1") (pinfunction "S_1") (pintype "passive"))
    )
    (net (code "123") (name "Net-(LOPY_I2CB-S)") (class "Default")
      (node (ref "F83") (pin "2") (pinfunction "2_2") (pintype "bidirectional"))
      (node (ref "LOPY_I2C") (pin "2") (pinfunction "S_2") (pintype "passive"))
    )
    (net (code "124") (name "Net-(LOPY_SPIA-S)") (class "Default")
      (node (ref "F74") (pin "2") (pinfunction "2_2") (pintype "bidirectional"))
      (node (ref "LOPY_SPI") (pin "1") (pinfunction "S_1") (pintype "passive"))
    )
    (net (code "125") (name "Net-(LOPY_SPIB-S)") (class "Default")
      (node (ref "F75") (pin "2") (pinfunction "2_2") (pintype "bidirectional"))
      (node (ref "LOPY_SPI") (pin "2") (pinfunction "S_2") (pintype "passive"))
    )
    (net (code "126") (name "Net-(LOPY_UART0A-S)") (class "Default")
      (node (ref "F78") (pin "2") (pinfunction "2_2") (pintype "bidirectional"))
      (node (ref "LOPY_UART0") (pin "1") (pinfunction "S_1") (pintype "passive"))
    )
    (net (code "127") (name "Net-(LOPY_UART0B-S)") (class "Default")
      (node (ref "F79") (pin "2") (pinfunction "2_2") (pintype "bidirectional"))
      (node (ref "LOPY_UART0") (pin "2") (pinfunction "S_2") (pintype "passive"))
    )
    (net (code "128") (name "Net-(LOPY_UART1A-S)") (class "Default")
      (node (ref "F80") (pin "2") (pinfunction "2_2") (pintype "bidirectional"))
      (node (ref "LOPY_UART1") (pin "1") (pinfunction "S_1") (pintype "passive"))
    )
    (net (code "129") (name "Net-(LOPY_UART1B-S)") (class "Default")
      (node (ref "F81") (pin "2") (pinfunction "2_2") (pintype "bidirectional"))
      (node (ref "LOPY_UART1") (pin "2") (pinfunction "S_2") (pintype "passive"))
    )
    (net (code "130") (name "Net-(PCB1-GPIO5)") (class "Default")
      (node (ref "PCB1") (pin "P$29") (pinfunction "GPIO5_P$29") (pintype "bidirectional"))
      (node (ref "R41") (pin "2") (pinfunction "2_2") (pintype "passive"))
    )
    (net (code "131") (name "Net-(PCB1-GPIO6)") (class "Default")
      (node (ref "PCB1") (pin "P$31") (pinfunction "GPIO6_P$31") (pintype "bidirectional"))
      (node (ref "R17") (pin "2") (pinfunction "2_2") (pintype "passive"))
    )
    (net (code "132") (name "Net-(PI_ADC_1A-S)") (class "Default")
      (node (ref "F40") (pin "2") (pinfunction "2_2") (pintype "bidirectional"))
      (node (ref "PI_ADC_1") (pin "1") (pinfunction "S_1") (pintype "passive"))
    )
    (net (code "133") (name "Net-(PI_ADC_1B-S)") (class "Default")
      (node (ref "F41") (pin "2") (pinfunction "2_2") (pintype "bidirectional"))
      (node (ref "PI_ADC_1") (pin "2") (pinfunction "S_2") (pintype "passive"))
    )
    (net (code "134") (name "Net-(PI_ADC_2A-S)") (class "Default")
      (node (ref "F38") (pin "2") (pinfunction "2_2") (pintype "bidirectional"))
      (node (ref "PI_ADC_2") (pin "1") (pinfunction "S_1") (pintype "passive"))
    )
    (net (code "135") (name "Net-(PI_ADC_2B-S)") (class "Default")
      (node (ref "F39") (pin "2") (pinfunction "2_2") (pintype "bidirectional"))
      (node (ref "PI_ADC_2") (pin "2") (pinfunction "S_2") (pintype "passive"))
    )
    (net (code "136") (name "Net-(PI_ADC_3A-S)") (class "Default")
      (node (ref "F42") (pin "2") (pinfunction "2_2") (pintype "bidirectional"))
      (node (ref "PI_ADC_3") (pin "1") (pinfunction "S_1") (pintype "passive"))
    )
    (net (code "137") (name "Net-(PI_ADC_3B-S)") (class "Default")
      (node (ref "F43") (pin "2") (pinfunction "2_2") (pintype "bidirectional"))
      (node (ref "PI_ADC_3") (pin "2") (pinfunction "S_2") (pintype "passive"))
    )
    (net (code "138") (name "Net-(PI_ADC_4A-S)") (class "Default")
      (node (ref "F44") (pin "2") (pinfunction "2_2") (pintype "bidirectional"))
      (node (ref "PI_ADC_4") (pin "1") (pinfunction "S_1") (pintype "passive"))
    )
    (net (code "139") (name "Net-(PI_ADC_4B-S)") (class "Default")
      (node (ref "F45") (pin "2") (pinfunction "2_2") (pintype "bidirectional"))
      (node (ref "PI_ADC_4") (pin "2") (pinfunction "S_2") (pintype "passive"))
    )
    (net (code "140") (name "Net-(PI_RS_485A-S)") (class "Default")
      (node (ref "F46") (pin "2") (pinfunction "2_2") (pintype "bidirectional"))
      (node (ref "PI_RS_485") (pin "1") (pinfunction "S_1") (pintype "passive"))
    )
    (net (code "141") (name "Net-(PI_RS_485B-S)") (class "Default")
      (node (ref "F47") (pin "2") (pinfunction "2_2") (pintype "bidirectional"))
      (node (ref "PI_RS_485") (pin "2") (pinfunction "S_2") (pintype "passive"))
    )
    (net (code "142") (name "Net-(PI_UARTA-S)") (class "Default")
      (node (ref "F50") (pin "2") (pinfunction "2_2") (pintype "bidirectional"))
      (node (ref "PI_UART") (pin "1") (pinfunction "S_1") (pintype "passive"))
    )
    (net (code "143") (name "Net-(PI_UARTB-S)") (class "Default")
      (node (ref "F51") (pin "2") (pinfunction "2_2") (pintype "bidirectional"))
      (node (ref "PI_UART") (pin "2") (pinfunction "S_2") (pintype "passive"))
    )
    (net (code "144") (name "Net-(PI_UART_HUB_2A-S)") (class "Default")
      (node (ref "F52") (pin "2") (pinfunction "2_2") (pintype "bidirectional"))
      (node (ref "PI_UART_HUB_2") (pin "1") (pinfunction "S_1") (pintype "passive"))
    )
    (net (code "145") (name "Net-(PI_UART_HUB_2B-S)") (class "Default")
      (node (ref "F53") (pin "2") (pinfunction "2_2") (pintype "bidirectional"))
      (node (ref "PI_UART_HUB_2") (pin "2") (pinfunction "S_2") (pintype "passive"))
    )
    (net (code "146") (name "Net-(PI_UART_HUB_3A-S)") (class "Default")
      (node (ref "F54") (pin "2") (pinfunction "2_2") (pintype "bidirectional"))
      (node (ref "PI_UART_HUB_3") (pin "1") (pinfunction "S_1") (pintype "passive"))
    )
    (net (code "147") (name "Net-(PI_UART_HUB_3B-S)") (class "Default")
      (node (ref "F55") (pin "2") (pinfunction "2_2") (pintype "bidirectional"))
      (node (ref "PI_UART_HUB_3") (pin "2") (pinfunction "S_2") (pintype "passive"))
    )
    (net (code "148") (name "Net-(Q2-G)") (class "Default")
      (node (ref "Q2") (pin "1") (pinfunction "G_1") (pintype "passive"))
      (node (ref "Q4") (pin "3") (pinfunction "D_3") (pintype "passive"))
      (node (ref "R39") (pin "1") (pinfunction "1_1") (pintype "passive"))
      (node (ref "TP12") (pin "TP") (pinfunction "TP_TP") (pintype "input"))
    )
    (net (code "149") (name "Net-(Q2-S)") (class "Default")
      (node (ref "Q2") (pin "2") (pinfunction "S_2") (pintype "passive"))
      (node (ref "Q5") (pin "3") (pinfunction "D_3") (pintype "passive"))
      (node (ref "TP10") (pin "TP") (pinfunction "TP_TP") (pintype "input"))
    )
    (net (code "150") (name "Net-(Q3-D)") (class "Default")
      (node (ref "Q3") (pin "3") (pinfunction "D_3") (pintype "passive"))
      (node (ref "U3") (pin "P$1") (pinfunction "RST_P$1") (pintype "bidirectional"))
    )
    (net (code "151") (name "Net-(Q3-G)") (class "Default")
      (node (ref "Q3") (pin "1") (pinfunction "G_1") (pintype "passive"))
      (node (ref "R15") (pin "2") (pinfunction "2_2") (pintype "passive"))
      (node (ref "R43") (pin "2") (pinfunction "2_2") (pintype "passive"))
    )
    (net (code "152") (name "Net-(Q7-D)") (class "Default")
      (node (ref "Q7") (pin "3") (pinfunction "D_3") (pintype "passive"))
      (node (ref "Q8") (pin "1") (pinfunction "G_1") (pintype "passive"))
      (node (ref "R46") (pin "1") (pinfunction "1_1") (pintype "passive"))
    )
    (net (code "153") (name "Net-(R25-Pad1)") (class "Default")
      (node (ref "R25") (pin "1") (pinfunction "1_1") (pintype "passive"))
      (node (ref "SW1") (pin "B") (pinfunction "B_B") (pintype "bidirectional"))
    )
    (net (code "154") (name "Net-(SPI_1A-S)") (class "Default")
      (node (ref "F28") (pin "2") (pinfunction "2_2") (pintype "bidirectional"))
      (node (ref "SPI_1") (pin "1") (pinfunction "S_1") (pintype "passive"))
    )
    (net (code "155") (name "Net-(SPI_1B-S)") (class "Default")
      (node (ref "F29") (pin "2") (pinfunction "2_2") (pintype "bidirectional"))
      (node (ref "SPI_1") (pin "2") (pinfunction "S_2") (pintype "passive"))
    )
    (net (code "156") (name "Net-(SPI_2A-S)") (class "Default")
      (node (ref "F2") (pin "2") (pinfunction "2_2") (pintype "bidirectional"))
      (node (ref "SPI_2") (pin "1") (pinfunction "S_1") (pintype "passive"))
    )
    (net (code "157") (name "Net-(SPI_2B-S)") (class "Default")
      (node (ref "F3") (pin "2") (pinfunction "2_2") (pintype "bidirectional"))
      (node (ref "SPI_2") (pin "2") (pinfunction "S_2") (pintype "passive"))
    )
    (net (code "158") (name "Net-(SPI_3A-S)") (class "Default")
      (node (ref "F4") (pin "2") (pinfunction "2_2") (pintype "bidirectional"))
      (node (ref "SPI_3") (pin "1") (pinfunction "S_1") (pintype "passive"))
    )
    (net (code "159") (name "Net-(SPI_3B-S)") (class "Default")
      (node (ref "F23") (pin "2") (pinfunction "2_2") (pintype "bidirectional"))
      (node (ref "SPI_3") (pin "2") (pinfunction "S_2") (pintype "passive"))
    )
    (net (code "160") (name "Net-(SPI_4B-S)") (class "Default")
      (node (ref "F25") (pin "2") (pinfunction "2_2") (pintype "bidirectional"))
      (node (ref "SPI_4") (pin "2") (pinfunction "S_2") (pintype "passive"))
    )
    (net (code "161") (name "Net-(SPI_5A-S)") (class "Default")
      (node (ref "F26") (pin "2") (pinfunction "2_2") (pintype "bidirectional"))
      (node (ref "SPI_5") (pin "1") (pinfunction "S_1") (pintype "passive"))
    )
    (net (code "162") (name "Net-(SPI_5B-S)") (class "Default")
      (node (ref "F27") (pin "2") (pinfunction "2_2") (pintype "bidirectional"))
      (node (ref "SPI_5") (pin "2") (pinfunction "S_2") (pintype "passive"))
    )
    (net (code "163") (name "Net-(SPI_6A-S)") (class "Default")
      (node (ref "F30") (pin "2") (pinfunction "2_2") (pintype "bidirectional"))
      (node (ref "SPI_6") (pin "1") (pinfunction "S_1") (pintype "passive"))
    )
    (net (code "164") (name "Net-(SPI_6B-S)") (class "Default")
      (node (ref "F31") (pin "2") (pinfunction "2_2") (pintype "bidirectional"))
      (node (ref "SPI_6") (pin "2") (pinfunction "S_2") (pintype "passive"))
    )
    (net (code "165") (name "Net-(SPI_7A-S)") (class "Default")
      (node (ref "F32") (pin "2") (pinfunction "2_2") (pintype "bidirectional"))
      (node (ref "SPI_7") (pin "1") (pinfunction "S_1") (pintype "passive"))
    )
    (net (code "166") (name "Net-(SPI_7B-S)") (class "Default")
      (node (ref "F33") (pin "2") (pinfunction "2_2") (pintype "bidirectional"))
      (node (ref "SPI_7") (pin "2") (pinfunction "S_2") (pintype "passive"))
    )
    (net (code "167") (name "Net-(SPI_8A-S)") (class "Default")
      (node (ref "F34") (pin "2") (pinfunction "2_2") (pintype "bidirectional"))
      (node (ref "SPI_8") (pin "1") (pinfunction "S_1") (pintype "passive"))
    )
    (net (code "168") (name "Net-(SPI_8B-S)") (class "Default")
      (node (ref "F35") (pin "2") (pinfunction "2_2") (pintype "bidirectional"))
      (node (ref "SPI_8") (pin "2") (pinfunction "S_2") (pintype "passive"))
    )
    (net (code "169") (name "Net-(U$3-G1)") (class "Default")
      (node (ref "C18") (pin "2") (pinfunction "2_2") (pintype "passive"))
      (node (ref "R20") (pin "2") (pinfunction "2_2") (pintype "passive"))
      (node (ref "TP16") (pin "TP") (pinfunction "TP_TP") (pintype "input"))
      (node (ref "U$3") (pin "3") (pinfunction "G1_3") (pintype "passive"))
      (node (ref "U11") (pin "1") (pinfunction "ANODE_1") (pintype "passive"))
    )
    (net (code "170") (name "Net-(U$6-DRV)") (class "Default")
      (node (ref "R42") (pin "2") (pinfunction "2_2") (pintype "passive"))
      (node (ref "TP15") (pin "TP") (pinfunction "TP_TP") (pintype "input"))
      (node (ref "U$6") (pin "22") (pinfunction "DRV_22") (pintype "bidirectional"))
    )
    (net (code "171") (name "Net-(U$6-LED1)") (class "Default")
      (node (ref "TP13") (pin "TP") (pinfunction "TP_TP") (pintype "input"))
      (node (ref "U$6") (pin "23") (pinfunction "LED1_23") (pintype "bidirectional"))
    )
    (net (code "172") (name "Net-(U$6-LED2)") (class "Default")
      (node (ref "TP14") (pin "TP") (pinfunction "TP_TP") (pintype "input"))
      (node (ref "U$6") (pin "24") (pinfunction "LED2_24") (pintype "bidirectional"))
    )
    (net (code "173") (name "Net-(U$6-REXT)") (class "Default")
      (node (ref "R28") (pin "2") (pinfunction "2_2") (pintype "passive"))
      (node (ref "U$6") (pin "14") (pinfunction "REXT_14") (pintype "bidirectional"))
    )
    (net (code "174") (name "Net-(U$6-VD18)") (class "Default")
      (node (ref "C26") (pin "+") (pinfunction "+_+") (pintype "passive"))
      (node (ref "C35") (pin "2") (pinfunction "2_2") (pintype "passive"))
      (node (ref "U$6") (pin "12") (pinfunction "VD18_O_12") (pintype "bidirectional"))
      (node (ref "U$6") (pin "28") (pinfunction "VD18_28") (pintype "bidirectional"))
    )
    (net (code "175") (name "Net-(U$6-VD33)") (class "Default")
      (node (ref "C34") (pin "+") (pinfunction "+_+") (pintype "passive"))
      (node (ref "C36") (pin "2") (pinfunction "2_2") (pintype "passive"))
      (node (ref "U$6") (pin "13") (pinfunction "VD33_13") (pintype "bidirectional"))
      (node (ref "U$6") (pin "21") (pinfunction "VD33_O_21") (pintype "bidirectional"))
    )
    (net (code "176") (name "Net-(U$6-XIN)") (class "Default")
      (node (ref "U$6") (pin "3") (pinfunction "XIN_3") (pintype "bidirectional"))
      (node (ref "Y2") (pin "2") (pinfunction "2_2") (pintype "passive"))
    )
    (net (code "177") (name "Net-(U$6-XOUT)") (class "Default")
      (node (ref "U$6") (pin "2") (pinfunction "XOUT_2") (pintype "bidirectional"))
      (node (ref "Y2") (pin "1") (pinfunction "1_1") (pintype "passive"))
    )
    (net (code "178") (name "Net-(U1-*RESET)") (class "Default")
      (node (ref "R2") (pin "1") (pinfunction "1_1") (pintype "passive"))
      (node (ref "U1") (pin "18") (pinfunction "*RESET_18") (pintype "output"))
    )
    (net (code "179") (name "Net-(U1-GPA0)") (class "Default")
      (node (ref "J5") (pin "1") (pinfunction "1_1") (pintype "passive"))
      (node (ref "J6") (pin "1") (pinfunction "1_1") (pintype "passive"))
      (node (ref "U1") (pin "21") (pinfunction "GPA0_21") (pintype "bidirectional"))
    )
    (net (code "180") (name "Net-(U1-GPA1)") (class "Default")
      (node (ref "J5") (pin "2") (pinfunction "2_2") (pintype "passive"))
      (node (ref "J6") (pin "2") (pinfunction "2_2") (pintype "passive"))
      (node (ref "U1") (pin "22") (pinfunction "GPA1_22") (pintype "bidirectional"))
    )
    (net (code "181") (name "Net-(U1-GPA2)") (class "Default")
      (node (ref "J5") (pin "3") (pinfunction "3_3") (pintype "passive"))
      (node (ref "J6") (pin "3") (pinfunction "3_3") (pintype "passive"))
      (node (ref "U1") (pin "23") (pinfunction "GPA2_23") (pintype "bidirectional"))
    )
    (net (code "182") (name "Net-(U1-GPA3)") (class "Default")
      (node (ref "J5") (pin "4") (pinfunction "4_4") (pintype "passive"))
      (node (ref "J6") (pin "4") (pinfunction "4_4") (pintype "passive"))
      (node (ref "U1") (pin "24") (pinfunction "GPA3_24") (pintype "bidirectional"))
    )
    (net (code "183") (name "Net-(U1-GPA4)") (class "Default")
      (node (ref "J5") (pin "5") (pinfunction "5_5") (pintype "passive"))
      (node (ref "J6") (pin "5") (pinfunction "5_5") (pintype "passive"))
      (node (ref "U1") (pin "25") (pinfunction "GPA4_25") (pintype "bidirectional"))
    )
    (net (code "184") (name "Net-(U1-GPA5)") (class "Default")
      (node (ref "J5") (pin "6") (pinfunction "6_6") (pintype "passive"))
      (node (ref "J6") (pin "6") (pinfunction "6_6") (pintype "passive"))
      (node (ref "U1") (pin "26") (pinfunction "GPA5_26") (pintype "bidirectional"))
    )
    (net (code "185") (name "Net-(U1-GPA6)") (class "Default")
      (node (ref "J5") (pin "7") (pinfunction "7_7") (pintype "passive"))
      (node (ref "J6") (pin "7") (pinfunction "7_7") (pintype "passive"))
      (node (ref "U1") (pin "27") (pinfunction "GPA6_27") (pintype "bidirectional"))
    )
    (net (code "186") (name "Net-(U1-GPA7)") (class "Default")
      (node (ref "J5") (pin "8") (pinfunction "8_8") (pintype "passive"))
      (node (ref "J6") (pin "8") (pinfunction "8_8") (pintype "passive"))
      (node (ref "U1") (pin "28") (pinfunction "GPA7_28") (pintype "bidirectional"))
    )
    (net (code "187") (name "Net-(U1-GPB0)") (class "Default")
      (node (ref "J5") (pin "9") (pinfunction "9_9") (pintype "passive"))
      (node (ref "J6") (pin "9") (pinfunction "9_9") (pintype "passive"))
      (node (ref "U1") (pin "1") (pinfunction "GPB0_1") (pintype "bidirectional"))
    )
    (net (code "188") (name "Net-(U1-GPB1)") (class "Default")
      (node (ref "J5") (pin "10") (pinfunction "10_10") (pintype "passive"))
      (node (ref "J6") (pin "10") (pinfunction "10_10") (pintype "passive"))
      (node (ref "U1") (pin "2") (pinfunction "GPB1_2") (pintype "bidirectional"))
    )
    (net (code "189") (name "Net-(U1-GPB2)") (class "Default")
      (node (ref "J5") (pin "11") (pinfunction "11_11") (pintype "passive"))
      (node (ref "J6") (pin "11") (pinfunction "11_11") (pintype "passive"))
      (node (ref "U1") (pin "3") (pinfunction "GPB2_3") (pintype "bidirectional"))
    )
    (net (code "190") (name "Net-(U1-GPB3)") (class "Default")
      (node (ref "J5") (pin "12") (pinfunction "12_12") (pintype "passive"))
      (node (ref "J6") (pin "12") (pinfunction "12_12") (pintype "passive"))
      (node (ref "U1") (pin "4") (pinfunction "GPB3_4") (pintype "bidirectional"))
    )
    (net (code "191") (name "Net-(U1-GPB4)") (class "Default")
      (node (ref "J5") (pin "13") (pinfunction "13_13") (pintype "passive"))
      (node (ref "J6") (pin "13") (pinfunction "13_13") (pintype "passive"))
      (node (ref "U1") (pin "5") (pinfunction "GPB4_5") (pintype "bidirectional"))
    )
    (net (code "192") (name "Net-(U1-GPB5)") (class "Default")
      (node (ref "J5") (pin "14") (pinfunction "14_14") (pintype "passive"))
      (node (ref "J6") (pin "14") (pinfunction "14_14") (pintype "passive"))
      (node (ref "U1") (pin "6") (pinfunction "GPB5_6") (pintype "bidirectional"))
    )
    (net (code "193") (name "Net-(U1-GPB6)") (class "Default")
      (node (ref "J5") (pin "15") (pinfunction "15_15") (pintype "passive"))
      (node (ref "J6") (pin "15") (pinfunction "15_15") (pintype "passive"))
      (node (ref "U1") (pin "7") (pinfunction "GPB6_7") (pintype "bidirectional"))
    )
    (net (code "194") (name "Net-(U1-GPB7)") (class "Default")
      (node (ref "J5") (pin "16") (pinfunction "16_16") (pintype "passive"))
      (node (ref "J6") (pin "16") (pinfunction "16_16") (pintype "passive"))
      (node (ref "U1") (pin "8") (pinfunction "GPB7_8") (pintype "bidirectional"))
    )
    (net (code "195") (name "Net-(U4-C1+)") (class "Default")
      (node (ref "C21") (pin "1") (pinfunction "1_1") (pintype "passive"))
      (node (ref "U4") (pin "12") (pinfunction "C1+_12") (pintype "input"))
    )
    (net (code "196") (name "Net-(U4-C1-)") (class "Default")
      (node (ref "C21") (pin "2") (pinfunction "2_2") (pintype "passive"))
      (node (ref "U4") (pin "14") (pinfunction "C1-_14") (pintype "input"))
    )
    (net (code "197") (name "Net-(U4-C2+)") (class "Default")
      (node (ref "C24") (pin "2") (pinfunction "2_2") (pintype "passive"))
      (node (ref "U4") (pin "15") (pinfunction "C2+_15") (pintype "input"))
    )
    (net (code "198") (name "Net-(U4-C2-)") (class "Default")
      (node (ref "C24") (pin "1") (pinfunction "1_1") (pintype "passive"))
      (node (ref "U4") (pin "16") (pinfunction "C2-_16") (pintype "input"))
    )
    (net (code "199") (name "Net-(U4-V+)") (class "Default")
      (node (ref "C20") (pin "1") (pinfunction "1_1") (pintype "passive"))
      (node (ref "U4") (pin "13") (pinfunction "V+_13") (pintype "output"))
    )
    (net (code "200") (name "Net-(U4-V-)") (class "Default")
      (node (ref "C22") (pin "1") (pinfunction "1_1") (pintype "passive"))
      (node (ref "U4") (pin "17") (pinfunction "V-_17") (pintype "input"))
    )
    (net (code "201") (name "Net-(U5-CBUS0)") (class "Default")
      (node (ref "D7") (pin "-") (pinfunction "-_-") (pintype "passive"))
      (node (ref "U5") (pin "23") (pinfunction "CBUS0_23") (pintype "input"))
    )
    (net (code "202") (name "Net-(U5-CBUS1)") (class "Default")
      (node (ref "D15") (pin "-") (pinfunction "-_-") (pintype "passive"))
      (node (ref "U5") (pin "22") (pinfunction "CBUS1_22") (pintype "input"))
    )
    (net (code "203") (name "Net-(U6-CBUS0)") (class "Default")
      (node (ref "D2") (pin "-") (pinfunction "-_-") (pintype "passive"))
      (node (ref "U6") (pin "23") (pinfunction "CBUS0_23") (pintype "input"))
    )
    (net (code "204") (name "Net-(U6-CBUS1)") (class "Default")
      (node (ref "D3") (pin "-") (pinfunction "-_-") (pintype "passive"))
      (node (ref "U6") (pin "22") (pinfunction "CBUS1_22") (pintype "input"))
    )
    (net (code "205") (name "Net-(U6-RXD)") (class "Default")
      (node (ref "R14") (pin "1") (pinfunction "1_1") (pintype "passive"))
      (node (ref "U6") (pin "5") (pinfunction "RXD_5") (pintype "input"))
    )
    (net (code "206") (name "Net-(U6-TXD)") (class "Default")
      (node (ref "R13") (pin "1") (pinfunction "1_1") (pintype "passive"))
      (node (ref "U6") (pin "1") (pinfunction "TXD_1") (pintype "input"))
    )
    (net (code "207") (name "Net-(U8-WP)") (class "Default")
      (node (ref "J8") (pin "1") (pinfunction "1_1") (pintype "bidirectional"))
      (node (ref "R36") (pin "1") (pinfunction "1_1") (pintype "passive"))
      (node (ref "TP6") (pin "TP") (pinfunction "TP_TP") (pintype "input"))
      (node (ref "U8") (pin "7") (pinfunction "WP_7") (pintype "input"))
    )
    (net (code "208") (name "Net-(U13-CBUS0)") (class "Default")
      (node (ref "D16") (pin "-") (pinfunction "-_-") (pintype "passive"))
      (node (ref "U13") (pin "23") (pinfunction "CBUS0_23") (pintype "input"))
    )
    (net (code "209") (name "Net-(U13-CBUS1)") (class "Default")
      (node (ref "D17") (pin "-") (pinfunction "-_-") (pintype "passive"))
      (node (ref "U13") (pin "22") (pinfunction "CBUS1_22") (pintype "input"))
    )
    (net (code "210") (name "Net-(U14-CBUS0)") (class "Default")
      (node (ref "D18") (pin "-") (pinfunction "-_-") (pintype "passive"))
      (node (ref "U14") (pin "23") (pinfunction "CBUS0_23") (pintype "input"))
    )
    (net (code "211") (name "Net-(U14-CBUS1)") (class "Default")
      (node (ref "D19") (pin "-") (pinfunction "-_-") (pintype "passive"))
      (node (ref "U14") (pin "22") (pinfunction "CBUS1_22") (pintype "input"))
    )
    (net (code "212") (name "Net-(U15-CBUS0)") (class "Default")
      (node (ref "D20") (pin "-") (pinfunction "-_-") (pintype "passive"))
      (node (ref "U15") (pin "23") (pinfunction "CBUS0_23") (pintype "input"))
    )
    (net (code "213") (name "Net-(U15-CBUS1)") (class "Default")
      (node (ref "D21") (pin "-") (pinfunction "-_-") (pintype "passive"))
      (node (ref "U15") (pin "22") (pinfunction "CBUS1_22") (pintype "input"))
    )
    (net (code "214") (name "Net-(USB3-VBUS)") (class "Default")
      (node (ref "C9") (pin "2") (pinfunction "2_2") (pintype "passive"))
      (node (ref "L1") (pin "1") (pinfunction "1_1") (pintype "passive"))
      (node (ref "USB3") (pin "1") (pinfunction "VBUS_1") (pintype "power_in"))
    )
    (net (code "215") (name "P2_SIG") (class "Default")
      (node (ref "Q6") (pin "1") (pinfunction "G_1") (pintype "passive"))
      (node (ref "R41") (pin "1") (pinfunction "1_1") (pintype "passive"))
      (node (ref "R44") (pin "2") (pinfunction "2_2") (pintype "passive"))
    )
    (net (code "216") (name "P12_SIG") (class "Default")
      (node (ref "Q7") (pin "1") (pinfunction "G_1") (pintype "passive"))
      (node (ref "R17") (pin "1") (pinfunction "1_1") (pintype "passive"))
      (node (ref "R45") (pin "2") (pinfunction "2_2") (pintype "passive"))
    )
    (net (code "217") (name "PI_5V") (class "Default")
      (node (ref "C13") (pin "2") (pinfunction "2_2") (pintype "passive"))
      (node (ref "F11") (pin "1") (pinfunction "1_1") (pintype "bidirectional"))
      (node (ref "F13") (pin "1") (pinfunction "1_1") (pintype "bidirectional"))
      (node (ref "F15") (pin "1") (pinfunction "1_1") (pintype "bidirectional"))
      (node (ref "F17") (pin "1") (pinfunction "1_1") (pintype "bidirectional"))
      (node (ref "F19") (pin "1") (pinfunction "1_1") (pintype "bidirectional"))
      (node (ref "F2") (pin "1") (pinfunction "1_1") (pintype "bidirectional"))
      (node (ref "F21") (pin "1") (pinfunction "1_1") (pintype "bidirectional"))
      (node (ref "F24") (pin "1") (pinfunction "1_1") (pintype "bidirectional"))
      (node (ref "F26") (pin "1") (pinfunction "1_1") (pintype "bidirectional"))
      (node (ref "F28") (pin "1") (pinfunction "1_1") (pintype "bidirectional"))
      (node (ref "F30") (pin "1") (pinfunction "1_1") (pintype "bidirectional"))
      (node (ref "F32") (pin "1") (pinfunction "1_1") (pintype "bidirectional"))
      (node (ref "F34") (pin "1") (pinfunction "1_1") (pintype "bidirectional"))
      (node (ref "F36") (pin "1") (pinfunction "1_1") (pintype "bidirectional"))
      (node (ref "F38") (pin "1") (pinfunction "1_1") (pintype "bidirectional"))
      (node (ref "F4") (pin "1") (pinfunction "1_1") (pintype "bidirectional"))
      (node (ref "F40") (pin "1") (pinfunction "1_1") (pintype "bidirectional"))
      (node (ref "F42") (pin "1") (pinfunction "1_1") (pintype "bidirectional"))
      (node (ref "F44") (pin "1") (pinfunction "1_1") (pintype "bidirectional"))
      (node (ref "F46") (pin "1") (pinfunction "1_1") (pintype "bidirectional"))
      (node (ref "F48") (pin "1") (pinfunction "1_1") (pintype "bidirectional"))
      (node (ref "F5") (pin "1") (pinfunction "1_1") (pintype "bidirectional"))
      (node (ref "F50") (pin "1") (pinfunction "1_1") (pintype "bidirectional"))
      (node (ref "F52") (pin "1") (pinfunction "1_1") (pintype "bidirectional"))
      (node (ref "F54") (pin "1") (pinfunction "1_1") (pintype "bidirectional"))
      (node (ref "F60") (pin "1") (pinfunction "1_1") (pintype "bidirectional"))
      (node (ref "F7") (pin "1") (pinfunction "1_1") (pintype "bidirectional"))
      (node (ref "F9") (pin "1") (pinfunction "1_1") (pintype "bidirectional"))
      (node (ref "PCB1") (pin "P$2") (pinfunction "5V_P$2") (pintype "bidirectional"))
      (node (ref "PCB1") (pin "P$4") (pinfunction "5V_P$4") (pintype "bidirectional"))
      (node (ref "Q5") (pin "2") (pinfunction "S_2") (pintype "passive"))
      (node (ref "R21") (pin "2") (pinfunction "2_2") (pintype "passive"))
      (node (ref "TP11") (pin "TP") (pinfunction "TP_TP") (pintype "input"))
      (node (ref "U10") (pin "16") (pinfunction "VCC_16") (pintype "power_in"))
    )
    (net (code "218") (name "PI_PWR_CTRL") (class "Default")
      (node (ref "Q4") (pin "1") (pinfunction "G_1") (pintype "passive"))
      (node (ref "R4") (pin "2") (pinfunction "2_2") (pintype "passive"))
      (node (ref "R40") (pin "2") (pinfunction "2_2") (pintype "passive"))
      (node (ref "SW3") (pin "COM") (pinfunction "COM_COM") (pintype "bidirectional"))
      (node (ref "TP9") (pin "TP") (pinfunction "TP_TP") (pintype "input"))
      (node (ref "U3") (pin "P$15") (pinfunction "P13_P$15") (pintype "input"))
    )
    (net (code "219") (name "PI_TTL_RXD") (class "Default")
      (node (ref "PCB1") (pin "P$10") (pinfunction "GPIO15_P$10") (pintype "bidirectional"))
      (node (ref "PI_UART") (pin "4") (pinfunction "S_4") (pintype "passive"))
      (node (ref "R12") (pin "2") (pinfunction "2_2") (pintype "passive"))
    )
    (net (code "220") (name "PI_TTL_TXD") (class "Default")
      (node (ref "PCB1") (pin "P$8") (pinfunction "GPIO14_P$8") (pintype "bidirectional"))
      (node (ref "PI_UART") (pin "3") (pinfunction "S_3") (pintype "passive"))
      (node (ref "R8") (pin "2") (pinfunction "2_2") (pintype "passive"))
    )
    (net (code "221") (name "RPI_CS1") (class "Default")
      (node (ref "SPI_1") (pin "3") (pinfunction "S_3") (pintype "passive"))
      (node (ref "U10") (pin "4") (pinfunction "1~{Y0}_4") (pintype "output"))
    )
    (net (code "222") (name "RPI_CS2") (class "Default")
      (node (ref "SPI_2") (pin "3") (pinfunction "S_3") (pintype "passive"))
      (node (ref "U10") (pin "5") (pinfunction "1~{Y1}_5") (pintype "output"))
    )
    (net (code "223") (name "RPI_CS3") (class "Default")
      (node (ref "SPI_3") (pin "3") (pinfunction "S_3") (pintype "passive"))
      (node (ref "U10") (pin "6") (pinfunction "1~{Y2}_6") (pintype "output"))
    )
    (net (code "224") (name "RPI_CS4") (class "Default")
      (node (ref "SPI_4") (pin "3") (pinfunction "S_3") (pintype "passive"))
      (node (ref "U10") (pin "7") (pinfunction "1~{Y3}_7") (pintype "output"))
    )
    (net (code "225") (name "RPI_CS5") (class "Default")
      (node (ref "SPI_5") (pin "3") (pinfunction "S_3") (pintype "passive"))
      (node (ref "U10") (pin "12") (pinfunction "2~{Y0}_12") (pintype "output"))
    )
    (net (code "226") (name "RPI_CS6") (class "Default")
      (node (ref "SPI_6") (pin "3") (pinfunction "S_3") (pintype "passive"))
      (node (ref "U10") (pin "11") (pinfunction "2~{Y1}_11") (pintype "output"))
    )
    (net (code "227") (name "RPI_CS7") (class "Default")
      (node (ref "SPI_7") (pin "3") (pinfunction "S_3") (pintype "passive"))
      (node (ref "U10") (pin "10") (pinfunction "2~{Y2}_10") (pintype "output"))
    )
    (net (code "228") (name "RPI_CS8") (class "Default")
      (node (ref "SPI_8") (pin "3") (pinfunction "S_3") (pintype "passive"))
      (node (ref "U10") (pin "9") (pinfunction "2~{Y3}_9") (pintype "output"))
    )
    (net (code "229") (name "RS232_1_RXD") (class "Default")
      (node (ref "I_UART_HUB_1") (pin "4") (pinfunction "S_4") (pintype "passive"))
      (node (ref "U4") (pin "9") (pinfunction "RIN1_9") (pintype "input"))
    )
    (net (code "230") (name "RS232_1_TXD") (class "Default")
      (node (ref "I_UART_HUB_1") (pin "3") (pinfunction "S_3") (pintype "passive"))
      (node (ref "U4") (pin "2") (pinfunction "DOUT1_2") (pintype "output"))
    )
    (net (code "231") (name "RS232_2_RXD") (class "Default")
      (node (ref "PI_UART_HUB_2") (pin "4") (pinfunction "S_4") (pintype "passive"))
      (node (ref "U4") (pin "4") (pinfunction "RIN2_4") (pintype "input"))
    )
    (net (code "232") (name "RS232_2_TXD") (class "Default")
      (node (ref "PI_UART_HUB_2") (pin "3") (pinfunction "S_3") (pintype "passive"))
      (node (ref "U4") (pin "3") (pinfunction "DOUT2_3") (pintype "output"))
    )
    (net (code "233") (name "RS232_3_RXD") (class "Default")
      (node (ref "PI_UART_HUB_3") (pin "4") (pinfunction "S_4") (pintype "passive"))
      (node (ref "U4") (pin "27") (pinfunction "RIN3_27") (pintype "input"))
    )
    (net (code "234") (name "RS232_3_TXD") (class "Default")
      (node (ref "PI_UART_HUB_3") (pin "3") (pinfunction "S_3") (pintype "passive"))
      (node (ref "U4") (pin "1") (pinfunction "DOUT3_1") (pintype "output"))
    )
    (net (code "235") (name "RS485_A") (class "Default")
      (node (ref "PI_RS_485") (pin "3") (pinfunction "S_3") (pintype "passive"))
      (node (ref "SW1") (pin "COM") (pinfunction "COM_COM") (pintype "bidirectional"))
      (node (ref "U12") (pin "6") (pinfunction "A_6") (pintype "bidirectional"))
    )
    (net (code "236") (name "RS485_B") (class "Default")
      (node (ref "PI_RS_485") (pin "4") (pinfunction "S_4") (pintype "passive"))
      (node (ref "R25") (pin "2") (pinfunction "2_2") (pintype "passive"))
      (node (ref "U12") (pin "7") (pinfunction "B_7") (pintype "bidirectional"))
    )
    (net (code "237") (name "RTC_BATT") (class "Default")
      (node (ref "BAT1") (pin "+1") (pinfunction "V+_+1") (pintype "bidirectional"))
      (node (ref "BAT1") (pin "+2") (pinfunction "V+_+2") (pintype "bidirectional"))
      (node (ref "TP17") (pin "TP") (pinfunction "TP_TP") (pintype "input"))
      (node (ref "U2") (pin "3") (pinfunction "VBAT_3") (pintype "power_in"))
    )
    (net (code "238") (name "RXD1") (class "Default")
      (node (ref "U13") (pin "5") (pinfunction "RXD_5") (pintype "input"))
      (node (ref "U4") (pin "8") (pinfunction "ROUT1_8") (pintype "output"))
    )
    (net (code "239") (name "RXD2") (class "Default")
      (node (ref "U14") (pin "5") (pinfunction "RXD_5") (pintype "input"))
      (node (ref "U4") (pin "5") (pinfunction "ROUT2_5") (pintype "output"))
    )
    (net (code "240") (name "RXD3") (class "Default")
      (node (ref "U15") (pin "5") (pinfunction "RXD_5") (pintype "input"))
      (node (ref "U4") (pin "26") (pinfunction "ROUT3_26") (pintype "output"))
    )
    (net (code "241") (name "SCL_3V3") (class "Default")
      (node (ref "I2C_1") (pin "4") (pinfunction "S_4") (pintype "passive"))
      (node (ref "I2C_10") (pin "4") (pinfunction "S_4") (pintype "passive"))
      (node (ref "I2C_2") (pin "4") (pinfunction "S_4") (pintype "passive"))
      (node (ref "I2C_3") (pin "4") (pinfunction "S_4") (pintype "passive"))
      (node (ref "I2C_4") (pin "4") (pinfunction "S_4") (pintype "passive"))
      (node (ref "I2C_5") (pin "4") (pinfunction "S_4") (pintype "passive"))
      (node (ref "I2C_6") (pin "4") (pinfunction "S_4") (pintype "passive"))
      (node (ref "I2C_7") (pin "4") (pinfunction "S_4") (pintype "passive"))
      (node (ref "I2C_8") (pin "4") (pinfunction "S_4") (pintype "passive"))
      (node (ref "I2C_9") (pin "4") (pinfunction "S_4") (pintype "passive"))
      (node (ref "PCB1") (pin "P$5") (pinfunction "GPIO3_P$5") (pintype "bidirectional"))
      (node (ref "R18") (pin "1") (pinfunction "1_1") (pintype "passive"))
      (node (ref "U$1") (pin "8") (pinfunction "SCL_8") (pintype "input"))
      (node (ref "U$2") (pin "8") (pinfunction "SCL_8") (pintype "input"))
      (node (ref "U1") (pin "12") (pinfunction "SCL_12") (pintype "input"))
      (node (ref "U2") (pin "6") (pinfunction "SCL_6") (pintype "passive"))
    )
    (net (code "242") (name "SDA_3V3") (class "Default")
      (node (ref "I2C_1") (pin "3") (pinfunction "S_3") (pintype "passive"))
      (node (ref "I2C_10") (pin "3") (pinfunction "S_3") (pintype "passive"))
      (node (ref "I2C_2") (pin "3") (pinfunction "S_3") (pintype "passive"))
      (node (ref "I2C_3") (pin "3") (pinfunction "S_3") (pintype "passive"))
      (node (ref "I2C_4") (pin "3") (pinfunction "S_3") (pintype "passive"))
      (node (ref "I2C_5") (pin "3") (pinfunction "S_3") (pintype "passive"))
      (node (ref "I2C_6") (pin "3") (pinfunction "S_3") (pintype "passive"))
      (node (ref "I2C_7") (pin "3") (pinfunction "S_3") (pintype "passive"))
      (node (ref "I2C_8") (pin "3") (pinfunction "S_3") (pintype "passive"))
      (node (ref "I2C_9") (pin "3") (pinfunction "S_3") (pintype "passive"))
      (node (ref "PCB1") (pin "P$3") (pinfunction "GPIO2_P$3") (pintype "bidirectional"))
      (node (ref "R19") (pin "1") (pinfunction "1_1") (pintype "passive"))
      (node (ref "U$1") (pin "7") (pinfunction "SDA_7") (pintype "bidirectional"))
      (node (ref "U$2") (pin "7") (pinfunction "SDA_7") (pintype "bidirectional"))
      (node (ref "U1") (pin "13") (pinfunction "SDA_13") (pintype "bidirectional"))
      (node (ref "U2") (pin "5") (pinfunction "SDA_5") (pintype "passive"))
    )
    (net (code "243") (name "SPI0_CS0") (class "Default")
      (node (ref "PCB1") (pin "P$24") (pinfunction "GPIO8_P$24") (pintype "bidirectional"))
      (node (ref "U10") (pin "1") (pinfunction "1~{E}_1") (pintype "input"))
    )
    (net (code "244") (name "SPI0_CS1") (class "Default")
      (node (ref "PCB1") (pin "P$26") (pinfunction "GPIO7_P$26") (pintype "bidirectional"))
      (node (ref "U10") (pin "15") (pinfunction "2~{E}_15") (pintype "input"))
    )
    (net (code "245") (name "SPI_5V_4_P") (class "Default")
      (node (ref "F24") (pin "2") (pinfunction "2_2") (pintype "bidirectional"))
      (node (ref "SPI_4") (pin "1") (pinfunction "S_1") (pintype "passive"))
    )
    (net (code "246") (name "SPI_GPIO1") (class "Default")
      (node (ref "PCB1") (pin "P$11") (pinfunction "GPIO17_P$11") (pintype "bidirectional"))
      (node (ref "U10") (pin "2") (pinfunction "1A0_2") (pintype "input"))
    )
    (net (code "247") (name "SPI_GPIO2") (class "Default")
      (node (ref "PCB1") (pin "P$13") (pinfunction "GPIO27_P$13") (pintype "bidirectional"))
      (node (ref "U10") (pin "3") (pinfunction "1A1_3") (pintype "input"))
    )
    (net (code "248") (name "SPI_GPIO3") (class "Default")
      (node (ref "PCB1") (pin "P$15") (pinfunction "GPIO22_P$15") (pintype "bidirectional"))
      (node (ref "U10") (pin "14") (pinfunction "2A0_14") (pintype "input"))
    )
    (net (code "249") (name "SPI_GPIO4") (class "Default")
      (node (ref "PCB1") (pin "P$16") (pinfunction "GPIO23_P$16") (pintype "bidirectional"))
      (node (ref "U10") (pin "13") (pinfunction "2A1_13") (pintype "input"))
    )
    (net (code "250") (name "SPI_MISO") (class "Default")
      (node (ref "PCB1") (pin "P$21") (pinfunction "GPIO9_P$21") (pintype "bidirectional"))
      (node (ref "SPI_1") (pin "5") (pinfunction "S_5") (pintype "passive"))
      (node (ref "SPI_2") (pin "5") (pinfunction "S_5") (pintype "passive"))
      (node (ref "SPI_3") (pin "5") (pinfunction "S_5") (pintype "passive"))
      (node (ref "SPI_4") (pin "5") (pinfunction "S_5") (pintype "passive"))
      (node (ref "SPI_5") (pin "5") (pinfunction "S_5") (pintype "passive"))
      (node (ref "SPI_6") (pin "5") (pinfunction "S_5") (pintype "passive"))
      (node (ref "SPI_7") (pin "5") (pinfunction "S_5") (pintype "passive"))
      (node (ref "SPI_8") (pin "5") (pinfunction "S_5") (pintype "passive"))
    )
    (net (code "251") (name "SPI_MOSI") (class "Default")
      (node (ref "PCB1") (pin "P$19") (pinfunction "GPIO10_P$19") (pintype "bidirectional"))
      (node (ref "SPI_1") (pin "4") (pinfunction "S_4") (pintype "passive"))
      (node (ref "SPI_2") (pin "4") (pinfunction "S_4") (pintype "passive"))
      (node (ref "SPI_3") (pin "4") (pinfunction "S_4") (pintype "passive"))
      (node (ref "SPI_4") (pin "4") (pinfunction "S_4") (pintype "passive"))
      (node (ref "SPI_5") (pin "4") (pinfunction "S_4") (pintype "passive"))
      (node (ref "SPI_6") (pin "4") (pinfunction "S_4") (pintype "passive"))
      (node (ref "SPI_7") (pin "4") (pinfunction "S_4") (pintype "passive"))
      (node (ref "SPI_8") (pin "4") (pinfunction "S_4") (pintype "passive"))
    )
    (net (code "252") (name "SPI_SCLK") (class "Default")
      (node (ref "PCB1") (pin "P$23") (pinfunction "GPIO11_P$23") (pintype "bidirectional"))
      (node (ref "SPI_1") (pin "6") (pinfunction "S_6") (pintype "passive"))
      (node (ref "SPI_2") (pin "6") (pinfunction "S_6") (pintype "passive"))
      (node (ref "SPI_3") (pin "6") (pinfunction "S_6") (pintype "passive"))
      (node (ref "SPI_4") (pin "6") (pinfunction "S_6") (pintype "passive"))
      (node (ref "SPI_5") (pin "6") (pinfunction "S_6") (pintype "passive"))
      (node (ref "SPI_6") (pin "6") (pinfunction "S_6") (pintype "passive"))
      (node (ref "SPI_7") (pin "6") (pinfunction "S_6") (pintype "passive"))
      (node (ref "SPI_8") (pin "6") (pinfunction "S_6") (pintype "passive"))
    )
    (net (code "253") (name "TXD1") (class "Default")
      (node (ref "U13") (pin "1") (pinfunction "TXD_1") (pintype "input"))
      (node (ref "U4") (pin "7") (pinfunction "DIN1_7") (pintype "input"))
    )
    (net (code "254") (name "TXD2") (class "Default")
      (node (ref "U14") (pin "1") (pinfunction "TXD_1") (pintype "input"))
      (node (ref "U4") (pin "6") (pinfunction "DIN2_6") (pintype "input"))
    )
    (net (code "255") (name "TXD3") (class "Default")
      (node (ref "U15") (pin "1") (pinfunction "TXD_1") (pintype "input"))
      (node (ref "U4") (pin "20") (pinfunction "DIN3_20") (pintype "input"))
    )
    (net (code "256") (name "USB1_DM") (class "Default")
      (node (ref "U$6") (pin "10") (pinfunction "DM1_10") (pintype "bidirectional"))
      (node (ref "U5") (pin "16") (pinfunction "USBDM_16") (pintype "input"))
    )
    (net (code "257") (name "USB1_DP") (class "Default")
      (node (ref "U$6") (pin "11") (pinfunction "DP1_11") (pintype "bidirectional"))
      (node (ref "U5") (pin "15") (pinfunction "USBDP_15") (pintype "input"))
    )
    (net (code "258") (name "USB2_DM") (class "Default")
      (node (ref "U$6") (pin "8") (pinfunction "DM2_8") (pintype "bidirectional"))
      (node (ref "U13") (pin "16") (pinfunction "USBDM_16") (pintype "input"))
    )
    (net (code "259") (name "USB2_DP") (class "Default")
      (node (ref "U$6") (pin "9") (pinfunction "DP2_9") (pintype "bidirectional"))
      (node (ref "U13") (pin "15") (pinfunction "USBDP_15") (pintype "input"))
    )
    (net (code "260") (name "USB3_DM") (class "Default")
      (node (ref "U$6") (pin "4") (pinfunction "DM4_4") (pintype "bidirectional"))
      (node (ref "U14") (pin "16") (pinfunction "USBDM_16") (pintype "input"))
    )
    (net (code "261") (name "USB3_DP") (class "Default")
      (node (ref "U$6") (pin "5") (pinfunction "DP4_5") (pintype "bidirectional"))
      (node (ref "U14") (pin "15") (pinfunction "USBDP_15") (pintype "input"))
    )
    (net (code "262") (name "USB4_DM") (class "Default")
      (node (ref "U$6") (pin "6") (pinfunction "DM3_6") (pintype "bidirectional"))
      (node (ref "U15") (pin "16") (pinfunction "USBDM_16") (pintype "input"))
    )
    (net (code "263") (name "USB4_DP") (class "Default")
      (node (ref "U$6") (pin "7") (pinfunction "DP3_7") (pintype "bidirectional"))
      (node (ref "U15") (pin "15") (pinfunction "USBDP_15") (pintype "input"))
    )
    (net (code "264") (name "USB_DM") (class "Default")
      (node (ref "U6") (pin "16") (pinfunction "USBDM_16") (pintype "input"))
      (node (ref "USB3") (pin "2") (pinfunction "D-_2") (pintype "bidirectional"))
    )
    (net (code "265") (name "USB_DP") (class "Default")
      (node (ref "U6") (pin "15") (pinfunction "USBDP_15") (pintype "input"))
      (node (ref "USB3") (pin "3") (pinfunction "D+_3") (pintype "bidirectional"))
    )
    (net (code "266") (name "USB_HUB_DM") (class "Default")
      (node (ref "U$6") (pin "15") (pinfunction "DMU_15") (pintype "bidirectional"))
      (node (ref "USB1") (pin "2") (pinfunction "D-_2") (pintype "bidirectional"))
    )
    (net (code "267") (name "USB_HUB_DP") (class "Default")
      (node (ref "U$6") (pin "16") (pinfunction "DPU_16") (pintype "bidirectional"))
      (node (ref "USB1") (pin "3") (pinfunction "D+_3") (pintype "bidirectional"))
    )
    (net (code "268") (name "USB_HUB_VD33_O") (class "Default")
      (node (ref "U$6") (pin "17") (pinfunction "XRSTJ_17") (pintype "bidirectional"))
      (node (ref "U$6") (pin "18") (pinfunction "VBUSM_18") (pintype "bidirectional"))
      (node (ref "U$6") (pin "19") (pinfunction "BUSJ_19") (pintype "bidirectional"))
      (node (ref "U$6") (pin "26") (pinfunction "OVCJ_26") (pintype "bidirectional"))
    )
    (net (code "269") (name "X1_RTC") (class "Default")
      (node (ref "C1") (pin "1") (pinfunction "1_1") (pintype "passive"))
      (node (ref "Q1") (pin "1") (pinfunction "1_1") (pintype "passive"))
      (node (ref "U2") (pin "1") (pinfunction "X1_1") (pintype "input"))
    )
    (net (code "270") (name "X2_RTC") (class "Default")
      (node (ref "C3") (pin "1") (pinfunction "1_1") (pintype "passive"))
      (node (ref "Q1") (pin "4") (pinfunction "2_4") (pintype "passive"))
      (node (ref "U2") (pin "2") (pinfunction "X2_2") (pintype "input"))
    )
    (net (code "271") (name "unconnected-(J2-CDN-Pad9)") (class "Default")
      (node (ref "J2") (pin "9") (pinfunction "CDN_9") (pintype "bidirectional"))
    )
    (net (code "272") (name "unconnected-(J2-DATA1-Pad8)") (class "Default")
      (node (ref "J2") (pin "8") (pinfunction "DATA1_8") (pintype "bidirectional"))
    )
    (net (code "273") (name "unconnected-(J2-DATA2-Pad1)") (class "Default")
      (node (ref "J2") (pin "1") (pinfunction "DATA2_1") (pintype "bidirectional"))
    )
    (net (code "274") (name "unconnected-(PCB1-RUN_1-PadP$41)") (class "Default")
      (node (ref "PCB1") (pin "P$41") (pinfunction "RUN_1_P$41") (pintype "bidirectional"))
    )
    (net (code "275") (name "unconnected-(PCB1-RUN_2-PadP$42)") (class "Default")
      (node (ref "PCB1") (pin "P$42") (pinfunction "RUN_2_P$42") (pintype "bidirectional"))
    )
    (net (code "276") (name "unconnected-(SW1-PadA)") (class "Default")
      (node (ref "SW1") (pin "A") (pinfunction "A_A") (pintype "bidirectional"))
    )
    (net (code "277") (name "unconnected-(SW3-PadA)") (class "Default")
      (node (ref "SW3") (pin "A") (pinfunction "A_A") (pintype "bidirectional"))
    )
    (net (code "278") (name "unconnected-(SW4-PadA)") (class "Default")
      (node (ref "SW4") (pin "A") (pinfunction "A_A") (pintype "bidirectional"))
    )
    (net (code "279") (name "unconnected-(U$2-ADR1-Pad10)") (class "Default")
      (node (ref "U$2") (pin "10") (pinfunction "ADR1_10") (pintype "input"))
    )
    (net (code "280") (name "unconnected-(U$6-PWRJ-Pad25)") (class "Default")
      (node (ref "U$6") (pin "25") (pinfunction "PWRJ_25") (pintype "bidirectional"))
    )
    (net (code "281") (name "unconnected-(U$6-TESTJ-Pad27)") (class "Default")
      (node (ref "U$6") (pin "27") (pinfunction "TESTJ_27") (pintype "bidirectional"))
    )
    (net (code "282") (name "unconnected-(U$7-N.C.-Pad3)") (class "Default")
      (node (ref "U$7") (pin "3") (pinfunction "N.C._3") (pintype "passive"))
    )
    (net (code "283") (name "unconnected-(U1-NC-Pad11)") (class "Default")
      (node (ref "U1") (pin "11") (pinfunction "NC_11") (pintype "no_connect"))
    )
    (net (code "284") (name "unconnected-(U1-NC_2-Pad14)") (class "Default")
      (node (ref "U1") (pin "14") (pinfunction "NC_2_14") (pintype "no_connect"))
    )
    (net (code "285") (name "unconnected-(U2-MFP-Pad7)") (class "Default")
      (node (ref "U2") (pin "7") (pinfunction "MFP_7") (pintype "passive"))
    )
    (net (code "286") (name "unconnected-(U3-LORA_CLK-PadP$7)") (class "Default")
      (node (ref "U3") (pin "P$7") (pinfunction "LORA_CLK_P$7") (pintype "no_connect"))
    )
    (net (code "287") (name "unconnected-(U3-LORA_MISO-PadP$9)") (class "Default")
      (node (ref "U3") (pin "P$9") (pinfunction "LORA_MISO_P$9") (pintype "no_connect"))
    )
    (net (code "288") (name "unconnected-(U3-LORA_MOSI-PadP$8)") (class "Default")
      (node (ref "U3") (pin "P$8") (pinfunction "LORA_MOSI_P$8") (pintype "no_connect"))
    )
    (net (code "289") (name "unconnected-(U4-DIN4-Pad21)") (class "Default")
      (node (ref "U4") (pin "21") (pinfunction "DIN4_21") (pintype "input"))
    )
    (net (code "290") (name "unconnected-(U4-DOUT4-Pad28)") (class "Default")
      (node (ref "U4") (pin "28") (pinfunction "DOUT4_28") (pintype "output"))
    )
    (net (code "291") (name "unconnected-(U4-RIN4-Pad23)") (class "Default")
      (node (ref "U4") (pin "23") (pinfunction "RIN4_23") (pintype "input"))
    )
    (net (code "292") (name "unconnected-(U4-RIN5-Pad18)") (class "Default")
      (node (ref "U4") (pin "18") (pinfunction "RIN5_18") (pintype "input"))
    )
    (net (code "293") (name "unconnected-(U4-ROUT4-Pad22)") (class "Default")
      (node (ref "U4") (pin "22") (pinfunction "ROUT4_22") (pintype "output"))
    )
    (net (code "294") (name "unconnected-(U4-ROUT5-Pad19)") (class "Default")
      (node (ref "U4") (pin "19") (pinfunction "ROUT5_19") (pintype "output"))
    )
    (net (code "295") (name "unconnected-(U5-CBUS4-Pad12)") (class "Default")
      (node (ref "U5") (pin "12") (pinfunction "CBUS4_12") (pintype "input"))
    )
    (net (code "296") (name "unconnected-(U5-OSCI-Pad27)") (class "Default")
      (node (ref "U5") (pin "27") (pinfunction "OSCI_27") (pintype "input"))
    )
    (net (code "297") (name "unconnected-(U5-OSCO-Pad28)") (class "Default")
      (node (ref "U5") (pin "28") (pinfunction "OSCO_28") (pintype "input"))
    )
    (net (code "298") (name "unconnected-(U5-~{CTS}-Pad11)") (class "Default")
      (node (ref "U5") (pin "11") (pinfunction "~{CTS}_11") (pintype "input"))
    )
    (net (code "299") (name "unconnected-(U5-~{DCD}-Pad10)") (class "Default")
      (node (ref "U5") (pin "10") (pinfunction "~{DCD}_10") (pintype "input"))
    )
    (net (code "300") (name "unconnected-(U5-~{DSR}-Pad9)") (class "Default")
      (node (ref "U5") (pin "9") (pinfunction "~{DSR}_9") (pintype "input"))
    )
    (net (code "301") (name "unconnected-(U5-~{DTR}-Pad2)") (class "Default")
      (node (ref "U5") (pin "2") (pinfunction "~{DTR}_2") (pintype "input"))
    )
    (net (code "302") (name "unconnected-(U5-~{RESET}-Pad19)") (class "Default")
      (node (ref "U5") (pin "19") (pinfunction "~{RESET}_19") (pintype "input"))
    )
    (net (code "303") (name "unconnected-(U5-~{RI}-Pad6)") (class "Default")
      (node (ref "U5") (pin "6") (pinfunction "~{RI}_6") (pintype "input"))
    )
    (net (code "304") (name "unconnected-(U5-~{RTS}-Pad3)") (class "Default")
      (node (ref "U5") (pin "3") (pinfunction "~{RTS}_3") (pintype "input"))
    )
    (net (code "305") (name "unconnected-(U6-CBUS2-Pad13)") (class "Default")
      (node (ref "U6") (pin "13") (pinfunction "CBUS2_13") (pintype "input"))
    )
    (net (code "306") (name "unconnected-(U6-CBUS3-Pad14)") (class "Default")
      (node (ref "U6") (pin "14") (pinfunction "CBUS3_14") (pintype "input"))
    )
    (net (code "307") (name "unconnected-(U6-CBUS4-Pad12)") (class "Default")
      (node (ref "U6") (pin "12") (pinfunction "CBUS4_12") (pintype "input"))
    )
    (net (code "308") (name "unconnected-(U6-OSCI-Pad27)") (class "Default")
      (node (ref "U6") (pin "27") (pinfunction "OSCI_27") (pintype "input"))
    )
    (net (code "309") (name "unconnected-(U6-OSCO-Pad28)") (class "Default")
      (node (ref "U6") (pin "28") (pinfunction "OSCO_28") (pintype "input"))
    )
    (net (code "310") (name "unconnected-(U6-~{CTS}-Pad11)") (class "Default")
      (node (ref "U6") (pin "11") (pinfunction "~{CTS}_11") (pintype "input"))
    )
    (net (code "311") (name "unconnected-(U6-~{DCD}-Pad10)") (class "Default")
      (node (ref "U6") (pin "10") (pinfunction "~{DCD}_10") (pintype "input"))
    )
    (net (code "312") (name "unconnected-(U6-~{DSR}-Pad9)") (class "Default")
      (node (ref "U6") (pin "9") (pinfunction "~{DSR}_9") (pintype "input"))
    )
    (net (code "313") (name "unconnected-(U6-~{DTR}-Pad2)") (class "Default")
      (node (ref "U6") (pin "2") (pinfunction "~{DTR}_2") (pintype "input"))
    )
    (net (code "314") (name "unconnected-(U6-~{RESET}-Pad19)") (class "Default")
      (node (ref "U6") (pin "19") (pinfunction "~{RESET}_19") (pintype "input"))
    )
    (net (code "315") (name "unconnected-(U6-~{RI}-Pad6)") (class "Default")
      (node (ref "U6") (pin "6") (pinfunction "~{RI}_6") (pintype "input"))
    )
    (net (code "316") (name "unconnected-(U6-~{RTS}-Pad3)") (class "Default")
      (node (ref "U6") (pin "3") (pinfunction "~{RTS}_3") (pintype "input"))
    )
    (net (code "317") (name "unconnected-(U11-NC-Pad2)") (class "Default")
      (node (ref "U11") (pin "2") (pinfunction "NC_2") (pintype "no_connect"))
    )
    (net (code "318") (name "unconnected-(U13-CBUS2-Pad13)") (class "Default")
      (node (ref "U13") (pin "13") (pinfunction "CBUS2_13") (pintype "input"))
    )
    (net (code "319") (name "unconnected-(U13-CBUS3-Pad14)") (class "Default")
      (node (ref "U13") (pin "14") (pinfunction "CBUS3_14") (pintype "input"))
    )
    (net (code "320") (name "unconnected-(U13-CBUS4-Pad12)") (class "Default")
      (node (ref "U13") (pin "12") (pinfunction "CBUS4_12") (pintype "input"))
    )
    (net (code "321") (name "unconnected-(U13-OSCI-Pad27)") (class "Default")
      (node (ref "U13") (pin "27") (pinfunction "OSCI_27") (pintype "input"))
    )
    (net (code "322") (name "unconnected-(U13-OSCO-Pad28)") (class "Default")
      (node (ref "U13") (pin "28") (pinfunction "OSCO_28") (pintype "input"))
    )
    (net (code "323") (name "unconnected-(U13-~{CTS}-Pad11)") (class "Default")
      (node (ref "U13") (pin "11") (pinfunction "~{CTS}_11") (pintype "input"))
    )
    (net (code "324") (name "unconnected-(U13-~{DCD}-Pad10)") (class "Default")
      (node (ref "U13") (pin "10") (pinfunction "~{DCD}_10") (pintype "input"))
    )
    (net (code "325") (name "unconnected-(U13-~{DSR}-Pad9)") (class "Default")
      (node (ref "U13") (pin "9") (pinfunction "~{DSR}_9") (pintype "input"))
    )
    (net (code "326") (name "unconnected-(U13-~{DTR}-Pad2)") (class "Default")
      (node (ref "U13") (pin "2") (pinfunction "~{DTR}_2") (pintype "input"))
    )
    (net (code "327") (name "unconnected-(U13-~{RESET}-Pad19)") (class "Default")
      (node (ref "U13") (pin "19") (pinfunction "~{RESET}_19") (pintype "input"))
    )
    (net (code "328") (name "unconnected-(U13-~{RI}-Pad6)") (class "Default")
      (node (ref "U13") (pin "6") (pinfunction "~{RI}_6") (pintype "input"))
    )
    (net (code "329") (name "unconnected-(U13-~{RTS}-Pad3)") (class "Default")
      (node (ref "U13") (pin "3") (pinfunction "~{RTS}_3") (pintype "input"))
    )
    (net (code "330") (name "unconnected-(U14-CBUS2-Pad13)") (class "Default")
      (node (ref "U14") (pin "13") (pinfunction "CBUS2_13") (pintype "input"))
    )
    (net (code "331") (name "unconnected-(U14-CBUS3-Pad14)") (class "Default")
      (node (ref "U14") (pin "14") (pinfunction "CBUS3_14") (pintype "input"))
    )
    (net (code "332") (name "unconnected-(U14-CBUS4-Pad12)") (class "Default")
      (node (ref "U14") (pin "12") (pinfunction "CBUS4_12") (pintype "input"))
    )
    (net (code "333") (name "unconnected-(U14-OSCI-Pad27)") (class "Default")
      (node (ref "U14") (pin "27") (pinfunction "OSCI_27") (pintype "input"))
    )
    (net (code "334") (name "unconnected-(U14-OSCO-Pad28)") (class "Default")
      (node (ref "U14") (pin "28") (pinfunction "OSCO_28") (pintype "input"))
    )
    (net (code "335") (name "unconnected-(U14-~{CTS}-Pad11)") (class "Default")
      (node (ref "U14") (pin "11") (pinfunction "~{CTS}_11") (pintype "input"))
    )
    (net (code "336") (name "unconnected-(U14-~{DCD}-Pad10)") (class "Default")
      (node (ref "U14") (pin "10") (pinfunction "~{DCD}_10") (pintype "input"))
    )
    (net (code "337") (name "unconnected-(U14-~{DSR}-Pad9)") (class "Default")
      (node (ref "U14") (pin "9") (pinfunction "~{DSR}_9") (pintype "input"))
    )
    (net (code "338") (name "unconnected-(U14-~{DTR}-Pad2)") (class "Default")
      (node (ref "U14") (pin "2") (pinfunction "~{DTR}_2") (pintype "input"))
    )
    (net (code "339") (name "unconnected-(U14-~{RESET}-Pad19)") (class "Default")
      (node (ref "U14") (pin "19") (pinfunction "~{RESET}_19") (pintype "input"))
    )
    (net (code "340") (name "unconnected-(U14-~{RI}-Pad6)") (class "Default")
      (node (ref "U14") (pin "6") (pinfunction "~{RI}_6") (pintype "input"))
    )
    (net (code "341") (name "unconnected-(U14-~{RTS}-Pad3)") (class "Default")
      (node (ref "U14") (pin "3") (pinfunction "~{RTS}_3") (pintype "input"))
    )
    (net (code "342") (name "unconnected-(U15-CBUS2-Pad13)") (class "Default")
      (node (ref "U15") (pin "13") (pinfunction "CBUS2_13") (pintype "input"))
    )
    (net (code "343") (name "unconnected-(U15-CBUS3-Pad14)") (class "Default")
      (node (ref "U15") (pin "14") (pinfunction "CBUS3_14") (pintype "input"))
    )
    (net (code "344") (name "unconnected-(U15-CBUS4-Pad12)") (class "Default")
      (node (ref "U15") (pin "12") (pinfunction "CBUS4_12") (pintype "input"))
    )
    (net (code "345") (name "unconnected-(U15-OSCI-Pad27)") (class "Default")
      (node (ref "U15") (pin "27") (pinfunction "OSCI_27") (pintype "input"))
    )
    (net (code "346") (name "unconnected-(U15-OSCO-Pad28)") (class "Default")
      (node (ref "U15") (pin "28") (pinfunction "OSCO_28") (pintype "input"))
    )
    (net (code "347") (name "unconnected-(U15-~{CTS}-Pad11)") (class "Default")
      (node (ref "U15") (pin "11") (pinfunction "~{CTS}_11") (pintype "input"))
    )
    (net (code "348") (name "unconnected-(U15-~{DCD}-Pad10)") (class "Default")
      (node (ref "U15") (pin "10") (pinfunction "~{DCD}_10") (pintype "input"))
    )
    (net (code "349") (name "unconnected-(U15-~{DSR}-Pad9)") (class "Default")
      (node (ref "U15") (pin "9") (pinfunction "~{DSR}_9") (pintype "input"))
    )
    (net (code "350") (name "unconnected-(U15-~{DTR}-Pad2)") (class "Default")
      (node (ref "U15") (pin "2") (pinfunction "~{DTR}_2") (pintype "input"))
    )
    (net (code "351") (name "unconnected-(U15-~{RESET}-Pad19)") (class "Default")
      (node (ref "U15") (pin "19") (pinfunction "~{RESET}_19") (pintype "input"))
    )
    (net (code "352") (name "unconnected-(U15-~{RI}-Pad6)") (class "Default")
      (node (ref "U15") (pin "6") (pinfunction "~{RI}_6") (pintype "input"))
    )
    (net (code "353") (name "unconnected-(U15-~{RTS}-Pad3)") (class "Default")
      (node (ref "U15") (pin "3") (pinfunction "~{RTS}_3") (pintype "input"))
    )
    (net (code "354") (name "unconnected-(USB1-ID-Pad4)") (class "Default")
      (node (ref "USB1") (pin "4") (pinfunction "ID_4") (pintype "bidirectional"))
    )
    (net (code "355") (name "unconnected-(USB3-ID-Pad4)") (class "Default")
      (node (ref "USB3") (pin "4") (pinfunction "ID_4") (pintype "bidirectional"))
    )
  )
)
